# GS_02_Pow.net
KiCad netlist of a schematic drawn in Altium Designer
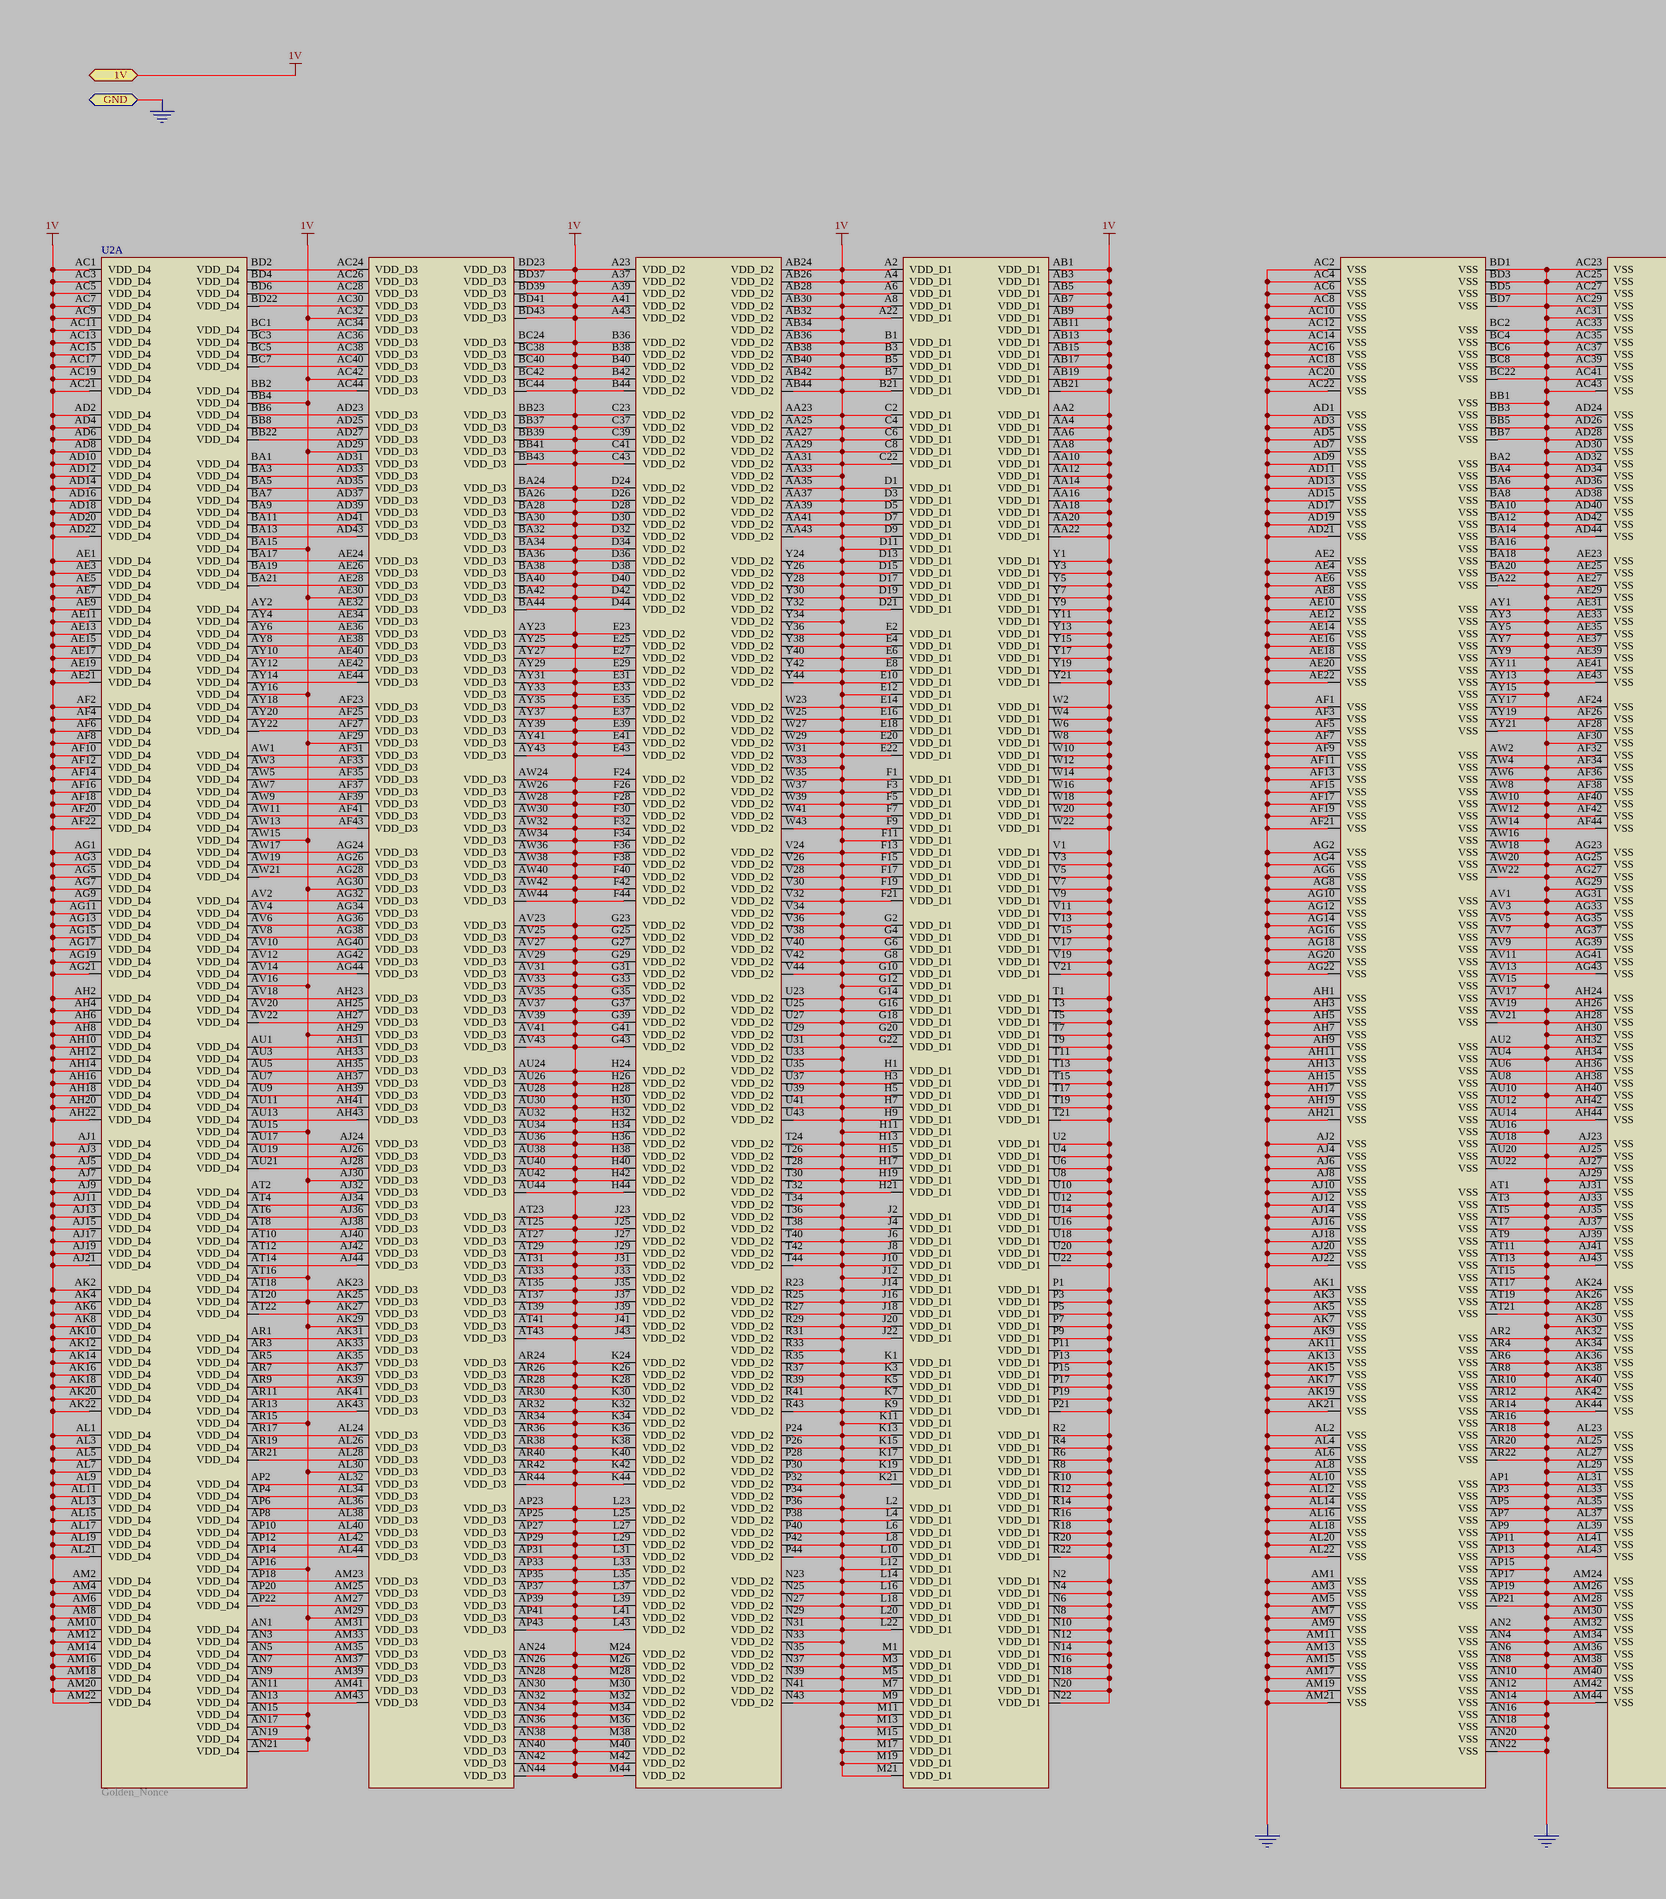
[diagram p0: GS_02_Pow.SchDoc, left]
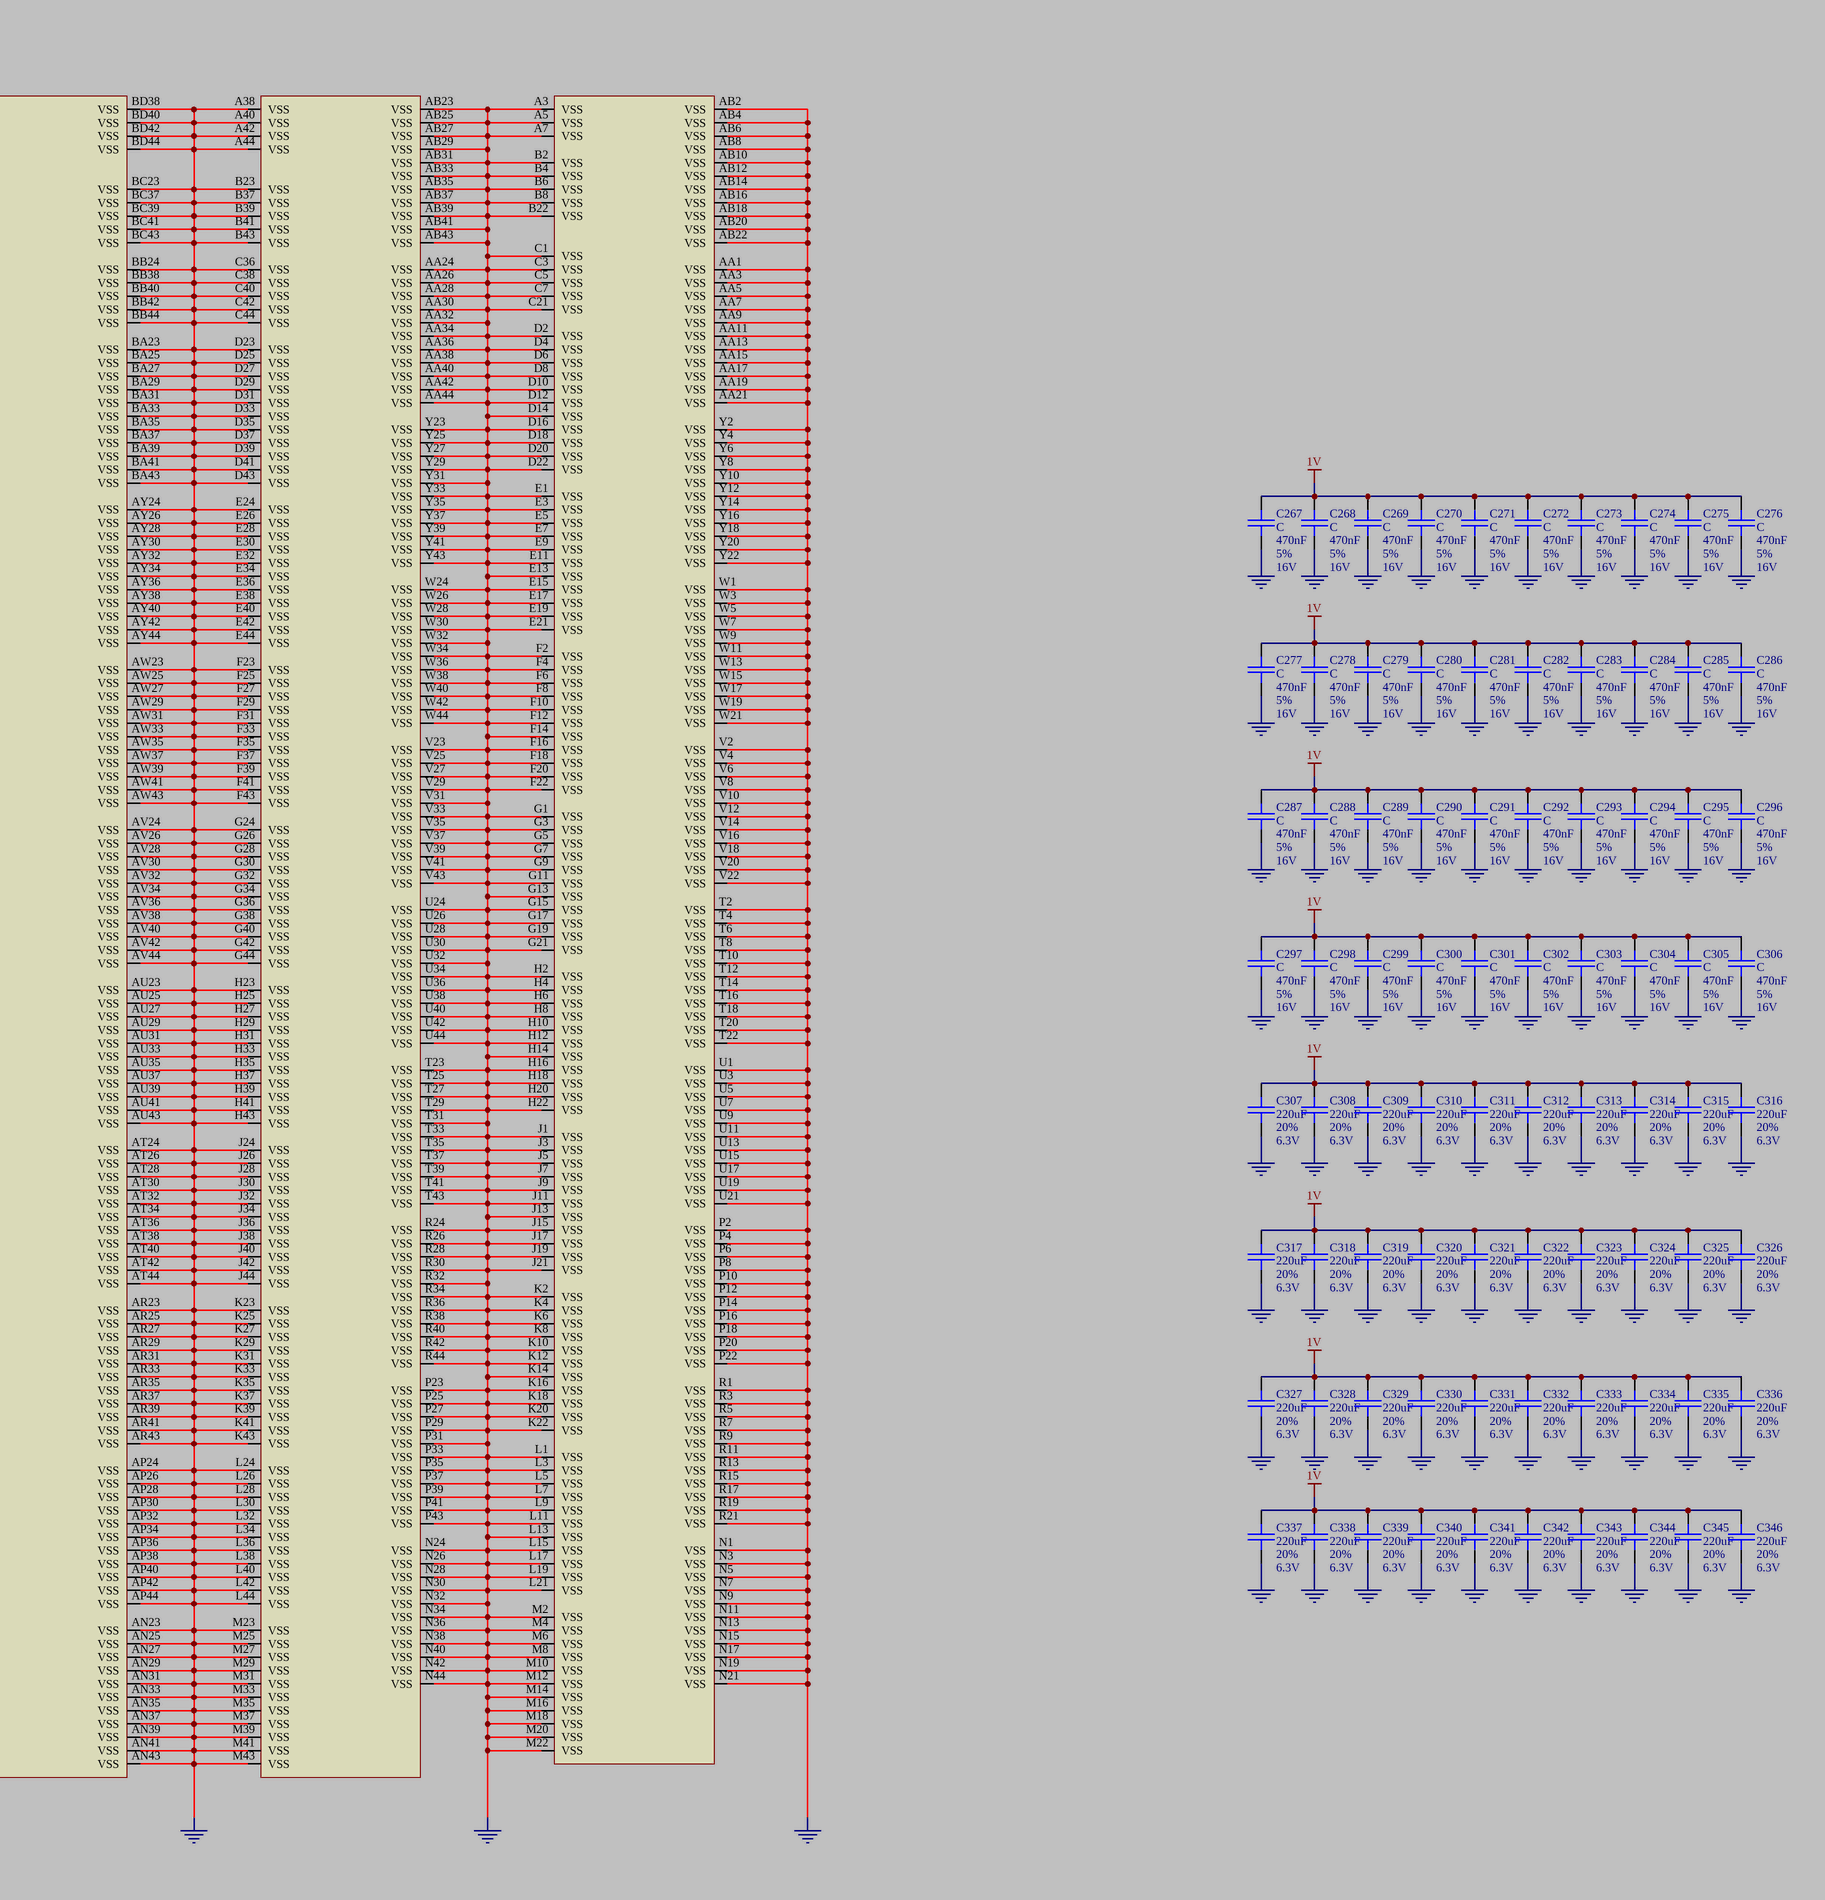
[diagram p1: GS_02_Pow.SchDoc, right]

(export (version "E")
  (design (tool "Eeschema 10.0.6"))
  (components
    (comp (ref "C267")
      (value "C")
      (footprint "SMD_0603_CAPC1608X95N")
      (fields
        (field (name "DB_PART_NUMBER") "CAP000028169")
        (field (name "DB_VALUE") "470nF")
        (field (name "DB_TOLERANCE") "5%")
        (field (name "DB_VOLTAGE") "16V")
        (field (name "DB_MANUFACTURER_PART") "KEMET    C0603C474J4RAC")
      )
      (libsource (lib "Database_Libs1") (part "C"))
    )
    (comp (ref "C268")
      (value "C")
      (footprint "SMD_0603_CAPC1608X95N")
      (fields
        (field (name "DB_PART_NUMBER") "CAP000028169")
        (field (name "DB_VALUE") "470nF")
        (field (name "DB_TOLERANCE") "5%")
        (field (name "DB_VOLTAGE") "16V")
        (field (name "DB_MANUFACTURER_PART") "KEMET    C0603C474J4RAC")
      )
      (libsource (lib "Database_Libs1") (part "C"))
    )
    (comp (ref "C269")
      (value "C")
      (footprint "SMD_0603_CAPC1608X95N")
      (fields
        (field (name "DB_PART_NUMBER") "CAP000028169")
        (field (name "DB_VALUE") "470nF")
        (field (name "DB_TOLERANCE") "5%")
        (field (name "DB_VOLTAGE") "16V")
        (field (name "DB_MANUFACTURER_PART") "KEMET    C0603C474J4RAC")
      )
      (libsource (lib "Database_Libs1") (part "C"))
    )
    (comp (ref "C270")
      (value "C")
      (footprint "SMD_0603_CAPC1608X95N")
      (fields
        (field (name "DB_PART_NUMBER") "CAP000028169")
        (field (name "DB_VALUE") "470nF")
        (field (name "DB_TOLERANCE") "5%")
        (field (name "DB_VOLTAGE") "16V")
        (field (name "DB_MANUFACTURER_PART") "KEMET    C0603C474J4RAC")
      )
      (libsource (lib "Database_Libs1") (part "C"))
    )
    (comp (ref "C271")
      (value "C")
      (footprint "SMD_0603_CAPC1608X95N")
      (fields
        (field (name "DB_PART_NUMBER") "CAP000028169")
        (field (name "DB_VALUE") "470nF")
        (field (name "DB_TOLERANCE") "5%")
        (field (name "DB_VOLTAGE") "16V")
        (field (name "DB_MANUFACTURER_PART") "KEMET    C0603C474J4RAC")
      )
      (libsource (lib "Database_Libs1") (part "C"))
    )
    (comp (ref "C272")
      (value "C")
      (footprint "SMD_0603_CAPC1608X95N")
      (fields
        (field (name "DB_PART_NUMBER") "CAP000028169")
        (field (name "DB_VALUE") "470nF")
        (field (name "DB_TOLERANCE") "5%")
        (field (name "DB_VOLTAGE") "16V")
        (field (name "DB_MANUFACTURER_PART") "KEMET    C0603C474J4RAC")
      )
      (libsource (lib "Database_Libs1") (part "C"))
    )
    (comp (ref "C273")
      (value "C")
      (footprint "SMD_0603_CAPC1608X95N")
      (fields
        (field (name "DB_PART_NUMBER") "CAP000028169")
        (field (name "DB_VALUE") "470nF")
        (field (name "DB_TOLERANCE") "5%")
        (field (name "DB_VOLTAGE") "16V")
        (field (name "DB_MANUFACTURER_PART") "KEMET    C0603C474J4RAC")
      )
      (libsource (lib "Database_Libs1") (part "C"))
    )
    (comp (ref "C274")
      (value "C")
      (footprint "SMD_0603_CAPC1608X95N")
      (fields
        (field (name "DB_PART_NUMBER") "CAP000028169")
        (field (name "DB_VALUE") "470nF")
        (field (name "DB_TOLERANCE") "5%")
        (field (name "DB_VOLTAGE") "16V")
        (field (name "DB_MANUFACTURER_PART") "KEMET    C0603C474J4RAC")
      )
      (libsource (lib "Database_Libs1") (part "C"))
    )
    (comp (ref "C275")
      (value "C")
      (footprint "SMD_0603_CAPC1608X95N")
      (fields
        (field (name "DB_PART_NUMBER") "CAP000028169")
        (field (name "DB_VALUE") "470nF")
        (field (name "DB_TOLERANCE") "5%")
        (field (name "DB_VOLTAGE") "16V")
        (field (name "DB_MANUFACTURER_PART") "KEMET    C0603C474J4RAC")
      )
      (libsource (lib "Database_Libs1") (part "C"))
    )
    (comp (ref "C276")
      (value "C")
      (footprint "SMD_0603_CAPC1608X95N")
      (fields
        (field (name "DB_PART_NUMBER") "CAP000028169")
        (field (name "DB_VALUE") "470nF")
        (field (name "DB_TOLERANCE") "5%")
        (field (name "DB_VOLTAGE") "16V")
        (field (name "DB_MANUFACTURER_PART") "KEMET    C0603C474J4RAC")
      )
      (libsource (lib "Database_Libs1") (part "C"))
    )
    (comp (ref "C277")
      (value "C")
      (footprint "SMD_0603_CAPC1608X95N")
      (fields
        (field (name "DB_PART_NUMBER") "CAP000028169")
        (field (name "DB_VALUE") "470nF")
        (field (name "DB_TOLERANCE") "5%")
        (field (name "DB_VOLTAGE") "16V")
        (field (name "DB_MANUFACTURER_PART") "KEMET    C0603C474J4RAC")
      )
      (libsource (lib "Database_Libs1") (part "C"))
    )
    (comp (ref "C278")
      (value "C")
      (footprint "SMD_0603_CAPC1608X95N")
      (fields
        (field (name "DB_PART_NUMBER") "CAP000028169")
        (field (name "DB_VALUE") "470nF")
        (field (name "DB_TOLERANCE") "5%")
        (field (name "DB_VOLTAGE") "16V")
        (field (name "DB_MANUFACTURER_PART") "KEMET    C0603C474J4RAC")
      )
      (libsource (lib "Database_Libs1") (part "C"))
    )
    (comp (ref "C279")
      (value "C")
      (footprint "SMD_0603_CAPC1608X95N")
      (fields
        (field (name "DB_PART_NUMBER") "CAP000028169")
        (field (name "DB_VALUE") "470nF")
        (field (name "DB_TOLERANCE") "5%")
        (field (name "DB_VOLTAGE") "16V")
        (field (name "DB_MANUFACTURER_PART") "KEMET    C0603C474J4RAC")
      )
      (libsource (lib "Database_Libs1") (part "C"))
    )
    (comp (ref "C280")
      (value "C")
      (footprint "SMD_0603_CAPC1608X95N")
      (fields
        (field (name "DB_PART_NUMBER") "CAP000028169")
        (field (name "DB_VALUE") "470nF")
        (field (name "DB_TOLERANCE") "5%")
        (field (name "DB_VOLTAGE") "16V")
        (field (name "DB_MANUFACTURER_PART") "KEMET    C0603C474J4RAC")
      )
      (libsource (lib "Database_Libs1") (part "C"))
    )
    (comp (ref "C281")
      (value "C")
      (footprint "SMD_0603_CAPC1608X95N")
      (fields
        (field (name "DB_PART_NUMBER") "CAP000028169")
        (field (name "DB_VALUE") "470nF")
        (field (name "DB_TOLERANCE") "5%")
        (field (name "DB_VOLTAGE") "16V")
        (field (name "DB_MANUFACTURER_PART") "KEMET    C0603C474J4RAC")
      )
      (libsource (lib "Database_Libs1") (part "C"))
    )
    (comp (ref "C282")
      (value "C")
      (footprint "SMD_0603_CAPC1608X95N")
      (fields
        (field (name "DB_PART_NUMBER") "CAP000028169")
        (field (name "DB_VALUE") "470nF")
        (field (name "DB_TOLERANCE") "5%")
        (field (name "DB_VOLTAGE") "16V")
        (field (name "DB_MANUFACTURER_PART") "KEMET    C0603C474J4RAC")
      )
      (libsource (lib "Database_Libs1") (part "C"))
    )
    (comp (ref "C283")
      (value "C")
      (footprint "SMD_0603_CAPC1608X95N")
      (fields
        (field (name "DB_PART_NUMBER") "CAP000028169")
        (field (name "DB_VALUE") "470nF")
        (field (name "DB_TOLERANCE") "5%")
        (field (name "DB_VOLTAGE") "16V")
        (field (name "DB_MANUFACTURER_PART") "KEMET    C0603C474J4RAC")
      )
      (libsource (lib "Database_Libs1") (part "C"))
    )
    (comp (ref "C284")
      (value "C")
      (footprint "SMD_0603_CAPC1608X95N")
      (fields
        (field (name "DB_PART_NUMBER") "CAP000028169")
        (field (name "DB_VALUE") "470nF")
        (field (name "DB_TOLERANCE") "5%")
        (field (name "DB_VOLTAGE") "16V")
        (field (name "DB_MANUFACTURER_PART") "KEMET    C0603C474J4RAC")
      )
      (libsource (lib "Database_Libs1") (part "C"))
    )
    (comp (ref "C285")
      (value "C")
      (footprint "SMD_0603_CAPC1608X95N")
      (fields
        (field (name "DB_PART_NUMBER") "CAP000028169")
        (field (name "DB_VALUE") "470nF")
        (field (name "DB_TOLERANCE") "5%")
        (field (name "DB_VOLTAGE") "16V")
        (field (name "DB_MANUFACTURER_PART") "KEMET    C0603C474J4RAC")
      )
      (libsource (lib "Database_Libs1") (part "C"))
    )
    (comp (ref "C286")
      (value "C")
      (footprint "SMD_0603_CAPC1608X95N")
      (fields
        (field (name "DB_PART_NUMBER") "CAP000028169")
        (field (name "DB_VALUE") "470nF")
        (field (name "DB_TOLERANCE") "5%")
        (field (name "DB_VOLTAGE") "16V")
        (field (name "DB_MANUFACTURER_PART") "KEMET    C0603C474J4RAC")
      )
      (libsource (lib "Database_Libs1") (part "C"))
    )
    (comp (ref "C287")
      (value "C")
      (footprint "SMD_0603_CAPC1608X95N")
      (fields
        (field (name "DB_PART_NUMBER") "CAP000028169")
        (field (name "DB_VALUE") "470nF")
        (field (name "DB_TOLERANCE") "5%")
        (field (name "DB_VOLTAGE") "16V")
        (field (name "DB_MANUFACTURER_PART") "KEMET    C0603C474J4RAC")
      )
      (libsource (lib "Database_Libs1") (part "C"))
    )
    (comp (ref "C288")
      (value "C")
      (footprint "SMD_0603_CAPC1608X95N")
      (fields
        (field (name "DB_PART_NUMBER") "CAP000028169")
        (field (name "DB_VALUE") "470nF")
        (field (name "DB_TOLERANCE") "5%")
        (field (name "DB_VOLTAGE") "16V")
        (field (name "DB_MANUFACTURER_PART") "KEMET    C0603C474J4RAC")
      )
      (libsource (lib "Database_Libs1") (part "C"))
    )
    (comp (ref "C289")
      (value "C")
      (footprint "SMD_0603_CAPC1608X95N")
      (fields
        (field (name "DB_PART_NUMBER") "CAP000028169")
        (field (name "DB_VALUE") "470nF")
        (field (name "DB_TOLERANCE") "5%")
        (field (name "DB_VOLTAGE") "16V")
        (field (name "DB_MANUFACTURER_PART") "KEMET    C0603C474J4RAC")
      )
      (libsource (lib "Database_Libs1") (part "C"))
    )
    (comp (ref "C290")
      (value "C")
      (footprint "SMD_0603_CAPC1608X95N")
      (fields
        (field (name "DB_PART_NUMBER") "CAP000028169")
        (field (name "DB_VALUE") "470nF")
        (field (name "DB_TOLERANCE") "5%")
        (field (name "DB_VOLTAGE") "16V")
        (field (name "DB_MANUFACTURER_PART") "KEMET    C0603C474J4RAC")
      )
      (libsource (lib "Database_Libs1") (part "C"))
    )
    (comp (ref "C291")
      (value "C")
      (footprint "SMD_0603_CAPC1608X95N")
      (fields
        (field (name "DB_PART_NUMBER") "CAP000028169")
        (field (name "DB_VALUE") "470nF")
        (field (name "DB_TOLERANCE") "5%")
        (field (name "DB_VOLTAGE") "16V")
        (field (name "DB_MANUFACTURER_PART") "KEMET    C0603C474J4RAC")
      )
      (libsource (lib "Database_Libs1") (part "C"))
    )
    (comp (ref "C292")
      (value "C")
      (footprint "SMD_0603_CAPC1608X95N")
      (fields
        (field (name "DB_PART_NUMBER") "CAP000028169")
        (field (name "DB_VALUE") "470nF")
        (field (name "DB_TOLERANCE") "5%")
        (field (name "DB_VOLTAGE") "16V")
        (field (name "DB_MANUFACTURER_PART") "KEMET    C0603C474J4RAC")
      )
      (libsource (lib "Database_Libs1") (part "C"))
    )
    (comp (ref "C293")
      (value "C")
      (footprint "SMD_0603_CAPC1608X95N")
      (fields
        (field (name "DB_PART_NUMBER") "CAP000028169")
        (field (name "DB_VALUE") "470nF")
        (field (name "DB_TOLERANCE") "5%")
        (field (name "DB_VOLTAGE") "16V")
        (field (name "DB_MANUFACTURER_PART") "KEMET    C0603C474J4RAC")
      )
      (libsource (lib "Database_Libs1") (part "C"))
    )
    (comp (ref "C294")
      (value "C")
      (footprint "SMD_0603_CAPC1608X95N")
      (fields
        (field (name "DB_PART_NUMBER") "CAP000028169")
        (field (name "DB_VALUE") "470nF")
        (field (name "DB_TOLERANCE") "5%")
        (field (name "DB_VOLTAGE") "16V")
        (field (name "DB_MANUFACTURER_PART") "KEMET    C0603C474J4RAC")
      )
      (libsource (lib "Database_Libs1") (part "C"))
    )
    (comp (ref "C295")
      (value "C")
      (footprint "SMD_0603_CAPC1608X95N")
      (fields
        (field (name "DB_PART_NUMBER") "CAP000028169")
        (field (name "DB_VALUE") "470nF")
        (field (name "DB_TOLERANCE") "5%")
        (field (name "DB_VOLTAGE") "16V")
        (field (name "DB_MANUFACTURER_PART") "KEMET    C0603C474J4RAC")
      )
      (libsource (lib "Database_Libs1") (part "C"))
    )
    (comp (ref "C296")
      (value "C")
      (footprint "SMD_0603_CAPC1608X95N")
      (fields
        (field (name "DB_PART_NUMBER") "CAP000028169")
        (field (name "DB_VALUE") "470nF")
        (field (name "DB_TOLERANCE") "5%")
        (field (name "DB_VOLTAGE") "16V")
        (field (name "DB_MANUFACTURER_PART") "KEMET    C0603C474J4RAC")
      )
      (libsource (lib "Database_Libs1") (part "C"))
    )
    (comp (ref "C297")
      (value "C")
      (footprint "SMD_0603_CAPC1608X95N")
      (fields
        (field (name "DB_PART_NUMBER") "CAP000028169")
        (field (name "DB_VALUE") "470nF")
        (field (name "DB_TOLERANCE") "5%")
        (field (name "DB_VOLTAGE") "16V")
        (field (name "DB_MANUFACTURER_PART") "KEMET    C0603C474J4RAC")
      )
      (libsource (lib "Database_Libs1") (part "C"))
    )
    (comp (ref "C298")
      (value "C")
      (footprint "SMD_0603_CAPC1608X95N")
      (fields
        (field (name "DB_PART_NUMBER") "CAP000028169")
        (field (name "DB_VALUE") "470nF")
        (field (name "DB_TOLERANCE") "5%")
        (field (name "DB_VOLTAGE") "16V")
        (field (name "DB_MANUFACTURER_PART") "KEMET    C0603C474J4RAC")
      )
      (libsource (lib "Database_Libs1") (part "C"))
    )
    (comp (ref "C299")
      (value "C")
      (footprint "SMD_0603_CAPC1608X95N")
      (fields
        (field (name "DB_PART_NUMBER") "CAP000028169")
        (field (name "DB_VALUE") "470nF")
        (field (name "DB_TOLERANCE") "5%")
        (field (name "DB_VOLTAGE") "16V")
        (field (name "DB_MANUFACTURER_PART") "KEMET    C0603C474J4RAC")
      )
      (libsource (lib "Database_Libs1") (part "C"))
    )
    (comp (ref "C300")
      (value "C")
      (footprint "SMD_0603_CAPC1608X95N")
      (fields
        (field (name "DB_PART_NUMBER") "CAP000028169")
        (field (name "DB_VALUE") "470nF")
        (field (name "DB_TOLERANCE") "5%")
        (field (name "DB_VOLTAGE") "16V")
        (field (name "DB_MANUFACTURER_PART") "KEMET    C0603C474J4RAC")
      )
      (libsource (lib "Database_Libs1") (part "C"))
    )
    (comp (ref "C301")
      (value "C")
      (footprint "SMD_0603_CAPC1608X95N")
      (fields
        (field (name "DB_PART_NUMBER") "CAP000028169")
        (field (name "DB_VALUE") "470nF")
        (field (name "DB_TOLERANCE") "5%")
        (field (name "DB_VOLTAGE") "16V")
        (field (name "DB_MANUFACTURER_PART") "KEMET    C0603C474J4RAC")
      )
      (libsource (lib "Database_Libs1") (part "C"))
    )
    (comp (ref "C302")
      (value "C")
      (footprint "SMD_0603_CAPC1608X95N")
      (fields
        (field (name "DB_PART_NUMBER") "CAP000028169")
        (field (name "DB_VALUE") "470nF")
        (field (name "DB_TOLERANCE") "5%")
        (field (name "DB_VOLTAGE") "16V")
        (field (name "DB_MANUFACTURER_PART") "KEMET    C0603C474J4RAC")
      )
      (libsource (lib "Database_Libs1") (part "C"))
    )
    (comp (ref "C303")
      (value "C")
      (footprint "SMD_0603_CAPC1608X95N")
      (fields
        (field (name "DB_PART_NUMBER") "CAP000028169")
        (field (name "DB_VALUE") "470nF")
        (field (name "DB_TOLERANCE") "5%")
        (field (name "DB_VOLTAGE") "16V")
        (field (name "DB_MANUFACTURER_PART") "KEMET    C0603C474J4RAC")
      )
      (libsource (lib "Database_Libs1") (part "C"))
    )
    (comp (ref "C304")
      (value "C")
      (footprint "SMD_0603_CAPC1608X95N")
      (fields
        (field (name "DB_PART_NUMBER") "CAP000028169")
        (field (name "DB_VALUE") "470nF")
        (field (name "DB_TOLERANCE") "5%")
        (field (name "DB_VOLTAGE") "16V")
        (field (name "DB_MANUFACTURER_PART") "KEMET    C0603C474J4RAC")
      )
      (libsource (lib "Database_Libs1") (part "C"))
    )
    (comp (ref "C305")
      (value "C")
      (footprint "SMD_0603_CAPC1608X95N")
      (fields
        (field (name "DB_PART_NUMBER") "CAP000028169")
        (field (name "DB_VALUE") "470nF")
        (field (name "DB_TOLERANCE") "5%")
        (field (name "DB_VOLTAGE") "16V")
        (field (name "DB_MANUFACTURER_PART") "KEMET    C0603C474J4RAC")
      )
      (libsource (lib "Database_Libs1") (part "C"))
    )
    (comp (ref "C306")
      (value "C")
      (footprint "SMD_0603_CAPC1608X95N")
      (fields
        (field (name "DB_PART_NUMBER") "CAP000028169")
        (field (name "DB_VALUE") "470nF")
        (field (name "DB_TOLERANCE") "5%")
        (field (name "DB_VOLTAGE") "16V")
        (field (name "DB_MANUFACTURER_PART") "KEMET    C0603C474J4RAC")
      )
      (libsource (lib "Database_Libs1") (part "C"))
    )
    (comp (ref "C307")
      (value "C")
      (footprint "SMD_1210_CAPC3225X279N")
      (fields
        (field (name "DB_PART_NUMBER") "CAP000047355")
        (field (name "DB_VALUE") "220uF")
        (field (name "DB_TOLERANCE") "20%")
        (field (name "DB_VOLTAGE") "6.3V")
        (field (name "DB_MANUFACTURER_PART") "SAMSUNG    CL32A227MQVNNNE")
        (field (name "DB_APPROVED_BY") "VSN")
      )
      (libsource (lib "Database_Libs1") (part "C"))
    )
    (comp (ref "C308")
      (value "C")
      (footprint "SMD_1210_CAPC3225X279N")
      (fields
        (field (name "DB_PART_NUMBER") "CAP000047355")
        (field (name "DB_VALUE") "220uF")
        (field (name "DB_TOLERANCE") "20%")
        (field (name "DB_VOLTAGE") "6.3V")
        (field (name "DB_MANUFACTURER_PART") "SAMSUNG    CL32A227MQVNNNE")
        (field (name "DB_APPROVED_BY") "VSN")
      )
      (libsource (lib "Database_Libs1") (part "C"))
    )
    (comp (ref "C309")
      (value "C")
      (footprint "SMD_1210_CAPC3225X279N")
      (fields
        (field (name "DB_PART_NUMBER") "CAP000047355")
        (field (name "DB_VALUE") "220uF")
        (field (name "DB_TOLERANCE") "20%")
        (field (name "DB_VOLTAGE") "6.3V")
        (field (name "DB_MANUFACTURER_PART") "SAMSUNG    CL32A227MQVNNNE")
        (field (name "DB_APPROVED_BY") "VSN")
      )
      (libsource (lib "Database_Libs1") (part "C"))
    )
    (comp (ref "C310")
      (value "C")
      (footprint "SMD_1210_CAPC3225X279N")
      (fields
        (field (name "DB_PART_NUMBER") "CAP000047355")
        (field (name "DB_VALUE") "220uF")
        (field (name "DB_TOLERANCE") "20%")
        (field (name "DB_VOLTAGE") "6.3V")
        (field (name "DB_MANUFACTURER_PART") "SAMSUNG    CL32A227MQVNNNE")
        (field (name "DB_APPROVED_BY") "VSN")
      )
      (libsource (lib "Database_Libs1") (part "C"))
    )
    (comp (ref "C311")
      (value "C")
      (footprint "SMD_1210_CAPC3225X279N")
      (fields
        (field (name "DB_PART_NUMBER") "CAP000047355")
        (field (name "DB_VALUE") "220uF")
        (field (name "DB_TOLERANCE") "20%")
        (field (name "DB_VOLTAGE") "6.3V")
        (field (name "DB_MANUFACTURER_PART") "SAMSUNG    CL32A227MQVNNNE")
        (field (name "DB_APPROVED_BY") "VSN")
      )
      (libsource (lib "Database_Libs1") (part "C"))
    )
    (comp (ref "C312")
      (value "C")
      (footprint "SMD_1210_CAPC3225X279N")
      (fields
        (field (name "DB_PART_NUMBER") "CAP000047355")
        (field (name "DB_VALUE") "220uF")
        (field (name "DB_TOLERANCE") "20%")
        (field (name "DB_VOLTAGE") "6.3V")
        (field (name "DB_MANUFACTURER_PART") "SAMSUNG    CL32A227MQVNNNE")
        (field (name "DB_APPROVED_BY") "VSN")
      )
      (libsource (lib "Database_Libs1") (part "C"))
    )
    (comp (ref "C313")
      (value "C")
      (footprint "SMD_1210_CAPC3225X279N")
      (fields
        (field (name "DB_PART_NUMBER") "CAP000047355")
        (field (name "DB_VALUE") "220uF")
        (field (name "DB_TOLERANCE") "20%")
        (field (name "DB_VOLTAGE") "6.3V")
        (field (name "DB_MANUFACTURER_PART") "SAMSUNG    CL32A227MQVNNNE")
        (field (name "DB_APPROVED_BY") "VSN")
      )
      (libsource (lib "Database_Libs1") (part "C"))
    )
    (comp (ref "C314")
      (value "C")
      (footprint "SMD_1210_CAPC3225X279N")
      (fields
        (field (name "DB_PART_NUMBER") "CAP000047355")
        (field (name "DB_VALUE") "220uF")
        (field (name "DB_TOLERANCE") "20%")
        (field (name "DB_VOLTAGE") "6.3V")
        (field (name "DB_MANUFACTURER_PART") "SAMSUNG    CL32A227MQVNNNE")
        (field (name "DB_APPROVED_BY") "VSN")
      )
      (libsource (lib "Database_Libs1") (part "C"))
    )
    (comp (ref "C315")
      (value "C")
      (footprint "SMD_1210_CAPC3225X279N")
      (fields
        (field (name "DB_PART_NUMBER") "CAP000047355")
        (field (name "DB_VALUE") "220uF")
        (field (name "DB_TOLERANCE") "20%")
        (field (name "DB_VOLTAGE") "6.3V")
        (field (name "DB_MANUFACTURER_PART") "SAMSUNG    CL32A227MQVNNNE")
        (field (name "DB_APPROVED_BY") "VSN")
      )
      (libsource (lib "Database_Libs1") (part "C"))
    )
    (comp (ref "C316")
      (value "C")
      (footprint "SMD_1210_CAPC3225X279N")
      (fields
        (field (name "DB_PART_NUMBER") "CAP000047355")
        (field (name "DB_VALUE") "220uF")
        (field (name "DB_TOLERANCE") "20%")
        (field (name "DB_VOLTAGE") "6.3V")
        (field (name "DB_MANUFACTURER_PART") "SAMSUNG    CL32A227MQVNNNE")
        (field (name "DB_APPROVED_BY") "VSN")
      )
      (libsource (lib "Database_Libs1") (part "C"))
    )
    (comp (ref "C317")
      (value "C")
      (footprint "SMD_1210_CAPC3225X279N")
      (fields
        (field (name "DB_PART_NUMBER") "CAP000047355")
        (field (name "DB_VALUE") "220uF")
        (field (name "DB_TOLERANCE") "20%")
        (field (name "DB_VOLTAGE") "6.3V")
        (field (name "DB_MANUFACTURER_PART") "SAMSUNG    CL32A227MQVNNNE")
        (field (name "DB_APPROVED_BY") "VSN")
      )
      (libsource (lib "Database_Libs1") (part "C"))
    )
    (comp (ref "C318")
      (value "C")
      (footprint "SMD_1210_CAPC3225X279N")
      (fields
        (field (name "DB_PART_NUMBER") "CAP000047355")
        (field (name "DB_VALUE") "220uF")
        (field (name "DB_TOLERANCE") "20%")
        (field (name "DB_VOLTAGE") "6.3V")
        (field (name "DB_MANUFACTURER_PART") "SAMSUNG    CL32A227MQVNNNE")
        (field (name "DB_APPROVED_BY") "VSN")
      )
      (libsource (lib "Database_Libs1") (part "C"))
    )
    (comp (ref "C319")
      (value "C")
      (footprint "SMD_1210_CAPC3225X279N")
      (fields
        (field (name "DB_PART_NUMBER") "CAP000047355")
        (field (name "DB_VALUE") "220uF")
        (field (name "DB_TOLERANCE") "20%")
        (field (name "DB_VOLTAGE") "6.3V")
        (field (name "DB_MANUFACTURER_PART") "SAMSUNG    CL32A227MQVNNNE")
        (field (name "DB_APPROVED_BY") "VSN")
      )
      (libsource (lib "Database_Libs1") (part "C"))
    )
    (comp (ref "C320")
      (value "C")
      (footprint "SMD_1210_CAPC3225X279N")
      (fields
        (field (name "DB_PART_NUMBER") "CAP000047355")
        (field (name "DB_VALUE") "220uF")
        (field (name "DB_TOLERANCE") "20%")
        (field (name "DB_VOLTAGE") "6.3V")
        (field (name "DB_MANUFACTURER_PART") "SAMSUNG    CL32A227MQVNNNE")
        (field (name "DB_APPROVED_BY") "VSN")
      )
      (libsource (lib "Database_Libs1") (part "C"))
    )
    (comp (ref "C321")
      (value "C")
      (footprint "SMD_1210_CAPC3225X279N")
      (fields
        (field (name "DB_PART_NUMBER") "CAP000047355")
        (field (name "DB_VALUE") "220uF")
        (field (name "DB_TOLERANCE") "20%")
        (field (name "DB_VOLTAGE") "6.3V")
        (field (name "DB_MANUFACTURER_PART") "SAMSUNG    CL32A227MQVNNNE")
        (field (name "DB_APPROVED_BY") "VSN")
      )
      (libsource (lib "Database_Libs1") (part "C"))
    )
    (comp (ref "C322")
      (value "C")
      (footprint "SMD_1210_CAPC3225X279N")
      (fields
        (field (name "DB_PART_NUMBER") "CAP000047355")
        (field (name "DB_VALUE") "220uF")
        (field (name "DB_TOLERANCE") "20%")
        (field (name "DB_VOLTAGE") "6.3V")
        (field (name "DB_MANUFACTURER_PART") "SAMSUNG    CL32A227MQVNNNE")
        (field (name "DB_APPROVED_BY") "VSN")
      )
      (libsource (lib "Database_Libs1") (part "C"))
    )
    (comp (ref "C323")
      (value "C")
      (footprint "SMD_1210_CAPC3225X279N")
      (fields
        (field (name "DB_PART_NUMBER") "CAP000047355")
        (field (name "DB_VALUE") "220uF")
        (field (name "DB_TOLERANCE") "20%")
        (field (name "DB_VOLTAGE") "6.3V")
        (field (name "DB_MANUFACTURER_PART") "SAMSUNG    CL32A227MQVNNNE")
        (field (name "DB_APPROVED_BY") "VSN")
      )
      (libsource (lib "Database_Libs1") (part "C"))
    )
    (comp (ref "C324")
      (value "C")
      (footprint "SMD_1210_CAPC3225X279N")
      (fields
        (field (name "DB_PART_NUMBER") "CAP000047355")
        (field (name "DB_VALUE") "220uF")
        (field (name "DB_TOLERANCE") "20%")
        (field (name "DB_VOLTAGE") "6.3V")
        (field (name "DB_MANUFACTURER_PART") "SAMSUNG    CL32A227MQVNNNE")
        (field (name "DB_APPROVED_BY") "VSN")
      )
      (libsource (lib "Database_Libs1") (part "C"))
    )
    (comp (ref "C325")
      (value "C")
      (footprint "SMD_1210_CAPC3225X279N")
      (fields
        (field (name "DB_PART_NUMBER") "CAP000047355")
        (field (name "DB_VALUE") "220uF")
        (field (name "DB_TOLERANCE") "20%")
        (field (name "DB_VOLTAGE") "6.3V")
        (field (name "DB_MANUFACTURER_PART") "SAMSUNG    CL32A227MQVNNNE")
        (field (name "DB_APPROVED_BY") "VSN")
      )
      (libsource (lib "Database_Libs1") (part "C"))
    )
    (comp (ref "C326")
      (value "C")
      (footprint "SMD_1210_CAPC3225X279N")
      (fields
        (field (name "DB_PART_NUMBER") "CAP000047355")
        (field (name "DB_VALUE") "220uF")
        (field (name "DB_TOLERANCE") "20%")
        (field (name "DB_VOLTAGE") "6.3V")
        (field (name "DB_MANUFACTURER_PART") "SAMSUNG    CL32A227MQVNNNE")
        (field (name "DB_APPROVED_BY") "VSN")
      )
      (libsource (lib "Database_Libs1") (part "C"))
    )
    (comp (ref "C327")
      (value "C")
      (footprint "SMD_1210_CAPC3225X279N")
      (fields
        (field (name "DB_PART_NUMBER") "CAP000047355")
        (field (name "DB_VALUE") "220uF")
        (field (name "DB_TOLERANCE") "20%")
        (field (name "DB_VOLTAGE") "6.3V")
        (field (name "DB_MANUFACTURER_PART") "SAMSUNG    CL32A227MQVNNNE")
        (field (name "DB_APPROVED_BY") "VSN")
      )
      (libsource (lib "Database_Libs1") (part "C"))
    )
    (comp (ref "C328")
      (value "C")
      (footprint "SMD_1210_CAPC3225X279N")
      (fields
        (field (name "DB_PART_NUMBER") "CAP000047355")
        (field (name "DB_VALUE") "220uF")
        (field (name "DB_TOLERANCE") "20%")
        (field (name "DB_VOLTAGE") "6.3V")
        (field (name "DB_MANUFACTURER_PART") "SAMSUNG    CL32A227MQVNNNE")
        (field (name "DB_APPROVED_BY") "VSN")
      )
      (libsource (lib "Database_Libs1") (part "C"))
    )
    (comp (ref "C329")
      (value "C")
      (footprint "SMD_1210_CAPC3225X279N")
      (fields
        (field (name "DB_PART_NUMBER") "CAP000047355")
        (field (name "DB_VALUE") "220uF")
        (field (name "DB_TOLERANCE") "20%")
        (field (name "DB_VOLTAGE") "6.3V")
        (field (name "DB_MANUFACTURER_PART") "SAMSUNG    CL32A227MQVNNNE")
        (field (name "DB_APPROVED_BY") "VSN")
      )
      (libsource (lib "Database_Libs1") (part "C"))
    )
    (comp (ref "C330")
      (value "C")
      (footprint "SMD_1210_CAPC3225X279N")
      (fields
        (field (name "DB_PART_NUMBER") "CAP000047355")
        (field (name "DB_VALUE") "220uF")
        (field (name "DB_TOLERANCE") "20%")
        (field (name "DB_VOLTAGE") "6.3V")
        (field (name "DB_MANUFACTURER_PART") "SAMSUNG    CL32A227MQVNNNE")
        (field (name "DB_APPROVED_BY") "VSN")
      )
      (libsource (lib "Database_Libs1") (part "C"))
    )
    (comp (ref "C331")
      (value "C")
      (footprint "SMD_1210_CAPC3225X279N")
      (fields
        (field (name "DB_PART_NUMBER") "CAP000047355")
        (field (name "DB_VALUE") "220uF")
        (field (name "DB_TOLERANCE") "20%")
        (field (name "DB_VOLTAGE") "6.3V")
        (field (name "DB_MANUFACTURER_PART") "SAMSUNG    CL32A227MQVNNNE")
        (field (name "DB_APPROVED_BY") "VSN")
      )
      (libsource (lib "Database_Libs1") (part "C"))
    )
    (comp (ref "C332")
      (value "C")
      (footprint "SMD_1210_CAPC3225X279N")
      (fields
        (field (name "DB_PART_NUMBER") "CAP000047355")
        (field (name "DB_VALUE") "220uF")
        (field (name "DB_TOLERANCE") "20%")
        (field (name "DB_VOLTAGE") "6.3V")
        (field (name "DB_MANUFACTURER_PART") "SAMSUNG    CL32A227MQVNNNE")
        (field (name "DB_APPROVED_BY") "VSN")
      )
      (libsource (lib "Database_Libs1") (part "C"))
    )
    (comp (ref "C333")
      (value "C")
      (footprint "SMD_1210_CAPC3225X279N")
      (fields
        (field (name "DB_PART_NUMBER") "CAP000047355")
        (field (name "DB_VALUE") "220uF")
        (field (name "DB_TOLERANCE") "20%")
        (field (name "DB_VOLTAGE") "6.3V")
        (field (name "DB_MANUFACTURER_PART") "SAMSUNG    CL32A227MQVNNNE")
        (field (name "DB_APPROVED_BY") "VSN")
      )
      (libsource (lib "Database_Libs1") (part "C"))
    )
    (comp (ref "C334")
      (value "C")
      (footprint "SMD_1210_CAPC3225X279N")
      (fields
        (field (name "DB_PART_NUMBER") "CAP000047355")
        (field (name "DB_VALUE") "220uF")
        (field (name "DB_TOLERANCE") "20%")
        (field (name "DB_VOLTAGE") "6.3V")
        (field (name "DB_MANUFACTURER_PART") "SAMSUNG    CL32A227MQVNNNE")
        (field (name "DB_APPROVED_BY") "VSN")
      )
      (libsource (lib "Database_Libs1") (part "C"))
    )
    (comp (ref "C335")
      (value "C")
      (footprint "SMD_1210_CAPC3225X279N")
      (fields
        (field (name "DB_PART_NUMBER") "CAP000047355")
        (field (name "DB_VALUE") "220uF")
        (field (name "DB_TOLERANCE") "20%")
        (field (name "DB_VOLTAGE") "6.3V")
        (field (name "DB_MANUFACTURER_PART") "SAMSUNG    CL32A227MQVNNNE")
        (field (name "DB_APPROVED_BY") "VSN")
      )
      (libsource (lib "Database_Libs1") (part "C"))
    )
    (comp (ref "C336")
      (value "C")
      (footprint "SMD_1210_CAPC3225X279N")
      (fields
        (field (name "DB_PART_NUMBER") "CAP000047355")
        (field (name "DB_VALUE") "220uF")
        (field (name "DB_TOLERANCE") "20%")
        (field (name "DB_VOLTAGE") "6.3V")
        (field (name "DB_MANUFACTURER_PART") "SAMSUNG    CL32A227MQVNNNE")
        (field (name "DB_APPROVED_BY") "VSN")
      )
      (libsource (lib "Database_Libs1") (part "C"))
    )
    (comp (ref "C337")
      (value "C")
      (footprint "SMD_1210_CAPC3225X279N")
      (fields
        (field (name "DB_PART_NUMBER") "CAP000047355")
        (field (name "DB_VALUE") "220uF")
        (field (name "DB_TOLERANCE") "20%")
        (field (name "DB_VOLTAGE") "6.3V")
        (field (name "DB_MANUFACTURER_PART") "SAMSUNG    CL32A227MQVNNNE")
        (field (name "DB_APPROVED_BY") "VSN")
      )
      (libsource (lib "Database_Libs1") (part "C"))
    )
    (comp (ref "C338")
      (value "C")
      (footprint "SMD_1210_CAPC3225X279N")
      (fields
        (field (name "DB_PART_NUMBER") "CAP000047355")
        (field (name "DB_VALUE") "220uF")
        (field (name "DB_TOLERANCE") "20%")
        (field (name "DB_VOLTAGE") "6.3V")
        (field (name "DB_MANUFACTURER_PART") "SAMSUNG    CL32A227MQVNNNE")
        (field (name "DB_APPROVED_BY") "VSN")
      )
      (libsource (lib "Database_Libs1") (part "C"))
    )
    (comp (ref "C339")
      (value "C")
      (footprint "SMD_1210_CAPC3225X279N")
      (fields
        (field (name "DB_PART_NUMBER") "CAP000047355")
        (field (name "DB_VALUE") "220uF")
        (field (name "DB_TOLERANCE") "20%")
        (field (name "DB_VOLTAGE") "6.3V")
        (field (name "DB_MANUFACTURER_PART") "SAMSUNG    CL32A227MQVNNNE")
        (field (name "DB_APPROVED_BY") "VSN")
      )
      (libsource (lib "Database_Libs1") (part "C"))
    )
    (comp (ref "C340")
      (value "C")
      (footprint "SMD_1210_CAPC3225X279N")
      (fields
        (field (name "DB_PART_NUMBER") "CAP000047355")
        (field (name "DB_VALUE") "220uF")
        (field (name "DB_TOLERANCE") "20%")
        (field (name "DB_VOLTAGE") "6.3V")
        (field (name "DB_MANUFACTURER_PART") "SAMSUNG    CL32A227MQVNNNE")
        (field (name "DB_APPROVED_BY") "VSN")
      )
      (libsource (lib "Database_Libs1") (part "C"))
    )
    (comp (ref "C341")
      (value "C")
      (footprint "SMD_1210_CAPC3225X279N")
      (fields
        (field (name "DB_PART_NUMBER") "CAP000047355")
        (field (name "DB_VALUE") "220uF")
        (field (name "DB_TOLERANCE") "20%")
        (field (name "DB_VOLTAGE") "6.3V")
        (field (name "DB_MANUFACTURER_PART") "SAMSUNG    CL32A227MQVNNNE")
        (field (name "DB_APPROVED_BY") "VSN")
      )
      (libsource (lib "Database_Libs1") (part "C"))
    )
    (comp (ref "C342")
      (value "C")
      (footprint "SMD_1210_CAPC3225X279N")
      (fields
        (field (name "DB_PART_NUMBER") "CAP000047355")
        (field (name "DB_VALUE") "220uF")
        (field (name "DB_TOLERANCE") "20%")
        (field (name "DB_VOLTAGE") "6.3V")
        (field (name "DB_MANUFACTURER_PART") "SAMSUNG    CL32A227MQVNNNE")
        (field (name "DB_APPROVED_BY") "VSN")
      )
      (libsource (lib "Database_Libs1") (part "C"))
    )
    (comp (ref "C343")
      (value "C")
      (footprint "SMD_1210_CAPC3225X279N")
      (fields
        (field (name "DB_PART_NUMBER") "CAP000047355")
        (field (name "DB_VALUE") "220uF")
        (field (name "DB_TOLERANCE") "20%")
        (field (name "DB_VOLTAGE") "6.3V")
        (field (name "DB_MANUFACTURER_PART") "SAMSUNG    CL32A227MQVNNNE")
        (field (name "DB_APPROVED_BY") "VSN")
      )
      (libsource (lib "Database_Libs1") (part "C"))
    )
    (comp (ref "C344")
      (value "C")
      (footprint "SMD_1210_CAPC3225X279N")
      (fields
        (field (name "DB_PART_NUMBER") "CAP000047355")
        (field (name "DB_VALUE") "220uF")
        (field (name "DB_TOLERANCE") "20%")
        (field (name "DB_VOLTAGE") "6.3V")
        (field (name "DB_MANUFACTURER_PART") "SAMSUNG    CL32A227MQVNNNE")
        (field (name "DB_APPROVED_BY") "VSN")
      )
      (libsource (lib "Database_Libs1") (part "C"))
    )
    (comp (ref "C345")
      (value "C")
      (footprint "SMD_1210_CAPC3225X279N")
      (fields
        (field (name "DB_PART_NUMBER") "CAP000047355")
        (field (name "DB_VALUE") "220uF")
        (field (name "DB_TOLERANCE") "20%")
        (field (name "DB_VOLTAGE") "6.3V")
        (field (name "DB_MANUFACTURER_PART") "SAMSUNG    CL32A227MQVNNNE")
        (field (name "DB_APPROVED_BY") "VSN")
      )
      (libsource (lib "Database_Libs1") (part "C"))
    )
    (comp (ref "C346")
      (value "C")
      (footprint "SMD_1210_CAPC3225X279N")
      (fields
        (field (name "DB_PART_NUMBER") "CAP000047355")
        (field (name "DB_VALUE") "220uF")
        (field (name "DB_TOLERANCE") "20%")
        (field (name "DB_VOLTAGE") "6.3V")
        (field (name "DB_MANUFACTURER_PART") "SAMSUNG    CL32A227MQVNNNE")
        (field (name "DB_APPROVED_BY") "VSN")
      )
      (libsource (lib "Database_Libs1") (part "C"))
    )
    (comp (ref "U2") (value "Golden_Nonce") (libsource (lib "Schlib1") (part "Golden_Nonce")))
  )
  (nets
    (net (code "1") (name "1V") (class "Default")
      (node (ref "C267") (pin "2") (pinfunction "2_2") (pintype "passive"))
      (node (ref "C268") (pin "2") (pinfunction "2_2") (pintype "passive"))
      (node (ref "C269") (pin "2") (pinfunction "2_2") (pintype "passive"))
      (node (ref "C270") (pin "2") (pinfunction "2_2") (pintype "passive"))
      (node (ref "C271") (pin "2") (pinfunction "2_2") (pintype "passive"))
      (node (ref "C272") (pin "2") (pinfunction "2_2") (pintype "passive"))
      (node (ref "C273") (pin "2") (pinfunction "2_2") (pintype "passive"))
      (node (ref "C274") (pin "2") (pinfunction "2_2") (pintype "passive"))
      (node (ref "C275") (pin "2") (pinfunction "2_2") (pintype "passive"))
      (node (ref "C276") (pin "2") (pinfunction "2_2") (pintype "passive"))
      (node (ref "C277") (pin "2") (pinfunction "2_2") (pintype "passive"))
      (node (ref "C278") (pin "2") (pinfunction "2_2") (pintype "passive"))
      (node (ref "C279") (pin "2") (pinfunction "2_2") (pintype "passive"))
      (node (ref "C280") (pin "2") (pinfunction "2_2") (pintype "passive"))
      (node (ref "C281") (pin "2") (pinfunction "2_2") (pintype "passive"))
      (node (ref "C282") (pin "2") (pinfunction "2_2") (pintype "passive"))
      (node (ref "C283") (pin "2") (pinfunction "2_2") (pintype "passive"))
      (node (ref "C284") (pin "2") (pinfunction "2_2") (pintype "passive"))
      (node (ref "C285") (pin "2") (pinfunction "2_2") (pintype "passive"))
      (node (ref "C286") (pin "2") (pinfunction "2_2") (pintype "passive"))
      (node (ref "C287") (pin "2") (pinfunction "2_2") (pintype "passive"))
      (node (ref "C288") (pin "2") (pinfunction "2_2") (pintype "passive"))
      (node (ref "C289") (pin "2") (pinfunction "2_2") (pintype "passive"))
      (node (ref "C290") (pin "2") (pinfunction "2_2") (pintype "passive"))
      (node (ref "C291") (pin "2") (pinfunction "2_2") (pintype "passive"))
      (node (ref "C292") (pin "2") (pinfunction "2_2") (pintype "passive"))
      (node (ref "C293") (pin "2") (pinfunction "2_2") (pintype "passive"))
      (node (ref "C294") (pin "2") (pinfunction "2_2") (pintype "passive"))
      (node (ref "C295") (pin "2") (pinfunction "2_2") (pintype "passive"))
      (node (ref "C296") (pin "2") (pinfunction "2_2") (pintype "passive"))
      (node (ref "C297") (pin "2") (pinfunction "2_2") (pintype "passive"))
      (node (ref "C298") (pin "2") (pinfunction "2_2") (pintype "passive"))
      (node (ref "C299") (pin "2") (pinfunction "2_2") (pintype "passive"))
      (node (ref "C300") (pin "2") (pinfunction "2_2") (pintype "passive"))
      (node (ref "C301") (pin "2") (pinfunction "2_2") (pintype "passive"))
      (node (ref "C302") (pin "2") (pinfunction "2_2") (pintype "passive"))
      (node (ref "C303") (pin "2") (pinfunction "2_2") (pintype "passive"))
      (node (ref "C304") (pin "2") (pinfunction "2_2") (pintype "passive"))
      (node (ref "C305") (pin "2") (pinfunction "2_2") (pintype "passive"))
      (node (ref "C306") (pin "2") (pinfunction "2_2") (pintype "passive"))
      (node (ref "C307") (pin "2") (pinfunction "2_2") (pintype "passive"))
      (node (ref "C308") (pin "2") (pinfunction "2_2") (pintype "passive"))
      (node (ref "C309") (pin "2") (pinfunction "2_2") (pintype "passive"))
      (node (ref "C310") (pin "2") (pinfunction "2_2") (pintype "passive"))
      (node (ref "C311") (pin "2") (pinfunction "2_2") (pintype "passive"))
      (node (ref "C312") (pin "2") (pinfunction "2_2") (pintype "passive"))
      (node (ref "C313") (pin "2") (pinfunction "2_2") (pintype "passive"))
      (node (ref "C314") (pin "2") (pinfunction "2_2") (pintype "passive"))
      (node (ref "C315") (pin "2") (pinfunction "2_2") (pintype "passive"))
      (node (ref "C316") (pin "2") (pinfunction "2_2") (pintype "passive"))
      (node (ref "C317") (pin "2") (pinfunction "2_2") (pintype "passive"))
      (node (ref "C318") (pin "2") (pinfunction "2_2") (pintype "passive"))
      (node (ref "C319") (pin "2") (pinfunction "2_2") (pintype "passive"))
      (node (ref "C320") (pin "2") (pinfunction "2_2") (pintype "passive"))
      (node (ref "C321") (pin "2") (pinfunction "2_2") (pintype "passive"))
      (node (ref "C322") (pin "2") (pinfunction "2_2") (pintype "passive"))
      (node (ref "C323") (pin "2") (pinfunction "2_2") (pintype "passive"))
      (node (ref "C324") (pin "2") (pinfunction "2_2") (pintype "passive"))
      (node (ref "C325") (pin "2") (pinfunction "2_2") (pintype "passive"))
      (node (ref "C326") (pin "2") (pinfunction "2_2") (pintype "passive"))
      (node (ref "C327") (pin "2") (pinfunction "2_2") (pintype "passive"))
      (node (ref "C328") (pin "2") (pinfunction "2_2") (pintype "passive"))
      (node (ref "C329") (pin "2") (pinfunction "2_2") (pintype "passive"))
      (node (ref "C330") (pin "2") (pinfunction "2_2") (pintype "passive"))
      (node (ref "C331") (pin "2") (pinfunction "2_2") (pintype "passive"))
      (node (ref "C332") (pin "2") (pinfunction "2_2") (pintype "passive"))
      (node (ref "C333") (pin "2") (pinfunction "2_2") (pintype "passive"))
      (node (ref "C334") (pin "2") (pinfunction "2_2") (pintype "passive"))
      (node (ref "C335") (pin "2") (pinfunction "2_2") (pintype "passive"))
      (node (ref "C336") (pin "2") (pinfunction "2_2") (pintype "passive"))
      (node (ref "C337") (pin "2") (pinfunction "2_2") (pintype "passive"))
      (node (ref "C338") (pin "2") (pinfunction "2_2") (pintype "passive"))
      (node (ref "C339") (pin "2") (pinfunction "2_2") (pintype "passive"))
      (node (ref "C340") (pin "2") (pinfunction "2_2") (pintype "passive"))
      (node (ref "C341") (pin "2") (pinfunction "2_2") (pintype "passive"))
      (node (ref "C342") (pin "2") (pinfunction "2_2") (pintype "passive"))
      (node (ref "C343") (pin "2") (pinfunction "2_2") (pintype "passive"))
      (node (ref "C344") (pin "2") (pinfunction "2_2") (pintype "passive"))
      (node (ref "C345") (pin "2") (pinfunction "2_2") (pintype "passive"))
      (node (ref "C346") (pin "2") (pinfunction "2_2") (pintype "passive"))
      (node (ref "U2") (pin "A2") (pinfunction "VDD_D1_A2") (pintype "passive"))
      (node (ref "U2") (pin "A22") (pinfunction "VDD_D1_A22") (pintype "passive"))
      (node (ref "U2") (pin "A23") (pinfunction "VDD_D2_A23") (pintype "passive"))
      (node (ref "U2") (pin "A37") (pinfunction "VDD_D2_A37") (pintype "passive"))
      (node (ref "U2") (pin "A39") (pinfunction "VDD_D2_A39") (pintype "passive"))
      (node (ref "U2") (pin "A4") (pinfunction "VDD_D1_A4") (pintype "passive"))
      (node (ref "U2") (pin "A41") (pinfunction "VDD_D2_A41") (pintype "passive"))
      (node (ref "U2") (pin "A43") (pinfunction "VDD_D2_A43") (pintype "passive"))
      (node (ref "U2") (pin "A6") (pinfunction "VDD_D1_A6") (pintype "passive"))
      (node (ref "U2") (pin "A8") (pinfunction "VDD_D1_A8") (pintype "passive"))
      (node (ref "U2") (pin "AA10") (pinfunction "VDD_D1_AA10") (pintype "passive"))
      (node (ref "U2") (pin "AA12") (pinfunction "VDD_D1_AA12") (pintype "passive"))
      (node (ref "U2") (pin "AA14") (pinfunction "VDD_D1_AA14") (pintype "passive"))
      (node (ref "U2") (pin "AA16") (pinfunction "VDD_D1_AA16") (pintype "passive"))
      (node (ref "U2") (pin "AA18") (pinfunction "VDD_D1_AA18") (pintype "passive"))
      (node (ref "U2") (pin "AA2") (pinfunction "VDD_D1_AA2") (pintype "passive"))
      (node (ref "U2") (pin "AA20") (pinfunction "VDD_D1_AA20") (pintype "passive"))
      (node (ref "U2") (pin "AA22") (pinfunction "VDD_D1_AA22") (pintype "passive"))
      (node (ref "U2") (pin "AA23") (pinfunction "VDD_D2_AA23") (pintype "passive"))
      (node (ref "U2") (pin "AA25") (pinfunction "VDD_D2_AA25") (pintype "passive"))
      (node (ref "U2") (pin "AA27") (pinfunction "VDD_D2_AA27") (pintype "passive"))
      (node (ref "U2") (pin "AA29") (pinfunction "VDD_D2_AA29") (pintype "passive"))
      (node (ref "U2") (pin "AA31") (pinfunction "VDD_D2_AA31") (pintype "passive"))
      (node (ref "U2") (pin "AA33") (pinfunction "VDD_D2_AA33") (pintype "passive"))
      (node (ref "U2") (pin "AA35") (pinfunction "VDD_D2_AA35") (pintype "passive"))
      (node (ref "U2") (pin "AA37") (pinfunction "VDD_D2_AA37") (pintype "passive"))
      (node (ref "U2") (pin "AA39") (pinfunction "VDD_D2_AA39") (pintype "passive"))
      (node (ref "U2") (pin "AA4") (pinfunction "VDD_D1_AA4") (pintype "passive"))
      (node (ref "U2") (pin "AA41") (pinfunction "VDD_D2_AA41") (pintype "passive"))
      (node (ref "U2") (pin "AA43") (pinfunction "VDD_D2_AA43") (pintype "passive"))
      (node (ref "U2") (pin "AA6") (pinfunction "VDD_D1_AA6") (pintype "passive"))
      (node (ref "U2") (pin "AA8") (pinfunction "VDD_D1_AA8") (pintype "passive"))
      (node (ref "U2") (pin "AB1") (pinfunction "VDD_D1_AB1") (pintype "passive"))
      (node (ref "U2") (pin "AB11") (pinfunction "VDD_D1_AB11") (pintype "passive"))
      (node (ref "U2") (pin "AB13") (pinfunction "VDD_D1_AB13") (pintype "passive"))
      (node (ref "U2") (pin "AB15") (pinfunction "VDD_D1_AB15") (pintype "passive"))
      (node (ref "U2") (pin "AB17") (pinfunction "VDD_D1_AB17") (pintype "passive"))
      (node (ref "U2") (pin "AB19") (pinfunction "VDD_D1_AB19") (pintype "passive"))
      (node (ref "U2") (pin "AB21") (pinfunction "VDD_D1_AB21") (pintype "passive"))
      (node (ref "U2") (pin "AB24") (pinfunction "VDD_D2_AB24") (pintype "passive"))
      (node (ref "U2") (pin "AB26") (pinfunction "VDD_D2_AB26") (pintype "passive"))
      (node (ref "U2") (pin "AB28") (pinfunction "VDD_D2_AB28") (pintype "passive"))
      (node (ref "U2") (pin "AB3") (pinfunction "VDD_D1_AB3") (pintype "passive"))
      (node (ref "U2") (pin "AB30") (pinfunction "VDD_D2_AB30") (pintype "passive"))
      (node (ref "U2") (pin "AB32") (pinfunction "VDD_D2_AB32") (pintype "passive"))
      (node (ref "U2") (pin "AB34") (pinfunction "VDD_D2_AB34") (pintype "passive"))
      (node (ref "U2") (pin "AB36") (pinfunction "VDD_D2_AB36") (pintype "passive"))
      (node (ref "U2") (pin "AB38") (pinfunction "VDD_D2_AB38") (pintype "passive"))
      (node (ref "U2") (pin "AB40") (pinfunction "VDD_D2_AB40") (pintype "passive"))
      (node (ref "U2") (pin "AB42") (pinfunction "VDD_D2_AB42") (pintype "passive"))
      (node (ref "U2") (pin "AB44") (pinfunction "VDD_D2_AB44") (pintype "passive"))
      (node (ref "U2") (pin "AB5") (pinfunction "VDD_D1_AB5") (pintype "passive"))
      (node (ref "U2") (pin "AB7") (pinfunction "VDD_D1_AB7") (pintype "passive"))
      (node (ref "U2") (pin "AB9") (pinfunction "VDD_D1_AB9") (pintype "passive"))
      (node (ref "U2") (pin "AC1") (pinfunction "VDD_D4_AC1") (pintype "passive"))
      (node (ref "U2") (pin "AC11") (pinfunction "VDD_D4_AC11") (pintype "passive"))
      (node (ref "U2") (pin "AC13") (pinfunction "VDD_D4_AC13") (pintype "passive"))
      (node (ref "U2") (pin "AC15") (pinfunction "VDD_D4_AC15") (pintype "passive"))
      (node (ref "U2") (pin "AC17") (pinfunction "VDD_D4_AC17") (pintype "passive"))
      (node (ref "U2") (pin "AC19") (pinfunction "VDD_D4_AC19") (pintype "passive"))
      (node (ref "U2") (pin "AC21") (pinfunction "VDD_D4_AC21") (pintype "passive"))
      (node (ref "U2") (pin "AC3") (pinfunction "VDD_D4_AC3") (pintype "passive"))
      (node (ref "U2") (pin "AC32") (pinfunction "VDD_D3_AC32") (pintype "passive"))
      (node (ref "U2") (pin "AC42") (pinfunction "VDD_D3_AC42") (pintype "passive"))
      (node (ref "U2") (pin "AC5") (pinfunction "VDD_D4_AC5") (pintype "passive"))
      (node (ref "U2") (pin "AC7") (pinfunction "VDD_D4_AC7") (pintype "passive"))
      (node (ref "U2") (pin "AC9") (pinfunction "VDD_D4_AC9") (pintype "passive"))
      (node (ref "U2") (pin "AD10") (pinfunction "VDD_D4_AD10") (pintype "passive"))
      (node (ref "U2") (pin "AD12") (pinfunction "VDD_D4_AD12") (pintype "passive"))
      (node (ref "U2") (pin "AD14") (pinfunction "VDD_D4_AD14") (pintype "passive"))
      (node (ref "U2") (pin "AD16") (pinfunction "VDD_D4_AD16") (pintype "passive"))
      (node (ref "U2") (pin "AD18") (pinfunction "VDD_D4_AD18") (pintype "passive"))
      (node (ref "U2") (pin "AD2") (pinfunction "VDD_D4_AD2") (pintype "passive"))
      (node (ref "U2") (pin "AD20") (pinfunction "VDD_D4_AD20") (pintype "passive"))
      (node (ref "U2") (pin "AD22") (pinfunction "VDD_D4_AD22") (pintype "passive"))
      (node (ref "U2") (pin "AD29") (pinfunction "VDD_D3_AD29") (pintype "passive"))
      (node (ref "U2") (pin "AD4") (pinfunction "VDD_D4_AD4") (pintype "passive"))
      (node (ref "U2") (pin "AD6") (pinfunction "VDD_D4_AD6") (pintype "passive"))
      (node (ref "U2") (pin "AD8") (pinfunction "VDD_D4_AD8") (pintype "passive"))
      (node (ref "U2") (pin "AE1") (pinfunction "VDD_D4_AE1") (pintype "passive"))
      (node (ref "U2") (pin "AE11") (pinfunction "VDD_D4_AE11") (pintype "passive"))
      (node (ref "U2") (pin "AE13") (pinfunction "VDD_D4_AE13") (pintype "passive"))
      (node (ref "U2") (pin "AE15") (pinfunction "VDD_D4_AE15") (pintype "passive"))
      (node (ref "U2") (pin "AE17") (pinfunction "VDD_D4_AE17") (pintype "passive"))
      (node (ref "U2") (pin "AE19") (pinfunction "VDD_D4_AE19") (pintype "passive"))
      (node (ref "U2") (pin "AE21") (pinfunction "VDD_D4_AE21") (pintype "passive"))
      (node (ref "U2") (pin "AE3") (pinfunction "VDD_D4_AE3") (pintype "passive"))
      (node (ref "U2") (pin "AE30") (pinfunction "VDD_D3_AE30") (pintype "passive"))
      (node (ref "U2") (pin "AE5") (pinfunction "VDD_D4_AE5") (pintype "passive"))
      (node (ref "U2") (pin "AE7") (pinfunction "VDD_D4_AE7") (pintype "passive"))
      (node (ref "U2") (pin "AE9") (pinfunction "VDD_D4_AE9") (pintype "passive"))
      (node (ref "U2") (pin "AF10") (pinfunction "VDD_D4_AF10") (pintype "passive"))
      (node (ref "U2") (pin "AF12") (pinfunction "VDD_D4_AF12") (pintype "passive"))
      (node (ref "U2") (pin "AF14") (pinfunction "VDD_D4_AF14") (pintype "passive"))
      (node (ref "U2") (pin "AF16") (pinfunction "VDD_D4_AF16") (pintype "passive"))
      (node (ref "U2") (pin "AF18") (pinfunction "VDD_D4_AF18") (pintype "passive"))
      (node (ref "U2") (pin "AF2") (pinfunction "VDD_D4_AF2") (pintype "passive"))
      (node (ref "U2") (pin "AF20") (pinfunction "VDD_D4_AF20") (pintype "passive"))
      (node (ref "U2") (pin "AF22") (pinfunction "VDD_D4_AF22") (pintype "passive"))
      (node (ref "U2") (pin "AF29") (pinfunction "VDD_D3_AF29") (pintype "passive"))
      (node (ref "U2") (pin "AF4") (pinfunction "VDD_D4_AF4") (pintype "passive"))
      (node (ref "U2") (pin "AF6") (pinfunction "VDD_D4_AF6") (pintype "passive"))
      (node (ref "U2") (pin "AF8") (pinfunction "VDD_D4_AF8") (pintype "passive"))
      (node (ref "U2") (pin "AG1") (pinfunction "VDD_D4_AG1") (pintype "passive"))
      (node (ref "U2") (pin "AG11") (pinfunction "VDD_D4_AG11") (pintype "passive"))
      (node (ref "U2") (pin "AG13") (pinfunction "VDD_D4_AG13") (pintype "passive"))
      (node (ref "U2") (pin "AG15") (pinfunction "VDD_D4_AG15") (pintype "passive"))
      (node (ref "U2") (pin "AG17") (pinfunction "VDD_D4_AG17") (pintype "passive"))
      (node (ref "U2") (pin "AG19") (pinfunction "VDD_D4_AG19") (pintype "passive"))
      (node (ref "U2") (pin "AG21") (pinfunction "VDD_D4_AG21") (pintype "passive"))
      (node (ref "U2") (pin "AG3") (pinfunction "VDD_D4_AG3") (pintype "passive"))
      (node (ref "U2") (pin "AG30") (pinfunction "VDD_D3_AG30") (pintype "passive"))
      (node (ref "U2") (pin "AG5") (pinfunction "VDD_D4_AG5") (pintype "passive"))
      (node (ref "U2") (pin "AG7") (pinfunction "VDD_D4_AG7") (pintype "passive"))
      (node (ref "U2") (pin "AG9") (pinfunction "VDD_D4_AG9") (pintype "passive"))
      (node (ref "U2") (pin "AH10") (pinfunction "VDD_D4_AH10") (pintype "passive"))
      (node (ref "U2") (pin "AH12") (pinfunction "VDD_D4_AH12") (pintype "passive"))
      (node (ref "U2") (pin "AH14") (pinfunction "VDD_D4_AH14") (pintype "passive"))
      (node (ref "U2") (pin "AH16") (pinfunction "VDD_D4_AH16") (pintype "passive"))
      (node (ref "U2") (pin "AH18") (pinfunction "VDD_D4_AH18") (pintype "passive"))
      (node (ref "U2") (pin "AH2") (pinfunction "VDD_D4_AH2") (pintype "passive"))
      (node (ref "U2") (pin "AH20") (pinfunction "VDD_D4_AH20") (pintype "passive"))
      (node (ref "U2") (pin "AH22") (pinfunction "VDD_D4_AH22") (pintype "passive"))
      (node (ref "U2") (pin "AH29") (pinfunction "VDD_D3_AH29") (pintype "passive"))
      (node (ref "U2") (pin "AH4") (pinfunction "VDD_D4_AH4") (pintype "passive"))
      (node (ref "U2") (pin "AH6") (pinfunction "VDD_D4_AH6") (pintype "passive"))
      (node (ref "U2") (pin "AH8") (pinfunction "VDD_D4_AH8") (pintype "passive"))
      (node (ref "U2") (pin "AJ1") (pinfunction "VDD_D4_AJ1") (pintype "passive"))
      (node (ref "U2") (pin "AJ11") (pinfunction "VDD_D4_AJ11") (pintype "passive"))
      (node (ref "U2") (pin "AJ13") (pinfunction "VDD_D4_AJ13") (pintype "passive"))
      (node (ref "U2") (pin "AJ15") (pinfunction "VDD_D4_AJ15") (pintype "passive"))
      (node (ref "U2") (pin "AJ17") (pinfunction "VDD_D4_AJ17") (pintype "passive"))
      (node (ref "U2") (pin "AJ19") (pinfunction "VDD_D4_AJ19") (pintype "passive"))
      (node (ref "U2") (pin "AJ21") (pinfunction "VDD_D4_AJ21") (pintype "passive"))
      (node (ref "U2") (pin "AJ3") (pinfunction "VDD_D4_AJ3") (pintype "passive"))
      (node (ref "U2") (pin "AJ30") (pinfunction "VDD_D3_AJ30") (pintype "passive"))
      (node (ref "U2") (pin "AJ5") (pinfunction "VDD_D4_AJ5") (pintype "passive"))
      (node (ref "U2") (pin "AJ7") (pinfunction "VDD_D4_AJ7") (pintype "passive"))
      (node (ref "U2") (pin "AJ9") (pinfunction "VDD_D4_AJ9") (pintype "passive"))
      (node (ref "U2") (pin "AK10") (pinfunction "VDD_D4_AK10") (pintype "passive"))
      (node (ref "U2") (pin "AK12") (pinfunction "VDD_D4_AK12") (pintype "passive"))
      (node (ref "U2") (pin "AK14") (pinfunction "VDD_D4_AK14") (pintype "passive"))
      (node (ref "U2") (pin "AK16") (pinfunction "VDD_D4_AK16") (pintype "passive"))
      (node (ref "U2") (pin "AK18") (pinfunction "VDD_D4_AK18") (pintype "passive"))
      (node (ref "U2") (pin "AK2") (pinfunction "VDD_D4_AK2") (pintype "passive"))
      (node (ref "U2") (pin "AK20") (pinfunction "VDD_D4_AK20") (pintype "passive"))
      (node (ref "U2") (pin "AK22") (pinfunction "VDD_D4_AK22") (pintype "passive"))
      (node (ref "U2") (pin "AK25") (pinfunction "VDD_D3_AK25") (pintype "passive"))
      (node (ref "U2") (pin "AK29") (pinfunction "VDD_D3_AK29") (pintype "passive"))
      (node (ref "U2") (pin "AK4") (pinfunction "VDD_D4_AK4") (pintype "passive"))
      (node (ref "U2") (pin "AK6") (pinfunction "VDD_D4_AK6") (pintype "passive"))
      (node (ref "U2") (pin "AK8") (pinfunction "VDD_D4_AK8") (pintype "passive"))
      (node (ref "U2") (pin "AL1") (pinfunction "VDD_D4_AL1") (pintype "passive"))
      (node (ref "U2") (pin "AL11") (pinfunction "VDD_D4_AL11") (pintype "passive"))
      (node (ref "U2") (pin "AL13") (pinfunction "VDD_D4_AL13") (pintype "passive"))
      (node (ref "U2") (pin "AL15") (pinfunction "VDD_D4_AL15") (pintype "passive"))
      (node (ref "U2") (pin "AL17") (pinfunction "VDD_D4_AL17") (pintype "passive"))
      (node (ref "U2") (pin "AL19") (pinfunction "VDD_D4_AL19") (pintype "passive"))
      (node (ref "U2") (pin "AL21") (pinfunction "VDD_D4_AL21") (pintype "passive"))
      (node (ref "U2") (pin "AL3") (pinfunction "VDD_D4_AL3") (pintype "passive"))
      (node (ref "U2") (pin "AL30") (pinfunction "VDD_D3_AL30") (pintype "passive"))
      (node (ref "U2") (pin "AL5") (pinfunction "VDD_D4_AL5") (pintype "passive"))
      (node (ref "U2") (pin "AL7") (pinfunction "VDD_D4_AL7") (pintype "passive"))
      (node (ref "U2") (pin "AL9") (pinfunction "VDD_D4_AL9") (pintype "passive"))
      (node (ref "U2") (pin "AM10") (pinfunction "VDD_D4_AM10") (pintype "passive"))
      (node (ref "U2") (pin "AM12") (pinfunction "VDD_D4_AM12") (pintype "passive"))
      (node (ref "U2") (pin "AM14") (pinfunction "VDD_D4_AM14") (pintype "passive"))
      (node (ref "U2") (pin "AM16") (pinfunction "VDD_D4_AM16") (pintype "passive"))
      (node (ref "U2") (pin "AM18") (pinfunction "VDD_D4_AM18") (pintype "passive"))
      (node (ref "U2") (pin "AM2") (pinfunction "VDD_D4_AM2") (pintype "passive"))
      (node (ref "U2") (pin "AM20") (pinfunction "VDD_D4_AM20") (pintype "passive"))
      (node (ref "U2") (pin "AM22") (pinfunction "VDD_D4_AM22") (pintype "passive"))
      (node (ref "U2") (pin "AM29") (pinfunction "VDD_D3_AM29") (pintype "passive"))
      (node (ref "U2") (pin "AM4") (pinfunction "VDD_D4_AM4") (pintype "passive"))
      (node (ref "U2") (pin "AM6") (pinfunction "VDD_D4_AM6") (pintype "passive"))
      (node (ref "U2") (pin "AM8") (pinfunction "VDD_D4_AM8") (pintype "passive"))
      (node (ref "U2") (pin "AN15") (pinfunction "VDD_D4_AN15") (pintype "passive"))
      (node (ref "U2") (pin "AN17") (pinfunction "VDD_D4_AN17") (pintype "passive"))
      (node (ref "U2") (pin "AN19") (pinfunction "VDD_D4_AN19") (pintype "passive"))
      (node (ref "U2") (pin "AN21") (pinfunction "VDD_D4_AN21") (pintype "passive"))
      (node (ref "U2") (pin "AN24") (pinfunction "VDD_D3_AN24") (pintype "passive"))
      (node (ref "U2") (pin "AN26") (pinfunction "VDD_D3_AN26") (pintype "passive"))
      (node (ref "U2") (pin "AN28") (pinfunction "VDD_D3_AN28") (pintype "passive"))
      (node (ref "U2") (pin "AN30") (pinfunction "VDD_D3_AN30") (pintype "passive"))
      (node (ref "U2") (pin "AN32") (pinfunction "VDD_D3_AN32") (pintype "passive"))
      (node (ref "U2") (pin "AN34") (pinfunction "VDD_D3_AN34") (pintype "passive"))
      (node (ref "U2") (pin "AN36") (pinfunction "VDD_D3_AN36") (pintype "passive"))
      (node (ref "U2") (pin "AN38") (pinfunction "VDD_D3_AN38") (pintype "passive"))
      (node (ref "U2") (pin "AN40") (pinfunction "VDD_D3_AN40") (pintype "passive"))
      (node (ref "U2") (pin "AN42") (pinfunction "VDD_D3_AN42") (pintype "passive"))
      (node (ref "U2") (pin "AN44") (pinfunction "VDD_D3_AN44") (pintype "passive"))
      (node (ref "U2") (pin "AP16") (pinfunction "VDD_D4_AP16") (pintype "passive"))
      (node (ref "U2") (pin "AP23") (pinfunction "VDD_D3_AP23") (pintype "passive"))
      (node (ref "U2") (pin "AP25") (pinfunction "VDD_D3_AP25") (pintype "passive"))
      (node (ref "U2") (pin "AP27") (pinfunction "VDD_D3_AP27") (pintype "passive"))
      (node (ref "U2") (pin "AP29") (pinfunction "VDD_D3_AP29") (pintype "passive"))
      (node (ref "U2") (pin "AP31") (pinfunction "VDD_D3_AP31") (pintype "passive"))
      (node (ref "U2") (pin "AP33") (pinfunction "VDD_D3_AP33") (pintype "passive"))
      (node (ref "U2") (pin "AP35") (pinfunction "VDD_D3_AP35") (pintype "passive"))
      (node (ref "U2") (pin "AP37") (pinfunction "VDD_D3_AP37") (pintype "passive"))
      (node (ref "U2") (pin "AP39") (pinfunction "VDD_D3_AP39") (pintype "passive"))
      (node (ref "U2") (pin "AP41") (pinfunction "VDD_D3_AP41") (pintype "passive"))
      (node (ref "U2") (pin "AP43") (pinfunction "VDD_D3_AP43") (pintype "passive"))
      (node (ref "U2") (pin "AR15") (pinfunction "VDD_D4_AR15") (pintype "passive"))
      (node (ref "U2") (pin "AR24") (pinfunction "VDD_D3_AR24") (pintype "passive"))
      (node (ref "U2") (pin "AR26") (pinfunction "VDD_D3_AR26") (pintype "passive"))
      (node (ref "U2") (pin "AR28") (pinfunction "VDD_D3_AR28") (pintype "passive"))
      (node (ref "U2") (pin "AR30") (pinfunction "VDD_D3_AR30") (pintype "passive"))
      (node (ref "U2") (pin "AR32") (pinfunction "VDD_D3_AR32") (pintype "passive"))
      (node (ref "U2") (pin "AR34") (pinfunction "VDD_D3_AR34") (pintype "passive"))
      (node (ref "U2") (pin "AR36") (pinfunction "VDD_D3_AR36") (pintype "passive"))
      (node (ref "U2") (pin "AR38") (pinfunction "VDD_D3_AR38") (pintype "passive"))
      (node (ref "U2") (pin "AR40") (pinfunction "VDD_D3_AR40") (pintype "passive"))
      (node (ref "U2") (pin "AR42") (pinfunction "VDD_D3_AR42") (pintype "passive"))
      (node (ref "U2") (pin "AR44") (pinfunction "VDD_D3_AR44") (pintype "passive"))
      (node (ref "U2") (pin "AT16") (pinfunction "VDD_D4_AT16") (pintype "passive"))
      (node (ref "U2") (pin "AT20") (pinfunction "VDD_D4_AT20") (pintype "passive"))
      (node (ref "U2") (pin "AT23") (pinfunction "VDD_D3_AT23") (pintype "passive"))
      (node (ref "U2") (pin "AT25") (pinfunction "VDD_D3_AT25") (pintype "passive"))
      (node (ref "U2") (pin "AT27") (pinfunction "VDD_D3_AT27") (pintype "passive"))
      (node (ref "U2") (pin "AT29") (pinfunction "VDD_D3_AT29") (pintype "passive"))
      (node (ref "U2") (pin "AT31") (pinfunction "VDD_D3_AT31") (pintype "passive"))
      (node (ref "U2") (pin "AT33") (pinfunction "VDD_D3_AT33") (pintype "passive"))
      (node (ref "U2") (pin "AT35") (pinfunction "VDD_D3_AT35") (pintype "passive"))
      (node (ref "U2") (pin "AT37") (pinfunction "VDD_D3_AT37") (pintype "passive"))
      (node (ref "U2") (pin "AT39") (pinfunction "VDD_D3_AT39") (pintype "passive"))
      (node (ref "U2") (pin "AT41") (pinfunction "VDD_D3_AT41") (pintype "passive"))
      (node (ref "U2") (pin "AT43") (pinfunction "VDD_D3_AT43") (pintype "passive"))
      (node (ref "U2") (pin "AU15") (pinfunction "VDD_D4_AU15") (pintype "passive"))
      (node (ref "U2") (pin "AU24") (pinfunction "VDD_D3_AU24") (pintype "passive"))
      (node (ref "U2") (pin "AU26") (pinfunction "VDD_D3_AU26") (pintype "passive"))
      (node (ref "U2") (pin "AU28") (pinfunction "VDD_D3_AU28") (pintype "passive"))
      (node (ref "U2") (pin "AU30") (pinfunction "VDD_D3_AU30") (pintype "passive"))
      (node (ref "U2") (pin "AU32") (pinfunction "VDD_D3_AU32") (pintype "passive"))
      (node (ref "U2") (pin "AU34") (pinfunction "VDD_D3_AU34") (pintype "passive"))
      (node (ref "U2") (pin "AU36") (pinfunction "VDD_D3_AU36") (pintype "passive"))
      (node (ref "U2") (pin "AU38") (pinfunction "VDD_D3_AU38") (pintype "passive"))
      (node (ref "U2") (pin "AU40") (pinfunction "VDD_D3_AU40") (pintype "passive"))
      (node (ref "U2") (pin "AU42") (pinfunction "VDD_D3_AU42") (pintype "passive"))
      (node (ref "U2") (pin "AU44") (pinfunction "VDD_D3_AU44") (pintype "passive"))
      (node (ref "U2") (pin "AV16") (pinfunction "VDD_D4_AV16") (pintype "passive"))
      (node (ref "U2") (pin "AV23") (pinfunction "VDD_D3_AV23") (pintype "passive"))
      (node (ref "U2") (pin "AV25") (pinfunction "VDD_D3_AV25") (pintype "passive"))
      (node (ref "U2") (pin "AV27") (pinfunction "VDD_D3_AV27") (pintype "passive"))
      (node (ref "U2") (pin "AV29") (pinfunction "VDD_D3_AV29") (pintype "passive"))
      (node (ref "U2") (pin "AV31") (pinfunction "VDD_D3_AV31") (pintype "passive"))
      (node (ref "U2") (pin "AV33") (pinfunction "VDD_D3_AV33") (pintype "passive"))
      (node (ref "U2") (pin "AV35") (pinfunction "VDD_D3_AV35") (pintype "passive"))
      (node (ref "U2") (pin "AV37") (pinfunction "VDD_D3_AV37") (pintype "passive"))
      (node (ref "U2") (pin "AV39") (pinfunction "VDD_D3_AV39") (pintype "passive"))
      (node (ref "U2") (pin "AV41") (pinfunction "VDD_D3_AV41") (pintype "passive"))
      (node (ref "U2") (pin "AV43") (pinfunction "VDD_D3_AV43") (pintype "passive"))
      (node (ref "U2") (pin "AW15") (pinfunction "VDD_D4_AW15") (pintype "passive"))
      (node (ref "U2") (pin "AW24") (pinfunction "VDD_D3_AW24") (pintype "passive"))
      (node (ref "U2") (pin "AW26") (pinfunction "VDD_D3_AW26") (pintype "passive"))
      (node (ref "U2") (pin "AW28") (pinfunction "VDD_D3_AW28") (pintype "passive"))
      (node (ref "U2") (pin "AW30") (pinfunction "VDD_D3_AW30") (pintype "passive"))
      (node (ref "U2") (pin "AW32") (pinfunction "VDD_D3_AW32") (pintype "passive"))
      (node (ref "U2") (pin "AW34") (pinfunction "VDD_D3_AW34") (pintype "passive"))
      (node (ref "U2") (pin "AW36") (pinfunction "VDD_D3_AW36") (pintype "passive"))
      (node (ref "U2") (pin "AW38") (pinfunction "VDD_D3_AW38") (pintype "passive"))
      (node (ref "U2") (pin "AW40") (pinfunction "VDD_D3_AW40") (pintype "passive"))
      (node (ref "U2") (pin "AW42") (pinfunction "VDD_D3_AW42") (pintype "passive"))
      (node (ref "U2") (pin "AW44") (pinfunction "VDD_D3_AW44") (pintype "passive"))
      (node (ref "U2") (pin "AY16") (pinfunction "VDD_D4_AY16") (pintype "passive"))
      (node (ref "U2") (pin "AY23") (pinfunction "VDD_D3_AY23") (pintype "passive"))
      (node (ref "U2") (pin "AY25") (pinfunction "VDD_D3_AY25") (pintype "passive"))
      (node (ref "U2") (pin "AY29") (pinfunction "VDD_D3_AY29") (pintype "passive"))
      (node (ref "U2") (pin "AY31") (pinfunction "VDD_D3_AY31") (pintype "passive"))
      (node (ref "U2") (pin "AY33") (pinfunction "VDD_D3_AY33") (pintype "passive"))
      (node (ref "U2") (pin "AY35") (pinfunction "VDD_D3_AY35") (pintype "passive"))
      (node (ref "U2") (pin "AY37") (pinfunction "VDD_D3_AY37") (pintype "passive"))
      (node (ref "U2") (pin "AY39") (pinfunction "VDD_D3_AY39") (pintype "passive"))
      (node (ref "U2") (pin "AY41") (pinfunction "VDD_D3_AY41") (pintype "passive"))
      (node (ref "U2") (pin "AY43") (pinfunction "VDD_D3_AY43") (pintype "passive"))
      (node (ref "U2") (pin "B1") (pinfunction "VDD_D1_B1") (pintype "passive"))
      (node (ref "U2") (pin "B21") (pinfunction "VDD_D1_B21") (pintype "passive"))
      (node (ref "U2") (pin "B3") (pinfunction "VDD_D1_B3") (pintype "passive"))
      (node (ref "U2") (pin "B36") (pinfunction "VDD_D2_B36") (pintype "passive"))
      (node (ref "U2") (pin "B38") (pinfunction "VDD_D2_B38") (pintype "passive"))
      (node (ref "U2") (pin "B40") (pinfunction "VDD_D2_B40") (pintype "passive"))
      (node (ref "U2") (pin "B42") (pinfunction "VDD_D2_B42") (pintype "passive"))
      (node (ref "U2") (pin "B44") (pinfunction "VDD_D2_B44") (pintype "passive"))
      (node (ref "U2") (pin "B5") (pinfunction "VDD_D1_B5") (pintype "passive"))
      (node (ref "U2") (pin "B7") (pinfunction "VDD_D1_B7") (pintype "passive"))
      (node (ref "U2") (pin "BA15") (pinfunction "VDD_D4_BA15") (pintype "passive"))
      (node (ref "U2") (pin "BA24") (pinfunction "VDD_D3_BA24") (pintype "passive"))
      (node (ref "U2") (pin "BA26") (pinfunction "VDD_D3_BA26") (pintype "passive"))
      (node (ref "U2") (pin "BA28") (pinfunction "VDD_D3_BA28") (pintype "passive"))
      (node (ref "U2") (pin "BA30") (pinfunction "VDD_D3_BA30") (pintype "passive"))
      (node (ref "U2") (pin "BA32") (pinfunction "VDD_D3_BA32") (pintype "passive"))
      (node (ref "U2") (pin "BA34") (pinfunction "VDD_D3_BA34") (pintype "passive"))
      (node (ref "U2") (pin "BA36") (pinfunction "VDD_D3_BA36") (pintype "passive"))
      (node (ref "U2") (pin "BA38") (pinfunction "VDD_D3_BA38") (pintype "passive"))
      (node (ref "U2") (pin "BA40") (pinfunction "VDD_D3_BA40") (pintype "passive"))
      (node (ref "U2") (pin "BA42") (pinfunction "VDD_D3_BA42") (pintype "passive"))
      (node (ref "U2") (pin "BA44") (pinfunction "VDD_D3_BA44") (pintype "passive"))
      (node (ref "U2") (pin "BB23") (pinfunction "VDD_D3_BB23") (pintype "passive"))
      (node (ref "U2") (pin "BB37") (pinfunction "VDD_D3_BB37") (pintype "passive"))
      (node (ref "U2") (pin "BB39") (pinfunction "VDD_D3_BB39") (pintype "passive"))
      (node (ref "U2") (pin "BB4") (pinfunction "VDD_D4_BB4") (pintype "passive"))
      (node (ref "U2") (pin "BB41") (pinfunction "VDD_D3_BB41") (pintype "passive"))
      (node (ref "U2") (pin "BB43") (pinfunction "VDD_D3_BB43") (pintype "passive"))
      (node (ref "U2") (pin "BC24") (pinfunction "VDD_D3_BC24") (pintype "passive"))
      (node (ref "U2") (pin "BC38") (pinfunction "VDD_D3_BC38") (pintype "passive"))
      (node (ref "U2") (pin "BC40") (pinfunction "VDD_D3_BC40") (pintype "passive"))
      (node (ref "U2") (pin "BC42") (pinfunction "VDD_D3_BC42") (pintype "passive"))
      (node (ref "U2") (pin "BC44") (pinfunction "VDD_D3_BC44") (pintype "passive"))
      (node (ref "U2") (pin "BD23") (pinfunction "VDD_D3_BD23") (pintype "passive"))
      (node (ref "U2") (pin "BD37") (pinfunction "VDD_D3_BD37") (pintype "passive"))
      (node (ref "U2") (pin "BD39") (pinfunction "VDD_D3_BD39") (pintype "passive"))
      (node (ref "U2") (pin "BD41") (pinfunction "VDD_D3_BD41") (pintype "passive"))
      (node (ref "U2") (pin "BD43") (pinfunction "VDD_D3_BD43") (pintype "passive"))
      (node (ref "U2") (pin "C2") (pinfunction "VDD_D1_C2") (pintype "passive"))
      (node (ref "U2") (pin "C22") (pinfunction "VDD_D1_C22") (pintype "passive"))
      (node (ref "U2") (pin "C23") (pinfunction "VDD_D2_C23") (pintype "passive"))
      (node (ref "U2") (pin "C37") (pinfunction "VDD_D2_C37") (pintype "passive"))
      (node (ref "U2") (pin "C39") (pinfunction "VDD_D2_C39") (pintype "passive"))
      (node (ref "U2") (pin "C4") (pinfunction "VDD_D1_C4") (pintype "passive"))
      (node (ref "U2") (pin "C41") (pinfunction "VDD_D2_C41") (pintype "passive"))
      (node (ref "U2") (pin "C43") (pinfunction "VDD_D2_C43") (pintype "passive"))
      (node (ref "U2") (pin "C6") (pinfunction "VDD_D1_C6") (pintype "passive"))
      (node (ref "U2") (pin "C8") (pinfunction "VDD_D1_C8") (pintype "passive"))
      (node (ref "U2") (pin "D1") (pinfunction "VDD_D1_D1") (pintype "passive"))
      (node (ref "U2") (pin "D11") (pinfunction "VDD_D1_D11") (pintype "passive"))
      (node (ref "U2") (pin "D13") (pinfunction "VDD_D1_D13") (pintype "passive"))
      (node (ref "U2") (pin "D15") (pinfunction "VDD_D1_D15") (pintype "passive"))
      (node (ref "U2") (pin "D17") (pinfunction "VDD_D1_D17") (pintype "passive"))
      (node (ref "U2") (pin "D19") (pinfunction "VDD_D1_D19") (pintype "passive"))
      (node (ref "U2") (pin "D21") (pinfunction "VDD_D1_D21") (pintype "passive"))
      (node (ref "U2") (pin "D24") (pinfunction "VDD_D2_D24") (pintype "passive"))
      (node (ref "U2") (pin "D26") (pinfunction "VDD_D2_D26") (pintype "passive"))
      (node (ref "U2") (pin "D28") (pinfunction "VDD_D2_D28") (pintype "passive"))
      (node (ref "U2") (pin "D3") (pinfunction "VDD_D1_D3") (pintype "passive"))
      (node (ref "U2") (pin "D30") (pinfunction "VDD_D2_D30") (pintype "passive"))
      (node (ref "U2") (pin "D32") (pinfunction "VDD_D2_D32") (pintype "passive"))
      (node (ref "U2") (pin "D34") (pinfunction "VDD_D2_D34") (pintype "passive"))
      (node (ref "U2") (pin "D36") (pinfunction "VDD_D2_D36") (pintype "passive"))
      (node (ref "U2") (pin "D38") (pinfunction "VDD_D2_D38") (pintype "passive"))
      (node (ref "U2") (pin "D40") (pinfunction "VDD_D2_D40") (pintype "passive"))
      (node (ref "U2") (pin "D42") (pinfunction "VDD_D2_D42") (pintype "passive"))
      (node (ref "U2") (pin "D44") (pinfunction "VDD_D2_D44") (pintype "passive"))
      (node (ref "U2") (pin "D5") (pinfunction "VDD_D1_D5") (pintype "passive"))
      (node (ref "U2") (pin "D7") (pinfunction "VDD_D1_D7") (pintype "passive"))
      (node (ref "U2") (pin "D9") (pinfunction "VDD_D1_D9") (pintype "passive"))
      (node (ref "U2") (pin "E10") (pinfunction "VDD_D1_E10") (pintype "passive"))
      (node (ref "U2") (pin "E12") (pinfunction "VDD_D1_E12") (pintype "passive"))
      (node (ref "U2") (pin "E14") (pinfunction "VDD_D1_E14") (pintype "passive"))
      (node (ref "U2") (pin "E16") (pinfunction "VDD_D1_E16") (pintype "passive"))
      (node (ref "U2") (pin "E18") (pinfunction "VDD_D1_E18") (pintype "passive"))
      (node (ref "U2") (pin "E2") (pinfunction "VDD_D1_E2") (pintype "passive"))
      (node (ref "U2") (pin "E20") (pinfunction "VDD_D1_E20") (pintype "passive"))
      (node (ref "U2") (pin "E22") (pinfunction "VDD_D1_E22") (pintype "passive"))
      (node (ref "U2") (pin "E23") (pinfunction "VDD_D2_E23") (pintype "passive"))
      (node (ref "U2") (pin "E25") (pinfunction "VDD_D2_E25") (pintype "passive"))
      (node (ref "U2") (pin "E29") (pinfunction "VDD_D2_E29") (pintype "passive"))
      (node (ref "U2") (pin "E31") (pinfunction "VDD_D2_E31") (pintype "passive"))
      (node (ref "U2") (pin "E33") (pinfunction "VDD_D2_E33") (pintype "passive"))
      (node (ref "U2") (pin "E35") (pinfunction "VDD_D2_E35") (pintype "passive"))
      (node (ref "U2") (pin "E37") (pinfunction "VDD_D2_E37") (pintype "passive"))
      (node (ref "U2") (pin "E39") (pinfunction "VDD_D2_E39") (pintype "passive"))
      (node (ref "U2") (pin "E4") (pinfunction "VDD_D1_E4") (pintype "passive"))
      (node (ref "U2") (pin "E41") (pinfunction "VDD_D2_E41") (pintype "passive"))
      (node (ref "U2") (pin "E43") (pinfunction "VDD_D2_E43") (pintype "passive"))
      (node (ref "U2") (pin "E6") (pinfunction "VDD_D1_E6") (pintype "passive"))
      (node (ref "U2") (pin "E8") (pinfunction "VDD_D1_E8") (pintype "passive"))
      (node (ref "U2") (pin "F1") (pinfunction "VDD_D1_F1") (pintype "passive"))
      (node (ref "U2") (pin "F11") (pinfunction "VDD_D1_F11") (pintype "passive"))
      (node (ref "U2") (pin "F13") (pinfunction "VDD_D1_F13") (pintype "passive"))
      (node (ref "U2") (pin "F15") (pinfunction "VDD_D1_F15") (pintype "passive"))
      (node (ref "U2") (pin "F17") (pinfunction "VDD_D1_F17") (pintype "passive"))
      (node (ref "U2") (pin "F19") (pinfunction "VDD_D1_F19") (pintype "passive"))
      (node (ref "U2") (pin "F21") (pinfunction "VDD_D1_F21") (pintype "passive"))
      (node (ref "U2") (pin "F24") (pinfunction "VDD_D2_F24") (pintype "passive"))
      (node (ref "U2") (pin "F26") (pinfunction "VDD_D2_F26") (pintype "passive"))
      (node (ref "U2") (pin "F28") (pinfunction "VDD_D2_F28") (pintype "passive"))
      (node (ref "U2") (pin "F3") (pinfunction "VDD_D1_F3") (pintype "passive"))
      (node (ref "U2") (pin "F30") (pinfunction "VDD_D2_F30") (pintype "passive"))
      (node (ref "U2") (pin "F32") (pinfunction "VDD_D2_F32") (pintype "passive"))
      (node (ref "U2") (pin "F34") (pinfunction "VDD_D2_F34") (pintype "passive"))
      (node (ref "U2") (pin "F36") (pinfunction "VDD_D2_F36") (pintype "passive"))
      (node (ref "U2") (pin "F38") (pinfunction "VDD_D2_F38") (pintype "passive"))
      (node (ref "U2") (pin "F40") (pinfunction "VDD_D2_F40") (pintype "passive"))
      (node (ref "U2") (pin "F42") (pinfunction "VDD_D2_F42") (pintype "passive"))
      (node (ref "U2") (pin "F44") (pinfunction "VDD_D2_F44") (pintype "passive"))
      (node (ref "U2") (pin "F5") (pinfunction "VDD_D1_F5") (pintype "passive"))
      (node (ref "U2") (pin "F7") (pinfunction "VDD_D1_F7") (pintype "passive"))
      (node (ref "U2") (pin "F9") (pinfunction "VDD_D1_F9") (pintype "passive"))
      (node (ref "U2") (pin "G10") (pinfunction "VDD_D1_G10") (pintype "passive"))
      (node (ref "U2") (pin "G12") (pinfunction "VDD_D1_G12") (pintype "passive"))
      (node (ref "U2") (pin "G14") (pinfunction "VDD_D1_G14") (pintype "passive"))
      (node (ref "U2") (pin "G16") (pinfunction "VDD_D1_G16") (pintype "passive"))
      (node (ref "U2") (pin "G18") (pinfunction "VDD_D1_G18") (pintype "passive"))
      (node (ref "U2") (pin "G2") (pinfunction "VDD_D1_G2") (pintype "passive"))
      (node (ref "U2") (pin "G20") (pinfunction "VDD_D1_G20") (pintype "passive"))
      (node (ref "U2") (pin "G22") (pinfunction "VDD_D1_G22") (pintype "passive"))
      (node (ref "U2") (pin "G23") (pinfunction "VDD_D2_G23") (pintype "passive"))
      (node (ref "U2") (pin "G25") (pinfunction "VDD_D2_G25") (pintype "passive"))
      (node (ref "U2") (pin "G27") (pinfunction "VDD_D2_G27") (pintype "passive"))
      (node (ref "U2") (pin "G29") (pinfunction "VDD_D2_G29") (pintype "passive"))
      (node (ref "U2") (pin "G31") (pinfunction "VDD_D2_G31") (pintype "passive"))
      (node (ref "U2") (pin "G33") (pinfunction "VDD_D2_G33") (pintype "passive"))
      (node (ref "U2") (pin "G35") (pinfunction "VDD_D2_G35") (pintype "passive"))
      (node (ref "U2") (pin "G37") (pinfunction "VDD_D2_G37") (pintype "passive"))
      (node (ref "U2") (pin "G39") (pinfunction "VDD_D2_G39") (pintype "passive"))
      (node (ref "U2") (pin "G4") (pinfunction "VDD_D1_G4") (pintype "passive"))
      (node (ref "U2") (pin "G41") (pinfunction "VDD_D2_G41") (pintype "passive"))
      (node (ref "U2") (pin "G43") (pinfunction "VDD_D2_G43") (pintype "passive"))
      (node (ref "U2") (pin "G6") (pinfunction "VDD_D1_G6") (pintype "passive"))
      (node (ref "U2") (pin "G8") (pinfunction "VDD_D1_G8") (pintype "passive"))
      (node (ref "U2") (pin "H1") (pinfunction "VDD_D1_H1") (pintype "passive"))
      (node (ref "U2") (pin "H11") (pinfunction "VDD_D1_H11") (pintype "passive"))
      (node (ref "U2") (pin "H13") (pinfunction "VDD_D1_H13") (pintype "passive"))
      (node (ref "U2") (pin "H15") (pinfunction "VDD_D1_H15") (pintype "passive"))
      (node (ref "U2") (pin "H17") (pinfunction "VDD_D1_H17") (pintype "passive"))
      (node (ref "U2") (pin "H19") (pinfunction "VDD_D1_H19") (pintype "passive"))
      (node (ref "U2") (pin "H21") (pinfunction "VDD_D1_H21") (pintype "passive"))
      (node (ref "U2") (pin "H24") (pinfunction "VDD_D2_H24") (pintype "passive"))
      (node (ref "U2") (pin "H26") (pinfunction "VDD_D2_H26") (pintype "passive"))
      (node (ref "U2") (pin "H28") (pinfunction "VDD_D2_H28") (pintype "passive"))
      (node (ref "U2") (pin "H3") (pinfunction "VDD_D1_H3") (pintype "passive"))
      (node (ref "U2") (pin "H30") (pinfunction "VDD_D2_H30") (pintype "passive"))
      (node (ref "U2") (pin "H32") (pinfunction "VDD_D2_H32") (pintype "passive"))
      (node (ref "U2") (pin "H34") (pinfunction "VDD_D2_H34") (pintype "passive"))
      (node (ref "U2") (pin "H36") (pinfunction "VDD_D2_H36") (pintype "passive"))
      (node (ref "U2") (pin "H38") (pinfunction "VDD_D2_H38") (pintype "passive"))
      (node (ref "U2") (pin "H40") (pinfunction "VDD_D2_H40") (pintype "passive"))
      (node (ref "U2") (pin "H42") (pinfunction "VDD_D2_H42") (pintype "passive"))
      (node (ref "U2") (pin "H44") (pinfunction "VDD_D2_H44") (pintype "passive"))
      (node (ref "U2") (pin "H5") (pinfunction "VDD_D1_H5") (pintype "passive"))
      (node (ref "U2") (pin "H7") (pinfunction "VDD_D1_H7") (pintype "passive"))
      (node (ref "U2") (pin "H9") (pinfunction "VDD_D1_H9") (pintype "passive"))
      (node (ref "U2") (pin "J10") (pinfunction "VDD_D1_J10") (pintype "passive"))
      (node (ref "U2") (pin "J12") (pinfunction "VDD_D1_J12") (pintype "passive"))
      (node (ref "U2") (pin "J14") (pinfunction "VDD_D1_J14") (pintype "passive"))
      (node (ref "U2") (pin "J16") (pinfunction "VDD_D1_J16") (pintype "passive"))
      (node (ref "U2") (pin "J18") (pinfunction "VDD_D1_J18") (pintype "passive"))
      (node (ref "U2") (pin "J2") (pinfunction "VDD_D1_J2") (pintype "passive"))
      (node (ref "U2") (pin "J20") (pinfunction "VDD_D1_J20") (pintype "passive"))
      (node (ref "U2") (pin "J22") (pinfunction "VDD_D1_J22") (pintype "passive"))
      (node (ref "U2") (pin "J23") (pinfunction "VDD_D2_J23") (pintype "passive"))
      (node (ref "U2") (pin "J25") (pinfunction "VDD_D2_J25") (pintype "passive"))
      (node (ref "U2") (pin "J27") (pinfunction "VDD_D2_J27") (pintype "passive"))
      (node (ref "U2") (pin "J29") (pinfunction "VDD_D2_J29") (pintype "passive"))
      (node (ref "U2") (pin "J31") (pinfunction "VDD_D2_J31") (pintype "passive"))
      (node (ref "U2") (pin "J33") (pinfunction "VDD_D2_J33") (pintype "passive"))
      (node (ref "U2") (pin "J35") (pinfunction "VDD_D2_J35") (pintype "passive"))
      (node (ref "U2") (pin "J37") (pinfunction "VDD_D2_J37") (pintype "passive"))
      (node (ref "U2") (pin "J39") (pinfunction "VDD_D2_J39") (pintype "passive"))
      (node (ref "U2") (pin "J4") (pinfunction "VDD_D1_J4") (pintype "passive"))
      (node (ref "U2") (pin "J41") (pinfunction "VDD_D2_J41") (pintype "passive"))
      (node (ref "U2") (pin "J43") (pinfunction "VDD_D2_J43") (pintype "passive"))
      (node (ref "U2") (pin "J6") (pinfunction "VDD_D1_J6") (pintype "passive"))
      (node (ref "U2") (pin "J8") (pinfunction "VDD_D1_J8") (pintype "passive"))
      (node (ref "U2") (pin "K1") (pinfunction "VDD_D1_K1") (pintype "passive"))
      (node (ref "U2") (pin "K11") (pinfunction "VDD_D1_K11") (pintype "passive"))
      (node (ref "U2") (pin "K13") (pinfunction "VDD_D1_K13") (pintype "passive"))
      (node (ref "U2") (pin "K15") (pinfunction "VDD_D1_K15") (pintype "passive"))
      (node (ref "U2") (pin "K17") (pinfunction "VDD_D1_K17") (pintype "passive"))
      (node (ref "U2") (pin "K19") (pinfunction "VDD_D1_K19") (pintype "passive"))
      (node (ref "U2") (pin "K21") (pinfunction "VDD_D1_K21") (pintype "passive"))
      (node (ref "U2") (pin "K24") (pinfunction "VDD_D2_K24") (pintype "passive"))
      (node (ref "U2") (pin "K26") (pinfunction "VDD_D2_K26") (pintype "passive"))
      (node (ref "U2") (pin "K28") (pinfunction "VDD_D2_K28") (pintype "passive"))
      (node (ref "U2") (pin "K3") (pinfunction "VDD_D1_K3") (pintype "passive"))
      (node (ref "U2") (pin "K30") (pinfunction "VDD_D2_K30") (pintype "passive"))
      (node (ref "U2") (pin "K32") (pinfunction "VDD_D2_K32") (pintype "passive"))
      (node (ref "U2") (pin "K34") (pinfunction "VDD_D2_K34") (pintype "passive"))
      (node (ref "U2") (pin "K36") (pinfunction "VDD_D2_K36") (pintype "passive"))
      (node (ref "U2") (pin "K38") (pinfunction "VDD_D2_K38") (pintype "passive"))
      (node (ref "U2") (pin "K40") (pinfunction "VDD_D2_K40") (pintype "passive"))
      (node (ref "U2") (pin "K42") (pinfunction "VDD_D2_K42") (pintype "passive"))
      (node (ref "U2") (pin "K44") (pinfunction "VDD_D2_K44") (pintype "passive"))
      (node (ref "U2") (pin "K5") (pinfunction "VDD_D1_K5") (pintype "passive"))
      (node (ref "U2") (pin "K7") (pinfunction "VDD_D1_K7") (pintype "passive"))
      (node (ref "U2") (pin "K9") (pinfunction "VDD_D1_K9") (pintype "passive"))
      (node (ref "U2") (pin "L10") (pinfunction "VDD_D1_L10") (pintype "passive"))
      (node (ref "U2") (pin "L12") (pinfunction "VDD_D1_L12") (pintype "passive"))
      (node (ref "U2") (pin "L14") (pinfunction "VDD_D1_L14") (pintype "passive"))
      (node (ref "U2") (pin "L16") (pinfunction "VDD_D1_L16") (pintype "passive"))
      (node (ref "U2") (pin "L18") (pinfunction "VDD_D1_L18") (pintype "passive"))
      (node (ref "U2") (pin "L2") (pinfunction "VDD_D1_L2") (pintype "passive"))
      (node (ref "U2") (pin "L20") (pinfunction "VDD_D1_L20") (pintype "passive"))
      (node (ref "U2") (pin "L22") (pinfunction "VDD_D1_L22") (pintype "passive"))
      (node (ref "U2") (pin "L23") (pinfunction "VDD_D2_L23") (pintype "passive"))
      (node (ref "U2") (pin "L25") (pinfunction "VDD_D2_L25") (pintype "passive"))
      (node (ref "U2") (pin "L27") (pinfunction "VDD_D2_L27") (pintype "passive"))
      (node (ref "U2") (pin "L29") (pinfunction "VDD_D2_L29") (pintype "passive"))
      (node (ref "U2") (pin "L31") (pinfunction "VDD_D2_L31") (pintype "passive"))
      (node (ref "U2") (pin "L33") (pinfunction "VDD_D2_L33") (pintype "passive"))
      (node (ref "U2") (pin "L35") (pinfunction "VDD_D2_L35") (pintype "passive"))
      (node (ref "U2") (pin "L37") (pinfunction "VDD_D2_L37") (pintype "passive"))
      (node (ref "U2") (pin "L39") (pinfunction "VDD_D2_L39") (pintype "passive"))
      (node (ref "U2") (pin "L4") (pinfunction "VDD_D1_L4") (pintype "passive"))
      (node (ref "U2") (pin "L41") (pinfunction "VDD_D2_L41") (pintype "passive"))
      (node (ref "U2") (pin "L43") (pinfunction "VDD_D2_L43") (pintype "passive"))
      (node (ref "U2") (pin "L6") (pinfunction "VDD_D1_L6") (pintype "passive"))
      (node (ref "U2") (pin "L8") (pinfunction "VDD_D1_L8") (pintype "passive"))
      (node (ref "U2") (pin "M1") (pinfunction "VDD_D1_M1") (pintype "passive"))
      (node (ref "U2") (pin "M11") (pinfunction "VDD_D1_M11") (pintype "passive"))
      (node (ref "U2") (pin "M13") (pinfunction "VDD_D1_M13") (pintype "passive"))
      (node (ref "U2") (pin "M15") (pinfunction "VDD_D1_M15") (pintype "passive"))
      (node (ref "U2") (pin "M17") (pinfunction "VDD_D1_M17") (pintype "passive"))
      (node (ref "U2") (pin "M19") (pinfunction "VDD_D1_M19") (pintype "passive"))
      (node (ref "U2") (pin "M21") (pinfunction "VDD_D1_M21") (pintype "passive"))
      (node (ref "U2") (pin "M24") (pinfunction "VDD_D2_M24") (pintype "passive"))
      (node (ref "U2") (pin "M26") (pinfunction "VDD_D2_M26") (pintype "passive"))
      (node (ref "U2") (pin "M28") (pinfunction "VDD_D2_M28") (pintype "passive"))
      (node (ref "U2") (pin "M3") (pinfunction "VDD_D1_M3") (pintype "passive"))
      (node (ref "U2") (pin "M30") (pinfunction "VDD_D2_M30") (pintype "passive"))
      (node (ref "U2") (pin "M32") (pinfunction "VDD_D2_M32") (pintype "passive"))
      (node (ref "U2") (pin "M34") (pinfunction "VDD_D2_M34") (pintype "passive"))
      (node (ref "U2") (pin "M36") (pinfunction "VDD_D2_M36") (pintype "passive"))
      (node (ref "U2") (pin "M38") (pinfunction "VDD_D2_M38") (pintype "passive"))
      (node (ref "U2") (pin "M40") (pinfunction "VDD_D2_M40") (pintype "passive"))
      (node (ref "U2") (pin "M42") (pinfunction "VDD_D2_M42") (pintype "passive"))
      (node (ref "U2") (pin "M44") (pinfunction "VDD_D2_M44") (pintype "passive"))
      (node (ref "U2") (pin "M5") (pinfunction "VDD_D1_M5") (pintype "passive"))
      (node (ref "U2") (pin "M7") (pinfunction "VDD_D1_M7") (pintype "passive"))
      (node (ref "U2") (pin "M9") (pinfunction "VDD_D1_M9") (pintype "passive"))
      (node (ref "U2") (pin "N10") (pinfunction "VDD_D1_N10") (pintype "passive"))
      (node (ref "U2") (pin "N12") (pinfunction "VDD_D1_N12") (pintype "passive"))
      (node (ref "U2") (pin "N14") (pinfunction "VDD_D1_N14") (pintype "passive"))
      (node (ref "U2") (pin "N16") (pinfunction "VDD_D1_N16") (pintype "passive"))
      (node (ref "U2") (pin "N18") (pinfunction "VDD_D1_N18") (pintype "passive"))
      (node (ref "U2") (pin "N2") (pinfunction "VDD_D1_N2") (pintype "passive"))
      (node (ref "U2") (pin "N20") (pinfunction "VDD_D1_N20") (pintype "passive"))
      (node (ref "U2") (pin "N22") (pinfunction "VDD_D1_N22") (pintype "passive"))
      (node (ref "U2") (pin "N23") (pinfunction "VDD_D2_N23") (pintype "passive"))
      (node (ref "U2") (pin "N25") (pinfunction "VDD_D2_N25") (pintype "passive"))
      (node (ref "U2") (pin "N27") (pinfunction "VDD_D2_N27") (pintype "passive"))
      (node (ref "U2") (pin "N29") (pinfunction "VDD_D2_N29") (pintype "passive"))
      (node (ref "U2") (pin "N31") (pinfunction "VDD_D2_N31") (pintype "passive"))
      (node (ref "U2") (pin "N33") (pinfunction "VDD_D2_N33") (pintype "passive"))
      (node (ref "U2") (pin "N35") (pinfunction "VDD_D2_N35") (pintype "passive"))
      (node (ref "U2") (pin "N37") (pinfunction "VDD_D2_N37") (pintype "passive"))
      (node (ref "U2") (pin "N39") (pinfunction "VDD_D2_N39") (pintype "passive"))
      (node (ref "U2") (pin "N4") (pinfunction "VDD_D1_N4") (pintype "passive"))
      (node (ref "U2") (pin "N41") (pinfunction "VDD_D2_N41") (pintype "passive"))
      (node (ref "U2") (pin "N43") (pinfunction "VDD_D2_N43") (pintype "passive"))
      (node (ref "U2") (pin "N6") (pinfunction "VDD_D1_N6") (pintype "passive"))
      (node (ref "U2") (pin "N8") (pinfunction "VDD_D1_N8") (pintype "passive"))
      (node (ref "U2") (pin "P1") (pinfunction "VDD_D1_P1") (pintype "passive"))
      (node (ref "U2") (pin "P11") (pinfunction "VDD_D1_P11") (pintype "passive"))
      (node (ref "U2") (pin "P13") (pinfunction "VDD_D1_P13") (pintype "passive"))
      (node (ref "U2") (pin "P15") (pinfunction "VDD_D1_P15") (pintype "passive"))
      (node (ref "U2") (pin "P17") (pinfunction "VDD_D1_P17") (pintype "passive"))
      (node (ref "U2") (pin "P19") (pinfunction "VDD_D1_P19") (pintype "passive"))
      (node (ref "U2") (pin "P21") (pinfunction "VDD_D1_P21") (pintype "passive"))
      (node (ref "U2") (pin "P24") (pinfunction "VDD_D2_P24") (pintype "passive"))
      (node (ref "U2") (pin "P26") (pinfunction "VDD_D2_P26") (pintype "passive"))
      (node (ref "U2") (pin "P28") (pinfunction "VDD_D2_P28") (pintype "passive"))
      (node (ref "U2") (pin "P3") (pinfunction "VDD_D1_P3") (pintype "passive"))
      (node (ref "U2") (pin "P30") (pinfunction "VDD_D2_P30") (pintype "passive"))
      (node (ref "U2") (pin "P32") (pinfunction "VDD_D2_P32") (pintype "passive"))
      (node (ref "U2") (pin "P34") (pinfunction "VDD_D2_P34") (pintype "passive"))
      (node (ref "U2") (pin "P36") (pinfunction "VDD_D2_P36") (pintype "passive"))
      (node (ref "U2") (pin "P38") (pinfunction "VDD_D2_P38") (pintype "passive"))
      (node (ref "U2") (pin "P40") (pinfunction "VDD_D2_P40") (pintype "passive"))
      (node (ref "U2") (pin "P42") (pinfunction "VDD_D2_P42") (pintype "passive"))
      (node (ref "U2") (pin "P44") (pinfunction "VDD_D2_P44") (pintype "passive"))
      (node (ref "U2") (pin "P5") (pinfunction "VDD_D1_P5") (pintype "passive"))
      (node (ref "U2") (pin "P7") (pinfunction "VDD_D1_P7") (pintype "passive"))
      (node (ref "U2") (pin "P9") (pinfunction "VDD_D1_P9") (pintype "passive"))
      (node (ref "U2") (pin "R10") (pinfunction "VDD_D1_R10") (pintype "passive"))
      (node (ref "U2") (pin "R12") (pinfunction "VDD_D1_R12") (pintype "passive"))
      (node (ref "U2") (pin "R14") (pinfunction "VDD_D1_R14") (pintype "passive"))
      (node (ref "U2") (pin "R16") (pinfunction "VDD_D1_R16") (pintype "passive"))
      (node (ref "U2") (pin "R18") (pinfunction "VDD_D1_R18") (pintype "passive"))
      (node (ref "U2") (pin "R2") (pinfunction "VDD_D1_R2") (pintype "passive"))
      (node (ref "U2") (pin "R20") (pinfunction "VDD_D1_R20") (pintype "passive"))
      (node (ref "U2") (pin "R22") (pinfunction "VDD_D1_R22") (pintype "passive"))
      (node (ref "U2") (pin "R23") (pinfunction "VDD_D2_R23") (pintype "passive"))
      (node (ref "U2") (pin "R25") (pinfunction "VDD_D2_R25") (pintype "passive"))
      (node (ref "U2") (pin "R27") (pinfunction "VDD_D2_R27") (pintype "passive"))
      (node (ref "U2") (pin "R29") (pinfunction "VDD_D2_R29") (pintype "passive"))
      (node (ref "U2") (pin "R31") (pinfunction "VDD_D2_R31") (pintype "passive"))
      (node (ref "U2") (pin "R33") (pinfunction "VDD_D2_R33") (pintype "passive"))
      (node (ref "U2") (pin "R35") (pinfunction "VDD_D2_R35") (pintype "passive"))
      (node (ref "U2") (pin "R37") (pinfunction "VDD_D2_R37") (pintype "passive"))
      (node (ref "U2") (pin "R39") (pinfunction "VDD_D2_R39") (pintype "passive"))
      (node (ref "U2") (pin "R4") (pinfunction "VDD_D1_R4") (pintype "passive"))
      (node (ref "U2") (pin "R41") (pinfunction "VDD_D2_R41") (pintype "passive"))
      (node (ref "U2") (pin "R43") (pinfunction "VDD_D2_R43") (pintype "passive"))
      (node (ref "U2") (pin "R6") (pinfunction "VDD_D1_R6") (pintype "passive"))
      (node (ref "U2") (pin "R8") (pinfunction "VDD_D1_R8") (pintype "passive"))
      (node (ref "U2") (pin "T1") (pinfunction "VDD_D1_T1") (pintype "passive"))
      (node (ref "U2") (pin "T11") (pinfunction "VDD_D1_T11") (pintype "passive"))
      (node (ref "U2") (pin "T13") (pinfunction "VDD_D1_T13") (pintype "passive"))
      (node (ref "U2") (pin "T15") (pinfunction "VDD_D1_T15") (pintype "passive"))
      (node (ref "U2") (pin "T17") (pinfunction "VDD_D1_T17") (pintype "passive"))
      (node (ref "U2") (pin "T19") (pinfunction "VDD_D1_T19") (pintype "passive"))
      (node (ref "U2") (pin "T21") (pinfunction "VDD_D1_T21") (pintype "passive"))
      (node (ref "U2") (pin "T24") (pinfunction "VDD_D2_T24") (pintype "passive"))
      (node (ref "U2") (pin "T26") (pinfunction "VDD_D2_T26") (pintype "passive"))
      (node (ref "U2") (pin "T28") (pinfunction "VDD_D2_T28") (pintype "passive"))
      (node (ref "U2") (pin "T3") (pinfunction "VDD_D1_T3") (pintype "passive"))
      (node (ref "U2") (pin "T30") (pinfunction "VDD_D2_T30") (pintype "passive"))
      (node (ref "U2") (pin "T32") (pinfunction "VDD_D2_T32") (pintype "passive"))
      (node (ref "U2") (pin "T34") (pinfunction "VDD_D2_T34") (pintype "passive"))
      (node (ref "U2") (pin "T36") (pinfunction "VDD_D2_T36") (pintype "passive"))
      (node (ref "U2") (pin "T38") (pinfunction "VDD_D2_T38") (pintype "passive"))
      (node (ref "U2") (pin "T40") (pinfunction "VDD_D2_T40") (pintype "passive"))
      (node (ref "U2") (pin "T42") (pinfunction "VDD_D2_T42") (pintype "passive"))
      (node (ref "U2") (pin "T44") (pinfunction "VDD_D2_T44") (pintype "passive"))
      (node (ref "U2") (pin "T5") (pinfunction "VDD_D1_T5") (pintype "passive"))
      (node (ref "U2") (pin "T7") (pinfunction "VDD_D1_T7") (pintype "passive"))
      (node (ref "U2") (pin "T9") (pinfunction "VDD_D1_T9") (pintype "passive"))
      (node (ref "U2") (pin "U10") (pinfunction "VDD_D1_U10") (pintype "passive"))
      (node (ref "U2") (pin "U12") (pinfunction "VDD_D1_U12") (pintype "passive"))
      (node (ref "U2") (pin "U14") (pinfunction "VDD_D1_U14") (pintype "passive"))
      (node (ref "U2") (pin "U16") (pinfunction "VDD_D1_U16") (pintype "passive"))
      (node (ref "U2") (pin "U18") (pinfunction "VDD_D1_U18") (pintype "passive"))
      (node (ref "U2") (pin "U2") (pinfunction "VDD_D1_U2") (pintype "passive"))
      (node (ref "U2") (pin "U20") (pinfunction "VDD_D1_U20") (pintype "passive"))
      (node (ref "U2") (pin "U22") (pinfunction "VDD_D1_U22") (pintype "passive"))
      (node (ref "U2") (pin "U23") (pinfunction "VDD_D2_U23") (pintype "passive"))
      (node (ref "U2") (pin "U25") (pinfunction "VDD_D2_U25") (pintype "passive"))
      (node (ref "U2") (pin "U27") (pinfunction "VDD_D2_U27") (pintype "passive"))
      (node (ref "U2") (pin "U29") (pinfunction "VDD_D2_U29") (pintype "passive"))
      (node (ref "U2") (pin "U31") (pinfunction "VDD_D2_U31") (pintype "passive"))
      (node (ref "U2") (pin "U33") (pinfunction "VDD_D2_U33") (pintype "passive"))
      (node (ref "U2") (pin "U35") (pinfunction "VDD_D2_U35") (pintype "passive"))
      (node (ref "U2") (pin "U37") (pinfunction "VDD_D2_U37") (pintype "passive"))
      (node (ref "U2") (pin "U39") (pinfunction "VDD_D2_U39") (pintype "passive"))
      (node (ref "U2") (pin "U4") (pinfunction "VDD_D1_U4") (pintype "passive"))
      (node (ref "U2") (pin "U41") (pinfunction "VDD_D2_U41") (pintype "passive"))
      (node (ref "U2") (pin "U43") (pinfunction "VDD_D2_U43") (pintype "passive"))
      (node (ref "U2") (pin "U6") (pinfunction "VDD_D1_U6") (pintype "passive"))
      (node (ref "U2") (pin "U8") (pinfunction "VDD_D1_U8") (pintype "passive"))
      (node (ref "U2") (pin "V1") (pinfunction "VDD_D1_V1") (pintype "passive"))
      (node (ref "U2") (pin "V11") (pinfunction "VDD_D1_V11") (pintype "passive"))
      (node (ref "U2") (pin "V13") (pinfunction "VDD_D1_V13") (pintype "passive"))
      (node (ref "U2") (pin "V15") (pinfunction "VDD_D1_V15") (pintype "passive"))
      (node (ref "U2") (pin "V17") (pinfunction "VDD_D1_V17") (pintype "passive"))
      (node (ref "U2") (pin "V19") (pinfunction "VDD_D1_V19") (pintype "passive"))
      (node (ref "U2") (pin "V21") (pinfunction "VDD_D1_V21") (pintype "passive"))
      (node (ref "U2") (pin "V24") (pinfunction "VDD_D2_V24") (pintype "passive"))
      (node (ref "U2") (pin "V26") (pinfunction "VDD_D2_V26") (pintype "passive"))
      (node (ref "U2") (pin "V28") (pinfunction "VDD_D2_V28") (pintype "passive"))
      (node (ref "U2") (pin "V3") (pinfunction "VDD_D1_V3") (pintype "passive"))
      (node (ref "U2") (pin "V30") (pinfunction "VDD_D2_V30") (pintype "passive"))
      (node (ref "U2") (pin "V32") (pinfunction "VDD_D2_V32") (pintype "passive"))
      (node (ref "U2") (pin "V34") (pinfunction "VDD_D2_V34") (pintype "passive"))
      (node (ref "U2") (pin "V36") (pinfunction "VDD_D2_V36") (pintype "passive"))
      (node (ref "U2") (pin "V38") (pinfunction "VDD_D2_V38") (pintype "passive"))
      (node (ref "U2") (pin "V40") (pinfunction "VDD_D2_V40") (pintype "passive"))
      (node (ref "U2") (pin "V42") (pinfunction "VDD_D2_V42") (pintype "passive"))
      (node (ref "U2") (pin "V44") (pinfunction "VDD_D2_V44") (pintype "passive"))
      (node (ref "U2") (pin "V5") (pinfunction "VDD_D1_V5") (pintype "passive"))
      (node (ref "U2") (pin "V7") (pinfunction "VDD_D1_V7") (pintype "passive"))
      (node (ref "U2") (pin "V9") (pinfunction "VDD_D1_V9") (pintype "passive"))
      (node (ref "U2") (pin "W10") (pinfunction "VDD_D1_W10") (pintype "passive"))
      (node (ref "U2") (pin "W12") (pinfunction "VDD_D1_W12") (pintype "passive"))
      (node (ref "U2") (pin "W14") (pinfunction "VDD_D1_W14") (pintype "passive"))
      (node (ref "U2") (pin "W16") (pinfunction "VDD_D1_W16") (pintype "passive"))
      (node (ref "U2") (pin "W18") (pinfunction "VDD_D1_W18") (pintype "passive"))
      (node (ref "U2") (pin "W2") (pinfunction "VDD_D1_W2") (pintype "passive"))
      (node (ref "U2") (pin "W20") (pinfunction "VDD_D1_W20") (pintype "passive"))
      (node (ref "U2") (pin "W22") (pinfunction "VDD_D1_W22") (pintype "passive"))
      (node (ref "U2") (pin "W23") (pinfunction "VDD_D2_W23") (pintype "passive"))
      (node (ref "U2") (pin "W25") (pinfunction "VDD_D2_W25") (pintype "passive"))
      (node (ref "U2") (pin "W27") (pinfunction "VDD_D2_W27") (pintype "passive"))
      (node (ref "U2") (pin "W29") (pinfunction "VDD_D2_W29") (pintype "passive"))
      (node (ref "U2") (pin "W31") (pinfunction "VDD_D2_W31") (pintype "passive"))
      (node (ref "U2") (pin "W33") (pinfunction "VDD_D2_W33") (pintype "passive"))
      (node (ref "U2") (pin "W35") (pinfunction "VDD_D2_W35") (pintype "passive"))
      (node (ref "U2") (pin "W37") (pinfunction "VDD_D2_W37") (pintype "passive"))
      (node (ref "U2") (pin "W39") (pinfunction "VDD_D2_W39") (pintype "passive"))
      (node (ref "U2") (pin "W4") (pinfunction "VDD_D1_W4") (pintype "passive"))
      (node (ref "U2") (pin "W41") (pinfunction "VDD_D2_W41") (pintype "passive"))
      (node (ref "U2") (pin "W43") (pinfunction "VDD_D2_W43") (pintype "passive"))
      (node (ref "U2") (pin "W6") (pinfunction "VDD_D1_W6") (pintype "passive"))
      (node (ref "U2") (pin "W8") (pinfunction "VDD_D1_W8") (pintype "passive"))
      (node (ref "U2") (pin "Y1") (pinfunction "VDD_D1_Y1") (pintype "passive"))
      (node (ref "U2") (pin "Y11") (pinfunction "VDD_D1_Y11") (pintype "passive"))
      (node (ref "U2") (pin "Y13") (pinfunction "VDD_D1_Y13") (pintype "passive"))
      (node (ref "U2") (pin "Y15") (pinfunction "VDD_D1_Y15") (pintype "passive"))
      (node (ref "U2") (pin "Y17") (pinfunction "VDD_D1_Y17") (pintype "passive"))
      (node (ref "U2") (pin "Y19") (pinfunction "VDD_D1_Y19") (pintype "passive"))
      (node (ref "U2") (pin "Y21") (pinfunction "VDD_D1_Y21") (pintype "passive"))
      (node (ref "U2") (pin "Y24") (pinfunction "VDD_D2_Y24") (pintype "passive"))
      (node (ref "U2") (pin "Y26") (pinfunction "VDD_D2_Y26") (pintype "passive"))
      (node (ref "U2") (pin "Y28") (pinfunction "VDD_D2_Y28") (pintype "passive"))
      (node (ref "U2") (pin "Y3") (pinfunction "VDD_D1_Y3") (pintype "passive"))
      (node (ref "U2") (pin "Y30") (pinfunction "VDD_D2_Y30") (pintype "passive"))
      (node (ref "U2") (pin "Y32") (pinfunction "VDD_D2_Y32") (pintype "passive"))
      (node (ref "U2") (pin "Y34") (pinfunction "VDD_D2_Y34") (pintype "passive"))
      (node (ref "U2") (pin "Y36") (pinfunction "VDD_D2_Y36") (pintype "passive"))
      (node (ref "U2") (pin "Y38") (pinfunction "VDD_D2_Y38") (pintype "passive"))
      (node (ref "U2") (pin "Y40") (pinfunction "VDD_D2_Y40") (pintype "passive"))
      (node (ref "U2") (pin "Y42") (pinfunction "VDD_D2_Y42") (pintype "passive"))
      (node (ref "U2") (pin "Y44") (pinfunction "VDD_D2_Y44") (pintype "passive"))
      (node (ref "U2") (pin "Y5") (pinfunction "VDD_D1_Y5") (pintype "passive"))
      (node (ref "U2") (pin "Y7") (pinfunction "VDD_D1_Y7") (pintype "passive"))
      (node (ref "U2") (pin "Y9") (pinfunction "VDD_D1_Y9") (pintype "passive"))
    )
    (net (code "2") (name "GND") (class "Default")
      (node (ref "C267") (pin "1") (pinfunction "1_1") (pintype "passive"))
      (node (ref "C268") (pin "1") (pinfunction "1_1") (pintype "passive"))
      (node (ref "C269") (pin "1") (pinfunction "1_1") (pintype "passive"))
      (node (ref "C270") (pin "1") (pinfunction "1_1") (pintype "passive"))
      (node (ref "C271") (pin "1") (pinfunction "1_1") (pintype "passive"))
      (node (ref "C272") (pin "1") (pinfunction "1_1") (pintype "passive"))
      (node (ref "C273") (pin "1") (pinfunction "1_1") (pintype "passive"))
      (node (ref "C274") (pin "1") (pinfunction "1_1") (pintype "passive"))
      (node (ref "C275") (pin "1") (pinfunction "1_1") (pintype "passive"))
      (node (ref "C276") (pin "1") (pinfunction "1_1") (pintype "passive"))
      (node (ref "C277") (pin "1") (pinfunction "1_1") (pintype "passive"))
      (node (ref "C278") (pin "1") (pinfunction "1_1") (pintype "passive"))
      (node (ref "C279") (pin "1") (pinfunction "1_1") (pintype "passive"))
      (node (ref "C280") (pin "1") (pinfunction "1_1") (pintype "passive"))
      (node (ref "C281") (pin "1") (pinfunction "1_1") (pintype "passive"))
      (node (ref "C282") (pin "1") (pinfunction "1_1") (pintype "passive"))
      (node (ref "C283") (pin "1") (pinfunction "1_1") (pintype "passive"))
      (node (ref "C284") (pin "1") (pinfunction "1_1") (pintype "passive"))
      (node (ref "C285") (pin "1") (pinfunction "1_1") (pintype "passive"))
      (node (ref "C286") (pin "1") (pinfunction "1_1") (pintype "passive"))
      (node (ref "C287") (pin "1") (pinfunction "1_1") (pintype "passive"))
      (node (ref "C288") (pin "1") (pinfunction "1_1") (pintype "passive"))
      (node (ref "C289") (pin "1") (pinfunction "1_1") (pintype "passive"))
      (node (ref "C290") (pin "1") (pinfunction "1_1") (pintype "passive"))
      (node (ref "C291") (pin "1") (pinfunction "1_1") (pintype "passive"))
      (node (ref "C292") (pin "1") (pinfunction "1_1") (pintype "passive"))
      (node (ref "C293") (pin "1") (pinfunction "1_1") (pintype "passive"))
      (node (ref "C294") (pin "1") (pinfunction "1_1") (pintype "passive"))
      (node (ref "C295") (pin "1") (pinfunction "1_1") (pintype "passive"))
      (node (ref "C296") (pin "1") (pinfunction "1_1") (pintype "passive"))
      (node (ref "C297") (pin "1") (pinfunction "1_1") (pintype "passive"))
      (node (ref "C298") (pin "1") (pinfunction "1_1") (pintype "passive"))
      (node (ref "C299") (pin "1") (pinfunction "1_1") (pintype "passive"))
      (node (ref "C300") (pin "1") (pinfunction "1_1") (pintype "passive"))
      (node (ref "C301") (pin "1") (pinfunction "1_1") (pintype "passive"))
      (node (ref "C302") (pin "1") (pinfunction "1_1") (pintype "passive"))
      (node (ref "C303") (pin "1") (pinfunction "1_1") (pintype "passive"))
      (node (ref "C304") (pin "1") (pinfunction "1_1") (pintype "passive"))
      (node (ref "C305") (pin "1") (pinfunction "1_1") (pintype "passive"))
      (node (ref "C306") (pin "1") (pinfunction "1_1") (pintype "passive"))
      (node (ref "C307") (pin "1") (pinfunction "1_1") (pintype "passive"))
      (node (ref "C308") (pin "1") (pinfunction "1_1") (pintype "passive"))
      (node (ref "C309") (pin "1") (pinfunction "1_1") (pintype "passive"))
      (node (ref "C310") (pin "1") (pinfunction "1_1") (pintype "passive"))
      (node (ref "C311") (pin "1") (pinfunction "1_1") (pintype "passive"))
      (node (ref "C312") (pin "1") (pinfunction "1_1") (pintype "passive"))
      (node (ref "C313") (pin "1") (pinfunction "1_1") (pintype "passive"))
      (node (ref "C314") (pin "1") (pinfunction "1_1") (pintype "passive"))
      (node (ref "C315") (pin "1") (pinfunction "1_1") (pintype "passive"))
      (node (ref "C316") (pin "1") (pinfunction "1_1") (pintype "passive"))
      (node (ref "C317") (pin "1") (pinfunction "1_1") (pintype "passive"))
      (node (ref "C318") (pin "1") (pinfunction "1_1") (pintype "passive"))
      (node (ref "C319") (pin "1") (pinfunction "1_1") (pintype "passive"))
      (node (ref "C320") (pin "1") (pinfunction "1_1") (pintype "passive"))
      (node (ref "C321") (pin "1") (pinfunction "1_1") (pintype "passive"))
      (node (ref "C322") (pin "1") (pinfunction "1_1") (pintype "passive"))
      (node (ref "C323") (pin "1") (pinfunction "1_1") (pintype "passive"))
      (node (ref "C324") (pin "1") (pinfunction "1_1") (pintype "passive"))
      (node (ref "C325") (pin "1") (pinfunction "1_1") (pintype "passive"))
      (node (ref "C326") (pin "1") (pinfunction "1_1") (pintype "passive"))
      (node (ref "C327") (pin "1") (pinfunction "1_1") (pintype "passive"))
      (node (ref "C328") (pin "1") (pinfunction "1_1") (pintype "passive"))
      (node (ref "C329") (pin "1") (pinfunction "1_1") (pintype "passive"))
      (node (ref "C330") (pin "1") (pinfunction "1_1") (pintype "passive"))
      (node (ref "C331") (pin "1") (pinfunction "1_1") (pintype "passive"))
      (node (ref "C332") (pin "1") (pinfunction "1_1") (pintype "passive"))
      (node (ref "C333") (pin "1") (pinfunction "1_1") (pintype "passive"))
      (node (ref "C334") (pin "1") (pinfunction "1_1") (pintype "passive"))
      (node (ref "C335") (pin "1") (pinfunction "1_1") (pintype "passive"))
      (node (ref "C336") (pin "1") (pinfunction "1_1") (pintype "passive"))
      (node (ref "C337") (pin "1") (pinfunction "1_1") (pintype "passive"))
      (node (ref "C338") (pin "1") (pinfunction "1_1") (pintype "passive"))
      (node (ref "C339") (pin "1") (pinfunction "1_1") (pintype "passive"))
      (node (ref "C340") (pin "1") (pinfunction "1_1") (pintype "passive"))
      (node (ref "C341") (pin "1") (pinfunction "1_1") (pintype "passive"))
      (node (ref "C342") (pin "1") (pinfunction "1_1") (pintype "passive"))
      (node (ref "C343") (pin "1") (pinfunction "1_1") (pintype "passive"))
      (node (ref "C344") (pin "1") (pinfunction "1_1") (pintype "passive"))
      (node (ref "C345") (pin "1") (pinfunction "1_1") (pintype "passive"))
      (node (ref "C346") (pin "1") (pinfunction "1_1") (pintype "passive"))
      (node (ref "U2") (pin "A3") (pinfunction "VSS_A3") (pintype "passive"))
      (node (ref "U2") (pin "A38") (pinfunction "VSS_A38") (pintype "passive"))
      (node (ref "U2") (pin "A40") (pinfunction "VSS_A40") (pintype "passive"))
      (node (ref "U2") (pin "A42") (pinfunction "VSS_A42") (pintype "passive"))
      (node (ref "U2") (pin "A44") (pinfunction "VSS_A44") (pintype "passive"))
      (node (ref "U2") (pin "A5") (pinfunction "VSS_A5") (pintype "passive"))
      (node (ref "U2") (pin "A7") (pinfunction "VSS_A7") (pintype "passive"))
      (node (ref "U2") (pin "AA1") (pinfunction "VSS_AA1") (pintype "passive"))
      (node (ref "U2") (pin "AA11") (pinfunction "VSS_AA11") (pintype "passive"))
      (node (ref "U2") (pin "AA13") (pinfunction "VSS_AA13") (pintype "passive"))
      (node (ref "U2") (pin "AA15") (pinfunction "VSS_AA15") (pintype "passive"))
      (node (ref "U2") (pin "AA17") (pinfunction "VSS_AA17") (pintype "passive"))
      (node (ref "U2") (pin "AA19") (pinfunction "VSS_AA19") (pintype "passive"))
      (node (ref "U2") (pin "AA21") (pinfunction "VSS_AA21") (pintype "passive"))
      (node (ref "U2") (pin "AA24") (pinfunction "VSS_AA24") (pintype "passive"))
      (node (ref "U2") (pin "AA26") (pinfunction "VSS_AA26") (pintype "passive"))
      (node (ref "U2") (pin "AA28") (pinfunction "VSS_AA28") (pintype "passive"))
      (node (ref "U2") (pin "AA3") (pinfunction "VSS_AA3") (pintype "passive"))
      (node (ref "U2") (pin "AA30") (pinfunction "VSS_AA30") (pintype "passive"))
      (node (ref "U2") (pin "AA32") (pinfunction "VSS_AA32") (pintype "passive"))
      (node (ref "U2") (pin "AA34") (pinfunction "VSS_AA34") (pintype "passive"))
      (node (ref "U2") (pin "AA36") (pinfunction "VSS_AA36") (pintype "passive"))
      (node (ref "U2") (pin "AA38") (pinfunction "VSS_AA38") (pintype "passive"))
      (node (ref "U2") (pin "AA40") (pinfunction "VSS_AA40") (pintype "passive"))
      (node (ref "U2") (pin "AA42") (pinfunction "VSS_AA42") (pintype "passive"))
      (node (ref "U2") (pin "AA44") (pinfunction "VSS_AA44") (pintype "passive"))
      (node (ref "U2") (pin "AA5") (pinfunction "VSS_AA5") (pintype "passive"))
      (node (ref "U2") (pin "AA7") (pinfunction "VSS_AA7") (pintype "passive"))
      (node (ref "U2") (pin "AA9") (pinfunction "VSS_AA9") (pintype "passive"))
      (node (ref "U2") (pin "AB10") (pinfunction "VSS_AB10") (pintype "passive"))
      (node (ref "U2") (pin "AB12") (pinfunction "VSS_AB12") (pintype "passive"))
      (node (ref "U2") (pin "AB14") (pinfunction "VSS_AB14") (pintype "passive"))
      (node (ref "U2") (pin "AB16") (pinfunction "VSS_AB16") (pintype "passive"))
      (node (ref "U2") (pin "AB18") (pinfunction "VSS_AB18") (pintype "passive"))
      (node (ref "U2") (pin "AB2") (pinfunction "VSS_AB2") (pintype "passive"))
      (node (ref "U2") (pin "AB20") (pinfunction "VSS_AB20") (pintype "passive"))
      (node (ref "U2") (pin "AB22") (pinfunction "VSS_AB22") (pintype "passive"))
      (node (ref "U2") (pin "AB23") (pinfunction "VSS_AB23") (pintype "passive"))
      (node (ref "U2") (pin "AB25") (pinfunction "VSS_AB25") (pintype "passive"))
      (node (ref "U2") (pin "AB27") (pinfunction "VSS_AB27") (pintype "passive"))
      (node (ref "U2") (pin "AB29") (pinfunction "VSS_AB29") (pintype "passive"))
      (node (ref "U2") (pin "AB31") (pinfunction "VSS_AB31") (pintype "passive"))
      (node (ref "U2") (pin "AB33") (pinfunction "VSS_AB33") (pintype "passive"))
      (node (ref "U2") (pin "AB35") (pinfunction "VSS_AB35") (pintype "passive"))
      (node (ref "U2") (pin "AB37") (pinfunction "VSS_AB37") (pintype "passive"))
      (node (ref "U2") (pin "AB39") (pinfunction "VSS_AB39") (pintype "passive"))
      (node (ref "U2") (pin "AB4") (pinfunction "VSS_AB4") (pintype "passive"))
      (node (ref "U2") (pin "AB41") (pinfunction "VSS_AB41") (pintype "passive"))
      (node (ref "U2") (pin "AB43") (pinfunction "VSS_AB43") (pintype "passive"))
      (node (ref "U2") (pin "AB6") (pinfunction "VSS_AB6") (pintype "passive"))
      (node (ref "U2") (pin "AB8") (pinfunction "VSS_AB8") (pintype "passive"))
      (node (ref "U2") (pin "AC10") (pinfunction "VSS_AC10") (pintype "passive"))
      (node (ref "U2") (pin "AC12") (pinfunction "VSS_AC12") (pintype "passive"))
      (node (ref "U2") (pin "AC14") (pinfunction "VSS_AC14") (pintype "passive"))
      (node (ref "U2") (pin "AC16") (pinfunction "VSS_AC16") (pintype "passive"))
      (node (ref "U2") (pin "AC18") (pinfunction "VSS_AC18") (pintype "passive"))
      (node (ref "U2") (pin "AC2") (pinfunction "VSS_AC2") (pintype "passive"))
      (node (ref "U2") (pin "AC20") (pinfunction "VSS_AC20") (pintype "passive"))
      (node (ref "U2") (pin "AC22") (pinfunction "VSS_AC22") (pintype "passive"))
      (node (ref "U2") (pin "AC23") (pinfunction "VSS_AC23") (pintype "passive"))
      (node (ref "U2") (pin "AC25") (pinfunction "VSS_AC25") (pintype "passive"))
      (node (ref "U2") (pin "AC29") (pinfunction "VSS_AC29") (pintype "passive"))
      (node (ref "U2") (pin "AC31") (pinfunction "VSS_AC31") (pintype "passive"))
      (node (ref "U2") (pin "AC33") (pinfunction "VSS_AC33") (pintype "passive"))
      (node (ref "U2") (pin "AC35") (pinfunction "VSS_AC35") (pintype "passive"))
      (node (ref "U2") (pin "AC37") (pinfunction "VSS_AC37") (pintype "passive"))
      (node (ref "U2") (pin "AC39") (pinfunction "VSS_AC39") (pintype "passive"))
      (node (ref "U2") (pin "AC4") (pinfunction "VSS_AC4") (pintype "passive"))
      (node (ref "U2") (pin "AC41") (pinfunction "VSS_AC41") (pintype "passive"))
      (node (ref "U2") (pin "AC43") (pinfunction "VSS_AC43") (pintype "passive"))
      (node (ref "U2") (pin "AC6") (pinfunction "VSS_AC6") (pintype "passive"))
      (node (ref "U2") (pin "AC8") (pinfunction "VSS_AC8") (pintype "passive"))
      (node (ref "U2") (pin "AD1") (pinfunction "VSS_AD1") (pintype "passive"))
      (node (ref "U2") (pin "AD11") (pinfunction "VSS_AD11") (pintype "passive"))
      (node (ref "U2") (pin "AD13") (pinfunction "VSS_AD13") (pintype "passive"))
      (node (ref "U2") (pin "AD15") (pinfunction "VSS_AD15") (pintype "passive"))
      (node (ref "U2") (pin "AD17") (pinfunction "VSS_AD17") (pintype "passive"))
      (node (ref "U2") (pin "AD19") (pinfunction "VSS_AD19") (pintype "passive"))
      (node (ref "U2") (pin "AD21") (pinfunction "VSS_AD21") (pintype "passive"))
      (node (ref "U2") (pin "AD24") (pinfunction "VSS_AD24") (pintype "passive"))
      (node (ref "U2") (pin "AD26") (pinfunction "VSS_AD26") (pintype "passive"))
      (node (ref "U2") (pin "AD28") (pinfunction "VSS_AD28") (pintype "passive"))
      (node (ref "U2") (pin "AD3") (pinfunction "VSS_AD3") (pintype "passive"))
      (node (ref "U2") (pin "AD30") (pinfunction "VSS_AD30") (pintype "passive"))
      (node (ref "U2") (pin "AD32") (pinfunction "VSS_AD32") (pintype "passive"))
      (node (ref "U2") (pin "AD34") (pinfunction "VSS_AD34") (pintype "passive"))
      (node (ref "U2") (pin "AD36") (pinfunction "VSS_AD36") (pintype "passive"))
      (node (ref "U2") (pin "AD38") (pinfunction "VSS_AD38") (pintype "passive"))
      (node (ref "U2") (pin "AD40") (pinfunction "VSS_AD40") (pintype "passive"))
      (node (ref "U2") (pin "AD42") (pinfunction "VSS_AD42") (pintype "passive"))
      (node (ref "U2") (pin "AD44") (pinfunction "VSS_AD44") (pintype "passive"))
      (node (ref "U2") (pin "AD5") (pinfunction "VSS_AD5") (pintype "passive"))
      (node (ref "U2") (pin "AD7") (pinfunction "VSS_AD7") (pintype "passive"))
      (node (ref "U2") (pin "AD9") (pinfunction "VSS_AD9") (pintype "passive"))
      (node (ref "U2") (pin "AE10") (pinfunction "VSS_AE10") (pintype "passive"))
      (node (ref "U2") (pin "AE12") (pinfunction "VSS_AE12") (pintype "passive"))
      (node (ref "U2") (pin "AE14") (pinfunction "VSS_AE14") (pintype "passive"))
      (node (ref "U2") (pin "AE16") (pinfunction "VSS_AE16") (pintype "passive"))
      (node (ref "U2") (pin "AE18") (pinfunction "VSS_AE18") (pintype "passive"))
      (node (ref "U2") (pin "AE2") (pinfunction "VSS_AE2") (pintype "passive"))
      (node (ref "U2") (pin "AE20") (pinfunction "VSS_AE20") (pintype "passive"))
      (node (ref "U2") (pin "AE22") (pinfunction "VSS_AE22") (pintype "passive"))
      (node (ref "U2") (pin "AE23") (pinfunction "VSS_AE23") (pintype "passive"))
      (node (ref "U2") (pin "AE25") (pinfunction "VSS_AE25") (pintype "passive"))
      (node (ref "U2") (pin "AE27") (pinfunction "VSS_AE27") (pintype "passive"))
      (node (ref "U2") (pin "AE29") (pinfunction "VSS_AE29") (pintype "passive"))
      (node (ref "U2") (pin "AE31") (pinfunction "VSS_AE31") (pintype "passive"))
      (node (ref "U2") (pin "AE33") (pinfunction "VSS_AE33") (pintype "passive"))
      (node (ref "U2") (pin "AE35") (pinfunction "VSS_AE35") (pintype "passive"))
      (node (ref "U2") (pin "AE37") (pinfunction "VSS_AE37") (pintype "passive"))
      (node (ref "U2") (pin "AE39") (pinfunction "VSS_AE39") (pintype "passive"))
      (node (ref "U2") (pin "AE4") (pinfunction "VSS_AE4") (pintype "passive"))
      (node (ref "U2") (pin "AE41") (pinfunction "VSS_AE41") (pintype "passive"))
      (node (ref "U2") (pin "AE43") (pinfunction "VSS_AE43") (pintype "passive"))
      (node (ref "U2") (pin "AE6") (pinfunction "VSS_AE6") (pintype "passive"))
      (node (ref "U2") (pin "AE8") (pinfunction "VSS_AE8") (pintype "passive"))
      (node (ref "U2") (pin "AF1") (pinfunction "VSS_AF1") (pintype "passive"))
      (node (ref "U2") (pin "AF11") (pinfunction "VSS_AF11") (pintype "passive"))
      (node (ref "U2") (pin "AF13") (pinfunction "VSS_AF13") (pintype "passive"))
      (node (ref "U2") (pin "AF15") (pinfunction "VSS_AF15") (pintype "passive"))
      (node (ref "U2") (pin "AF17") (pinfunction "VSS_AF17") (pintype "passive"))
      (node (ref "U2") (pin "AF19") (pinfunction "VSS_AF19") (pintype "passive"))
      (node (ref "U2") (pin "AF21") (pinfunction "VSS_AF21") (pintype "passive"))
      (node (ref "U2") (pin "AF26") (pinfunction "VSS_AF26") (pintype "passive"))
      (node (ref "U2") (pin "AF3") (pinfunction "VSS_AF3") (pintype "passive"))
      (node (ref "U2") (pin "AF30") (pinfunction "VSS_AF30") (pintype "passive"))
      (node (ref "U2") (pin "AF34") (pinfunction "VSS_AF34") (pintype "passive"))
      (node (ref "U2") (pin "AF36") (pinfunction "VSS_AF36") (pintype "passive"))
      (node (ref "U2") (pin "AF38") (pinfunction "VSS_AF38") (pintype "passive"))
      (node (ref "U2") (pin "AF40") (pinfunction "VSS_AF40") (pintype "passive"))
      (node (ref "U2") (pin "AF42") (pinfunction "VSS_AF42") (pintype "passive"))
      (node (ref "U2") (pin "AF5") (pinfunction "VSS_AF5") (pintype "passive"))
      (node (ref "U2") (pin "AF7") (pinfunction "VSS_AF7") (pintype "passive"))
      (node (ref "U2") (pin "AF9") (pinfunction "VSS_AF9") (pintype "passive"))
      (node (ref "U2") (pin "AG10") (pinfunction "VSS_AG10") (pintype "passive"))
      (node (ref "U2") (pin "AG12") (pinfunction "VSS_AG12") (pintype "passive"))
      (node (ref "U2") (pin "AG14") (pinfunction "VSS_AG14") (pintype "passive"))
      (node (ref "U2") (pin "AG16") (pinfunction "VSS_AG16") (pintype "passive"))
      (node (ref "U2") (pin "AG18") (pinfunction "VSS_AG18") (pintype "passive"))
      (node (ref "U2") (pin "AG2") (pinfunction "VSS_AG2") (pintype "passive"))
      (node (ref "U2") (pin "AG20") (pinfunction "VSS_AG20") (pintype "passive"))
      (node (ref "U2") (pin "AG22") (pinfunction "VSS_AG22") (pintype "passive"))
      (node (ref "U2") (pin "AG23") (pinfunction "VSS_AG23") (pintype "passive"))
      (node (ref "U2") (pin "AG25") (pinfunction "VSS_AG25") (pintype "passive"))
      (node (ref "U2") (pin "AG27") (pinfunction "VSS_AG27") (pintype "passive"))
      (node (ref "U2") (pin "AG29") (pinfunction "VSS_AG29") (pintype "passive"))
      (node (ref "U2") (pin "AG31") (pinfunction "VSS_AG31") (pintype "passive"))
      (node (ref "U2") (pin "AG33") (pinfunction "VSS_AG33") (pintype "passive"))
      (node (ref "U2") (pin "AG35") (pinfunction "VSS_AG35") (pintype "passive"))
      (node (ref "U2") (pin "AG4") (pinfunction "VSS_AG4") (pintype "passive"))
      (node (ref "U2") (pin "AG6") (pinfunction "VSS_AG6") (pintype "passive"))
      (node (ref "U2") (pin "AG8") (pinfunction "VSS_AG8") (pintype "passive"))
      (node (ref "U2") (pin "AH1") (pinfunction "VSS_AH1") (pintype "passive"))
      (node (ref "U2") (pin "AH11") (pinfunction "VSS_AH11") (pintype "passive"))
      (node (ref "U2") (pin "AH13") (pinfunction "VSS_AH13") (pintype "passive"))
      (node (ref "U2") (pin "AH15") (pinfunction "VSS_AH15") (pintype "passive"))
      (node (ref "U2") (pin "AH17") (pinfunction "VSS_AH17") (pintype "passive"))
      (node (ref "U2") (pin "AH19") (pinfunction "VSS_AH19") (pintype "passive"))
      (node (ref "U2") (pin "AH21") (pinfunction "VSS_AH21") (pintype "passive"))
      (node (ref "U2") (pin "AH26") (pinfunction "VSS_AH26") (pintype "passive"))
      (node (ref "U2") (pin "AH28") (pinfunction "VSS_AH28") (pintype "passive"))
      (node (ref "U2") (pin "AH3") (pinfunction "VSS_AH3") (pintype "passive"))
      (node (ref "U2") (pin "AH30") (pinfunction "VSS_AH30") (pintype "passive"))
      (node (ref "U2") (pin "AH32") (pinfunction "VSS_AH32") (pintype "passive"))
      (node (ref "U2") (pin "AH34") (pinfunction "VSS_AH34") (pintype "passive"))
      (node (ref "U2") (pin "AH40") (pinfunction "VSS_AH40") (pintype "passive"))
      (node (ref "U2") (pin "AH5") (pinfunction "VSS_AH5") (pintype "passive"))
      (node (ref "U2") (pin "AH7") (pinfunction "VSS_AH7") (pintype "passive"))
      (node (ref "U2") (pin "AH9") (pinfunction "VSS_AH9") (pintype "passive"))
      (node (ref "U2") (pin "AJ10") (pinfunction "VSS_AJ10") (pintype "passive"))
      (node (ref "U2") (pin "AJ12") (pinfunction "VSS_AJ12") (pintype "passive"))
      (node (ref "U2") (pin "AJ14") (pinfunction "VSS_AJ14") (pintype "passive"))
      (node (ref "U2") (pin "AJ16") (pinfunction "VSS_AJ16") (pintype "passive"))
      (node (ref "U2") (pin "AJ18") (pinfunction "VSS_AJ18") (pintype "passive"))
      (node (ref "U2") (pin "AJ2") (pinfunction "VSS_AJ2") (pintype "passive"))
      (node (ref "U2") (pin "AJ20") (pinfunction "VSS_AJ20") (pintype "passive"))
      (node (ref "U2") (pin "AJ22") (pinfunction "VSS_AJ22") (pintype "passive"))
      (node (ref "U2") (pin "AJ25") (pinfunction "VSS_AJ25") (pintype "passive"))
      (node (ref "U2") (pin "AJ29") (pinfunction "VSS_AJ29") (pintype "passive"))
      (node (ref "U2") (pin "AJ31") (pinfunction "VSS_AJ31") (pintype "passive"))
      (node (ref "U2") (pin "AJ33") (pinfunction "VSS_AJ33") (pintype "passive"))
      (node (ref "U2") (pin "AJ35") (pinfunction "VSS_AJ35") (pintype "passive"))
      (node (ref "U2") (pin "AJ37") (pinfunction "VSS_AJ37") (pintype "passive"))
      (node (ref "U2") (pin "AJ39") (pinfunction "VSS_AJ39") (pintype "passive"))
      (node (ref "U2") (pin "AJ4") (pinfunction "VSS_AJ4") (pintype "passive"))
      (node (ref "U2") (pin "AJ41") (pinfunction "VSS_AJ41") (pintype "passive"))
      (node (ref "U2") (pin "AJ43") (pinfunction "VSS_AJ43") (pintype "passive"))
      (node (ref "U2") (pin "AJ6") (pinfunction "VSS_AJ6") (pintype "passive"))
      (node (ref "U2") (pin "AJ8") (pinfunction "VSS_AJ8") (pintype "passive"))
      (node (ref "U2") (pin "AK1") (pinfunction "VSS_AK1") (pintype "passive"))
      (node (ref "U2") (pin "AK11") (pinfunction "VSS_AK11") (pintype "passive"))
      (node (ref "U2") (pin "AK13") (pinfunction "VSS_AK13") (pintype "passive"))
      (node (ref "U2") (pin "AK15") (pinfunction "VSS_AK15") (pintype "passive"))
      (node (ref "U2") (pin "AK17") (pinfunction "VSS_AK17") (pintype "passive"))
      (node (ref "U2") (pin "AK19") (pinfunction "VSS_AK19") (pintype "passive"))
      (node (ref "U2") (pin "AK21") (pinfunction "VSS_AK21") (pintype "passive"))
      (node (ref "U2") (pin "AK24") (pinfunction "VSS_AK24") (pintype "passive"))
      (node (ref "U2") (pin "AK26") (pinfunction "VSS_AK26") (pintype "passive"))
      (node (ref "U2") (pin "AK28") (pinfunction "VSS_AK28") (pintype "passive"))
      (node (ref "U2") (pin "AK3") (pinfunction "VSS_AK3") (pintype "passive"))
      (node (ref "U2") (pin "AK30") (pinfunction "VSS_AK30") (pintype "passive"))
      (node (ref "U2") (pin "AK32") (pinfunction "VSS_AK32") (pintype "passive"))
      (node (ref "U2") (pin "AK34") (pinfunction "VSS_AK34") (pintype "passive"))
      (node (ref "U2") (pin "AK36") (pinfunction "VSS_AK36") (pintype "passive"))
      (node (ref "U2") (pin "AK38") (pinfunction "VSS_AK38") (pintype "passive"))
      (node (ref "U2") (pin "AK42") (pinfunction "VSS_AK42") (pintype "passive"))
      (node (ref "U2") (pin "AK44") (pinfunction "VSS_AK44") (pintype "passive"))
      (node (ref "U2") (pin "AK5") (pinfunction "VSS_AK5") (pintype "passive"))
      (node (ref "U2") (pin "AK7") (pinfunction "VSS_AK7") (pintype "passive"))
      (node (ref "U2") (pin "AK9") (pinfunction "VSS_AK9") (pintype "passive"))
      (node (ref "U2") (pin "AL10") (pinfunction "VSS_AL10") (pintype "passive"))
      (node (ref "U2") (pin "AL12") (pinfunction "VSS_AL12") (pintype "passive"))
      (node (ref "U2") (pin "AL14") (pinfunction "VSS_AL14") (pintype "passive"))
      (node (ref "U2") (pin "AL16") (pinfunction "VSS_AL16") (pintype "passive"))
      (node (ref "U2") (pin "AL18") (pinfunction "VSS_AL18") (pintype "passive"))
      (node (ref "U2") (pin "AL2") (pinfunction "VSS_AL2") (pintype "passive"))
      (node (ref "U2") (pin "AL20") (pinfunction "VSS_AL20") (pintype "passive"))
      (node (ref "U2") (pin "AL22") (pinfunction "VSS_AL22") (pintype "passive"))
      (node (ref "U2") (pin "AL23") (pinfunction "VSS_AL23") (pintype "passive"))
      (node (ref "U2") (pin "AL25") (pinfunction "VSS_AL25") (pintype "passive"))
      (node (ref "U2") (pin "AL27") (pinfunction "VSS_AL27") (pintype "passive"))
      (node (ref "U2") (pin "AL29") (pinfunction "VSS_AL29") (pintype "passive"))
      (node (ref "U2") (pin "AL31") (pinfunction "VSS_AL31") (pintype "passive"))
      (node (ref "U2") (pin "AL33") (pinfunction "VSS_AL33") (pintype "passive"))
      (node (ref "U2") (pin "AL35") (pinfunction "VSS_AL35") (pintype "passive"))
      (node (ref "U2") (pin "AL37") (pinfunction "VSS_AL37") (pintype "passive"))
      (node (ref "U2") (pin "AL39") (pinfunction "VSS_AL39") (pintype "passive"))
      (node (ref "U2") (pin "AL4") (pinfunction "VSS_AL4") (pintype "passive"))
      (node (ref "U2") (pin "AL41") (pinfunction "VSS_AL41") (pintype "passive"))
      (node (ref "U2") (pin "AL43") (pinfunction "VSS_AL43") (pintype "passive"))
      (node (ref "U2") (pin "AL6") (pinfunction "VSS_AL6") (pintype "passive"))
      (node (ref "U2") (pin "AL8") (pinfunction "VSS_AL8") (pintype "passive"))
      (node (ref "U2") (pin "AM1") (pinfunction "VSS_AM1") (pintype "passive"))
      (node (ref "U2") (pin "AM11") (pinfunction "VSS_AM11") (pintype "passive"))
      (node (ref "U2") (pin "AM13") (pinfunction "VSS_AM13") (pintype "passive"))
      (node (ref "U2") (pin "AM15") (pinfunction "VSS_AM15") (pintype "passive"))
      (node (ref "U2") (pin "AM17") (pinfunction "VSS_AM17") (pintype "passive"))
      (node (ref "U2") (pin "AM19") (pinfunction "VSS_AM19") (pintype "passive"))
      (node (ref "U2") (pin "AM21") (pinfunction "VSS_AM21") (pintype "passive"))
      (node (ref "U2") (pin "AM24") (pinfunction "VSS_AM24") (pintype "passive"))
      (node (ref "U2") (pin "AM26") (pinfunction "VSS_AM26") (pintype "passive"))
      (node (ref "U2") (pin "AM28") (pinfunction "VSS_AM28") (pintype "passive"))
      (node (ref "U2") (pin "AM3") (pinfunction "VSS_AM3") (pintype "passive"))
      (node (ref "U2") (pin "AM30") (pinfunction "VSS_AM30") (pintype "passive"))
      (node (ref "U2") (pin "AM32") (pinfunction "VSS_AM32") (pintype "passive"))
      (node (ref "U2") (pin "AM34") (pinfunction "VSS_AM34") (pintype "passive"))
      (node (ref "U2") (pin "AM36") (pinfunction "VSS_AM36") (pintype "passive"))
      (node (ref "U2") (pin "AM38") (pinfunction "VSS_AM38") (pintype "passive"))
      (node (ref "U2") (pin "AM44") (pinfunction "VSS_AM44") (pintype "passive"))
      (node (ref "U2") (pin "AM5") (pinfunction "VSS_AM5") (pintype "passive"))
      (node (ref "U2") (pin "AM7") (pinfunction "VSS_AM7") (pintype "passive"))
      (node (ref "U2") (pin "AM9") (pinfunction "VSS_AM9") (pintype "passive"))
      (node (ref "U2") (pin "AN14") (pinfunction "VSS_AN14") (pintype "passive"))
      (node (ref "U2") (pin "AN16") (pinfunction "VSS_AN16") (pintype "passive"))
      (node (ref "U2") (pin "AN18") (pinfunction "VSS_AN18") (pintype "passive"))
      (node (ref "U2") (pin "AN2") (pinfunction "VSS_AN2") (pintype "passive"))
      (node (ref "U2") (pin "AN20") (pinfunction "VSS_AN20") (pintype "passive"))
      (node (ref "U2") (pin "AN22") (pinfunction "VSS_AN22") (pintype "passive"))
      (node (ref "U2") (pin "AN23") (pinfunction "VSS_AN23") (pintype "passive"))
      (node (ref "U2") (pin "AN25") (pinfunction "VSS_AN25") (pintype "passive"))
      (node (ref "U2") (pin "AN27") (pinfunction "VSS_AN27") (pintype "passive"))
      (node (ref "U2") (pin "AN29") (pinfunction "VSS_AN29") (pintype "passive"))
      (node (ref "U2") (pin "AN31") (pinfunction "VSS_AN31") (pintype "passive"))
      (node (ref "U2") (pin "AN33") (pinfunction "VSS_AN33") (pintype "passive"))
      (node (ref "U2") (pin "AN35") (pinfunction "VSS_AN35") (pintype "passive"))
      (node (ref "U2") (pin "AN37") (pinfunction "VSS_AN37") (pintype "passive"))
      (node (ref "U2") (pin "AN39") (pinfunction "VSS_AN39") (pintype "passive"))
      (node (ref "U2") (pin "AN4") (pinfunction "VSS_AN4") (pintype "passive"))
      (node (ref "U2") (pin "AN41") (pinfunction "VSS_AN41") (pintype "passive"))
      (node (ref "U2") (pin "AN43") (pinfunction "VSS_AN43") (pintype "passive"))
      (node (ref "U2") (pin "AN6") (pinfunction "VSS_AN6") (pintype "passive"))
      (node (ref "U2") (pin "AN8") (pinfunction "VSS_AN8") (pintype "passive"))
      (node (ref "U2") (pin "AP1") (pinfunction "VSS_AP1") (pintype "passive"))
      (node (ref "U2") (pin "AP11") (pinfunction "VSS_AP11") (pintype "passive"))
      (node (ref "U2") (pin "AP13") (pinfunction "VSS_AP13") (pintype "passive"))
      (node (ref "U2") (pin "AP15") (pinfunction "VSS_AP15") (pintype "passive"))
      (node (ref "U2") (pin "AP17") (pinfunction "VSS_AP17") (pintype "passive"))
      (node (ref "U2") (pin "AP19") (pinfunction "VSS_AP19") (pintype "passive"))
      (node (ref "U2") (pin "AP21") (pinfunction "VSS_AP21") (pintype "passive"))
      (node (ref "U2") (pin "AP24") (pinfunction "VSS_AP24") (pintype "passive"))
      (node (ref "U2") (pin "AP26") (pinfunction "VSS_AP26") (pintype "passive"))
      (node (ref "U2") (pin "AP28") (pinfunction "VSS_AP28") (pintype "passive"))
      (node (ref "U2") (pin "AP3") (pinfunction "VSS_AP3") (pintype "passive"))
      (node (ref "U2") (pin "AP30") (pinfunction "VSS_AP30") (pintype "passive"))
      (node (ref "U2") (pin "AP32") (pinfunction "VSS_AP32") (pintype "passive"))
      (node (ref "U2") (pin "AP34") (pinfunction "VSS_AP34") (pintype "passive"))
      (node (ref "U2") (pin "AP36") (pinfunction "VSS_AP36") (pintype "passive"))
      (node (ref "U2") (pin "AP38") (pinfunction "VSS_AP38") (pintype "passive"))
      (node (ref "U2") (pin "AP40") (pinfunction "VSS_AP40") (pintype "passive"))
      (node (ref "U2") (pin "AP42") (pinfunction "VSS_AP42") (pintype "passive"))
      (node (ref "U2") (pin "AP44") (pinfunction "VSS_AP44") (pintype "passive"))
      (node (ref "U2") (pin "AP5") (pinfunction "VSS_AP5") (pintype "passive"))
      (node (ref "U2") (pin "AP7") (pinfunction "VSS_AP7") (pintype "passive"))
      (node (ref "U2") (pin "AP9") (pinfunction "VSS_AP9") (pintype "passive"))
      (node (ref "U2") (pin "AR12") (pinfunction "VSS_AR12") (pintype "passive"))
      (node (ref "U2") (pin "AR14") (pinfunction "VSS_AR14") (pintype "passive"))
      (node (ref "U2") (pin "AR16") (pinfunction "VSS_AR16") (pintype "passive"))
      (node (ref "U2") (pin "AR18") (pinfunction "VSS_AR18") (pintype "passive"))
      (node (ref "U2") (pin "AR2") (pinfunction "VSS_AR2") (pintype "passive"))
      (node (ref "U2") (pin "AR20") (pinfunction "VSS_AR20") (pintype "passive"))
      (node (ref "U2") (pin "AR22") (pinfunction "VSS_AR22") (pintype "passive"))
      (node (ref "U2") (pin "AR23") (pinfunction "VSS_AR23") (pintype "passive"))
      (node (ref "U2") (pin "AR25") (pinfunction "VSS_AR25") (pintype "passive"))
      (node (ref "U2") (pin "AR27") (pinfunction "VSS_AR27") (pintype "passive"))
      (node (ref "U2") (pin "AR29") (pinfunction "VSS_AR29") (pintype "passive"))
      (node (ref "U2") (pin "AR31") (pinfunction "VSS_AR31") (pintype "passive"))
      (node (ref "U2") (pin "AR33") (pinfunction "VSS_AR33") (pintype "passive"))
      (node (ref "U2") (pin "AR35") (pinfunction "VSS_AR35") (pintype "passive"))
      (node (ref "U2") (pin "AR37") (pinfunction "VSS_AR37") (pintype "passive"))
      (node (ref "U2") (pin "AR39") (pinfunction "VSS_AR39") (pintype "passive"))
      (node (ref "U2") (pin "AR4") (pinfunction "VSS_AR4") (pintype "passive"))
      (node (ref "U2") (pin "AR41") (pinfunction "VSS_AR41") (pintype "passive"))
      (node (ref "U2") (pin "AR43") (pinfunction "VSS_AR43") (pintype "passive"))
      (node (ref "U2") (pin "AR6") (pinfunction "VSS_AR6") (pintype "passive"))
      (node (ref "U2") (pin "AR8") (pinfunction "VSS_AR8") (pintype "passive"))
      (node (ref "U2") (pin "AT1") (pinfunction "VSS_AT1") (pintype "passive"))
      (node (ref "U2") (pin "AT11") (pinfunction "VSS_AT11") (pintype "passive"))
      (node (ref "U2") (pin "AT13") (pinfunction "VSS_AT13") (pintype "passive"))
      (node (ref "U2") (pin "AT15") (pinfunction "VSS_AT15") (pintype "passive"))
      (node (ref "U2") (pin "AT17") (pinfunction "VSS_AT17") (pintype "passive"))
      (node (ref "U2") (pin "AT19") (pinfunction "VSS_AT19") (pintype "passive"))
      (node (ref "U2") (pin "AT21") (pinfunction "VSS_AT21") (pintype "passive"))
      (node (ref "U2") (pin "AT24") (pinfunction "VSS_AT24") (pintype "passive"))
      (node (ref "U2") (pin "AT26") (pinfunction "VSS_AT26") (pintype "passive"))
      (node (ref "U2") (pin "AT28") (pinfunction "VSS_AT28") (pintype "passive"))
      (node (ref "U2") (pin "AT3") (pinfunction "VSS_AT3") (pintype "passive"))
      (node (ref "U2") (pin "AT30") (pinfunction "VSS_AT30") (pintype "passive"))
      (node (ref "U2") (pin "AT32") (pinfunction "VSS_AT32") (pintype "passive"))
      (node (ref "U2") (pin "AT34") (pinfunction "VSS_AT34") (pintype "passive"))
      (node (ref "U2") (pin "AT36") (pinfunction "VSS_AT36") (pintype "passive"))
      (node (ref "U2") (pin "AT38") (pinfunction "VSS_AT38") (pintype "passive"))
      (node (ref "U2") (pin "AT40") (pinfunction "VSS_AT40") (pintype "passive"))
      (node (ref "U2") (pin "AT42") (pinfunction "VSS_AT42") (pintype "passive"))
      (node (ref "U2") (pin "AT44") (pinfunction "VSS_AT44") (pintype "passive"))
      (node (ref "U2") (pin "AT5") (pinfunction "VSS_AT5") (pintype "passive"))
      (node (ref "U2") (pin "AT7") (pinfunction "VSS_AT7") (pintype "passive"))
      (node (ref "U2") (pin "AT9") (pinfunction "VSS_AT9") (pintype "passive"))
      (node (ref "U2") (pin "AU10") (pinfunction "VSS_AU10") (pintype "passive"))
      (node (ref "U2") (pin "AU16") (pinfunction "VSS_AU16") (pintype "passive"))
      (node (ref "U2") (pin "AU2") (pinfunction "VSS_AU2") (pintype "passive"))
      (node (ref "U2") (pin "AU20") (pinfunction "VSS_AU20") (pintype "passive"))
      (node (ref "U2") (pin "AU23") (pinfunction "VSS_AU23") (pintype "passive"))
      (node (ref "U2") (pin "AU25") (pinfunction "VSS_AU25") (pintype "passive"))
      (node (ref "U2") (pin "AU27") (pinfunction "VSS_AU27") (pintype "passive"))
      (node (ref "U2") (pin "AU29") (pinfunction "VSS_AU29") (pintype "passive"))
      (node (ref "U2") (pin "AU31") (pinfunction "VSS_AU31") (pintype "passive"))
      (node (ref "U2") (pin "AU33") (pinfunction "VSS_AU33") (pintype "passive"))
      (node (ref "U2") (pin "AU35") (pinfunction "VSS_AU35") (pintype "passive"))
      (node (ref "U2") (pin "AU37") (pinfunction "VSS_AU37") (pintype "passive"))
      (node (ref "U2") (pin "AU39") (pinfunction "VSS_AU39") (pintype "passive"))
      (node (ref "U2") (pin "AU4") (pinfunction "VSS_AU4") (pintype "passive"))
      (node (ref "U2") (pin "AU41") (pinfunction "VSS_AU41") (pintype "passive"))
      (node (ref "U2") (pin "AU43") (pinfunction "VSS_AU43") (pintype "passive"))
      (node (ref "U2") (pin "AV1") (pinfunction "VSS_AV1") (pintype "passive"))
      (node (ref "U2") (pin "AV15") (pinfunction "VSS_AV15") (pintype "passive"))
      (node (ref "U2") (pin "AV19") (pinfunction "VSS_AV19") (pintype "passive"))
      (node (ref "U2") (pin "AV21") (pinfunction "VSS_AV21") (pintype "passive"))
      (node (ref "U2") (pin "AV24") (pinfunction "VSS_AV24") (pintype "passive"))
      (node (ref "U2") (pin "AV26") (pinfunction "VSS_AV26") (pintype "passive"))
      (node (ref "U2") (pin "AV28") (pinfunction "VSS_AV28") (pintype "passive"))
      (node (ref "U2") (pin "AV3") (pinfunction "VSS_AV3") (pintype "passive"))
      (node (ref "U2") (pin "AV30") (pinfunction "VSS_AV30") (pintype "passive"))
      (node (ref "U2") (pin "AV32") (pinfunction "VSS_AV32") (pintype "passive"))
      (node (ref "U2") (pin "AV34") (pinfunction "VSS_AV34") (pintype "passive"))
      (node (ref "U2") (pin "AV36") (pinfunction "VSS_AV36") (pintype "passive"))
      (node (ref "U2") (pin "AV38") (pinfunction "VSS_AV38") (pintype "passive"))
      (node (ref "U2") (pin "AV40") (pinfunction "VSS_AV40") (pintype "passive"))
      (node (ref "U2") (pin "AV42") (pinfunction "VSS_AV42") (pintype "passive"))
      (node (ref "U2") (pin "AV44") (pinfunction "VSS_AV44") (pintype "passive"))
      (node (ref "U2") (pin "AV5") (pinfunction "VSS_AV5") (pintype "passive"))
      (node (ref "U2") (pin "AW10") (pinfunction "VSS_AW10") (pintype "passive"))
      (node (ref "U2") (pin "AW12") (pinfunction "VSS_AW12") (pintype "passive"))
      (node (ref "U2") (pin "AW16") (pinfunction "VSS_AW16") (pintype "passive"))
      (node (ref "U2") (pin "AW18") (pinfunction "VSS_AW18") (pintype "passive"))
      (node (ref "U2") (pin "AW20") (pinfunction "VSS_AW20") (pintype "passive"))
      (node (ref "U2") (pin "AW22") (pinfunction "VSS_AW22") (pintype "passive"))
      (node (ref "U2") (pin "AW23") (pinfunction "VSS_AW23") (pintype "passive"))
      (node (ref "U2") (pin "AW25") (pinfunction "VSS_AW25") (pintype "passive"))
      (node (ref "U2") (pin "AW27") (pinfunction "VSS_AW27") (pintype "passive"))
      (node (ref "U2") (pin "AW29") (pinfunction "VSS_AW29") (pintype "passive"))
      (node (ref "U2") (pin "AW31") (pinfunction "VSS_AW31") (pintype "passive"))
      (node (ref "U2") (pin "AW33") (pinfunction "VSS_AW33") (pintype "passive"))
      (node (ref "U2") (pin "AW35") (pinfunction "VSS_AW35") (pintype "passive"))
      (node (ref "U2") (pin "AW37") (pinfunction "VSS_AW37") (pintype "passive"))
      (node (ref "U2") (pin "AW39") (pinfunction "VSS_AW39") (pintype "passive"))
      (node (ref "U2") (pin "AW4") (pinfunction "VSS_AW4") (pintype "passive"))
      (node (ref "U2") (pin "AW41") (pinfunction "VSS_AW41") (pintype "passive"))
      (node (ref "U2") (pin "AW43") (pinfunction "VSS_AW43") (pintype "passive"))
      (node (ref "U2") (pin "AW6") (pinfunction "VSS_AW6") (pintype "passive"))
      (node (ref "U2") (pin "AW8") (pinfunction "VSS_AW8") (pintype "passive"))
      (node (ref "U2") (pin "AY1") (pinfunction "VSS_AY1") (pintype "passive"))
      (node (ref "U2") (pin "AY11") (pinfunction "VSS_AY11") (pintype "passive"))
      (node (ref "U2") (pin "AY13") (pinfunction "VSS_AY13") (pintype "passive"))
      (node (ref "U2") (pin "AY15") (pinfunction "VSS_AY15") (pintype "passive"))
      (node (ref "U2") (pin "AY19") (pinfunction "VSS_AY19") (pintype "passive"))
      (node (ref "U2") (pin "AY24") (pinfunction "VSS_AY24") (pintype "passive"))
      (node (ref "U2") (pin "AY26") (pinfunction "VSS_AY26") (pintype "passive"))
      (node (ref "U2") (pin "AY28") (pinfunction "VSS_AY28") (pintype "passive"))
      (node (ref "U2") (pin "AY3") (pinfunction "VSS_AY3") (pintype "passive"))
      (node (ref "U2") (pin "AY30") (pinfunction "VSS_AY30") (pintype "passive"))
      (node (ref "U2") (pin "AY32") (pinfunction "VSS_AY32") (pintype "passive"))
      (node (ref "U2") (pin "AY34") (pinfunction "VSS_AY34") (pintype "passive"))
      (node (ref "U2") (pin "AY36") (pinfunction "VSS_AY36") (pintype "passive"))
      (node (ref "U2") (pin "AY38") (pinfunction "VSS_AY38") (pintype "passive"))
      (node (ref "U2") (pin "AY40") (pinfunction "VSS_AY40") (pintype "passive"))
      (node (ref "U2") (pin "AY42") (pinfunction "VSS_AY42") (pintype "passive"))
      (node (ref "U2") (pin "AY44") (pinfunction "VSS_AY44") (pintype "passive"))
      (node (ref "U2") (pin "AY5") (pinfunction "VSS_AY5") (pintype "passive"))
      (node (ref "U2") (pin "AY7") (pinfunction "VSS_AY7") (pintype "passive"))
      (node (ref "U2") (pin "AY9") (pinfunction "VSS_AY9") (pintype "passive"))
      (node (ref "U2") (pin "B2") (pinfunction "VSS_B2") (pintype "passive"))
      (node (ref "U2") (pin "B22") (pinfunction "VSS_B22") (pintype "passive"))
      (node (ref "U2") (pin "B23") (pinfunction "VSS_B23") (pintype "passive"))
      (node (ref "U2") (pin "B37") (pinfunction "VSS_B37") (pintype "passive"))
      (node (ref "U2") (pin "B39") (pinfunction "VSS_B39") (pintype "passive"))
      (node (ref "U2") (pin "B4") (pinfunction "VSS_B4") (pintype "passive"))
      (node (ref "U2") (pin "B41") (pinfunction "VSS_B41") (pintype "passive"))
      (node (ref "U2") (pin "B43") (pinfunction "VSS_B43") (pintype "passive"))
      (node (ref "U2") (pin "B6") (pinfunction "VSS_B6") (pintype "passive"))
      (node (ref "U2") (pin "B8") (pinfunction "VSS_B8") (pintype "passive"))
      (node (ref "U2") (pin "BA10") (pinfunction "VSS_BA10") (pintype "passive"))
      (node (ref "U2") (pin "BA12") (pinfunction "VSS_BA12") (pintype "passive"))
      (node (ref "U2") (pin "BA14") (pinfunction "VSS_BA14") (pintype "passive"))
      (node (ref "U2") (pin "BA16") (pinfunction "VSS_BA16") (pintype "passive"))
      (node (ref "U2") (pin "BA18") (pinfunction "VSS_BA18") (pintype "passive"))
      (node (ref "U2") (pin "BA2") (pinfunction "VSS_BA2") (pintype "passive"))
      (node (ref "U2") (pin "BA20") (pinfunction "VSS_BA20") (pintype "passive"))
      (node (ref "U2") (pin "BA22") (pinfunction "VSS_BA22") (pintype "passive"))
      (node (ref "U2") (pin "BA23") (pinfunction "VSS_BA23") (pintype "passive"))
      (node (ref "U2") (pin "BA25") (pinfunction "VSS_BA25") (pintype "passive"))
      (node (ref "U2") (pin "BA27") (pinfunction "VSS_BA27") (pintype "passive"))
      (node (ref "U2") (pin "BA29") (pinfunction "VSS_BA29") (pintype "passive"))
      (node (ref "U2") (pin "BA31") (pinfunction "VSS_BA31") (pintype "passive"))
      (node (ref "U2") (pin "BA33") (pinfunction "VSS_BA33") (pintype "passive"))
      (node (ref "U2") (pin "BA35") (pinfunction "VSS_BA35") (pintype "passive"))
      (node (ref "U2") (pin "BA37") (pinfunction "VSS_BA37") (pintype "passive"))
      (node (ref "U2") (pin "BA39") (pinfunction "VSS_BA39") (pintype "passive"))
      (node (ref "U2") (pin "BA4") (pinfunction "VSS_BA4") (pintype "passive"))
      (node (ref "U2") (pin "BA41") (pinfunction "VSS_BA41") (pintype "passive"))
      (node (ref "U2") (pin "BA43") (pinfunction "VSS_BA43") (pintype "passive"))
      (node (ref "U2") (pin "BA6") (pinfunction "VSS_BA6") (pintype "passive"))
      (node (ref "U2") (pin "BA8") (pinfunction "VSS_BA8") (pintype "passive"))
      (node (ref "U2") (pin "BB1") (pinfunction "VSS_BB1") (pintype "passive"))
      (node (ref "U2") (pin "BB24") (pinfunction "VSS_BB24") (pintype "passive"))
      (node (ref "U2") (pin "BB3") (pinfunction "VSS_BB3") (pintype "passive"))
      (node (ref "U2") (pin "BB38") (pinfunction "VSS_BB38") (pintype "passive"))
      (node (ref "U2") (pin "BB40") (pinfunction "VSS_BB40") (pintype "passive"))
      (node (ref "U2") (pin "BB42") (pinfunction "VSS_BB42") (pintype "passive"))
      (node (ref "U2") (pin "BB44") (pinfunction "VSS_BB44") (pintype "passive"))
      (node (ref "U2") (pin "BB5") (pinfunction "VSS_BB5") (pintype "passive"))
      (node (ref "U2") (pin "BB7") (pinfunction "VSS_BB7") (pintype "passive"))
      (node (ref "U2") (pin "BC2") (pinfunction "VSS_BC2") (pintype "passive"))
      (node (ref "U2") (pin "BC22") (pinfunction "VSS_BC22") (pintype "passive"))
      (node (ref "U2") (pin "BC23") (pinfunction "VSS_BC23") (pintype "passive"))
      (node (ref "U2") (pin "BC37") (pinfunction "VSS_BC37") (pintype "passive"))
      (node (ref "U2") (pin "BC39") (pinfunction "VSS_BC39") (pintype "passive"))
      (node (ref "U2") (pin "BC4") (pinfunction "VSS_BC4") (pintype "passive"))
      (node (ref "U2") (pin "BC41") (pinfunction "VSS_BC41") (pintype "passive"))
      (node (ref "U2") (pin "BC43") (pinfunction "VSS_BC43") (pintype "passive"))
      (node (ref "U2") (pin "BC6") (pinfunction "VSS_BC6") (pintype "passive"))
      (node (ref "U2") (pin "BC8") (pinfunction "VSS_BC8") (pintype "passive"))
      (node (ref "U2") (pin "BD1") (pinfunction "VSS_BD1") (pintype "passive"))
      (node (ref "U2") (pin "BD3") (pinfunction "VSS_BD3") (pintype "passive"))
      (node (ref "U2") (pin "BD38") (pinfunction "VSS_BD38") (pintype "passive"))
      (node (ref "U2") (pin "BD40") (pinfunction "VSS_BD40") (pintype "passive"))
      (node (ref "U2") (pin "BD42") (pinfunction "VSS_BD42") (pintype "passive"))
      (node (ref "U2") (pin "BD44") (pinfunction "VSS_BD44") (pintype "passive"))
      (node (ref "U2") (pin "BD7") (pinfunction "VSS_BD7") (pintype "passive"))
      (node (ref "U2") (pin "C1") (pinfunction "VSS_C1") (pintype "passive"))
      (node (ref "U2") (pin "C21") (pinfunction "VSS_C21") (pintype "passive"))
      (node (ref "U2") (pin "C3") (pinfunction "VSS_C3") (pintype "passive"))
      (node (ref "U2") (pin "C36") (pinfunction "VSS_C36") (pintype "passive"))
      (node (ref "U2") (pin "C38") (pinfunction "VSS_C38") (pintype "passive"))
      (node (ref "U2") (pin "C40") (pinfunction "VSS_C40") (pintype "passive"))
      (node (ref "U2") (pin "C42") (pinfunction "VSS_C42") (pintype "passive"))
      (node (ref "U2") (pin "C44") (pinfunction "VSS_C44") (pintype "passive"))
      (node (ref "U2") (pin "C5") (pinfunction "VSS_C5") (pintype "passive"))
      (node (ref "U2") (pin "C7") (pinfunction "VSS_C7") (pintype "passive"))
      (node (ref "U2") (pin "D10") (pinfunction "VSS_D10") (pintype "passive"))
      (node (ref "U2") (pin "D12") (pinfunction "VSS_D12") (pintype "passive"))
      (node (ref "U2") (pin "D14") (pinfunction "VSS_D14") (pintype "passive"))
      (node (ref "U2") (pin "D16") (pinfunction "VSS_D16") (pintype "passive"))
      (node (ref "U2") (pin "D18") (pinfunction "VSS_D18") (pintype "passive"))
      (node (ref "U2") (pin "D2") (pinfunction "VSS_D2") (pintype "passive"))
      (node (ref "U2") (pin "D20") (pinfunction "VSS_D20") (pintype "passive"))
      (node (ref "U2") (pin "D22") (pinfunction "VSS_D22") (pintype "passive"))
      (node (ref "U2") (pin "D23") (pinfunction "VSS_D23") (pintype "passive"))
      (node (ref "U2") (pin "D25") (pinfunction "VSS_D25") (pintype "passive"))
      (node (ref "U2") (pin "D27") (pinfunction "VSS_D27") (pintype "passive"))
      (node (ref "U2") (pin "D29") (pinfunction "VSS_D29") (pintype "passive"))
      (node (ref "U2") (pin "D31") (pinfunction "VSS_D31") (pintype "passive"))
      (node (ref "U2") (pin "D33") (pinfunction "VSS_D33") (pintype "passive"))
      (node (ref "U2") (pin "D35") (pinfunction "VSS_D35") (pintype "passive"))
      (node (ref "U2") (pin "D37") (pinfunction "VSS_D37") (pintype "passive"))
      (node (ref "U2") (pin "D39") (pinfunction "VSS_D39") (pintype "passive"))
      (node (ref "U2") (pin "D4") (pinfunction "VSS_D4") (pintype "passive"))
      (node (ref "U2") (pin "D41") (pinfunction "VSS_D41") (pintype "passive"))
      (node (ref "U2") (pin "D43") (pinfunction "VSS_D43") (pintype "passive"))
      (node (ref "U2") (pin "D6") (pinfunction "VSS_D6") (pintype "passive"))
      (node (ref "U2") (pin "D8") (pinfunction "VSS_D8") (pintype "passive"))
      (node (ref "U2") (pin "E1") (pinfunction "VSS_E1") (pintype "passive"))
      (node (ref "U2") (pin "E11") (pinfunction "VSS_E11") (pintype "passive"))
      (node (ref "U2") (pin "E13") (pinfunction "VSS_E13") (pintype "passive"))
      (node (ref "U2") (pin "E15") (pinfunction "VSS_E15") (pintype "passive"))
      (node (ref "U2") (pin "E17") (pinfunction "VSS_E17") (pintype "passive"))
      (node (ref "U2") (pin "E19") (pinfunction "VSS_E19") (pintype "passive"))
      (node (ref "U2") (pin "E21") (pinfunction "VSS_E21") (pintype "passive"))
      (node (ref "U2") (pin "E24") (pinfunction "VSS_E24") (pintype "passive"))
      (node (ref "U2") (pin "E26") (pinfunction "VSS_E26") (pintype "passive"))
      (node (ref "U2") (pin "E28") (pinfunction "VSS_E28") (pintype "passive"))
      (node (ref "U2") (pin "E3") (pinfunction "VSS_E3") (pintype "passive"))
      (node (ref "U2") (pin "E30") (pinfunction "VSS_E30") (pintype "passive"))
      (node (ref "U2") (pin "E32") (pinfunction "VSS_E32") (pintype "passive"))
      (node (ref "U2") (pin "E34") (pinfunction "VSS_E34") (pintype "passive"))
      (node (ref "U2") (pin "E36") (pinfunction "VSS_E36") (pintype "passive"))
      (node (ref "U2") (pin "E38") (pinfunction "VSS_E38") (pintype "passive"))
      (node (ref "U2") (pin "E40") (pinfunction "VSS_E40") (pintype "passive"))
      (node (ref "U2") (pin "E42") (pinfunction "VSS_E42") (pintype "passive"))
      (node (ref "U2") (pin "E44") (pinfunction "VSS_E44") (pintype "passive"))
      (node (ref "U2") (pin "E5") (pinfunction "VSS_E5") (pintype "passive"))
      (node (ref "U2") (pin "E7") (pinfunction "VSS_E7") (pintype "passive"))
      (node (ref "U2") (pin "E9") (pinfunction "VSS_E9") (pintype "passive"))
      (node (ref "U2") (pin "F10") (pinfunction "VSS_F10") (pintype "passive"))
      (node (ref "U2") (pin "F12") (pinfunction "VSS_F12") (pintype "passive"))
      (node (ref "U2") (pin "F14") (pinfunction "VSS_F14") (pintype "passive"))
      (node (ref "U2") (pin "F16") (pinfunction "VSS_F16") (pintype "passive"))
      (node (ref "U2") (pin "F18") (pinfunction "VSS_F18") (pintype "passive"))
      (node (ref "U2") (pin "F2") (pinfunction "VSS_F2") (pintype "passive"))
      (node (ref "U2") (pin "F20") (pinfunction "VSS_F20") (pintype "passive"))
      (node (ref "U2") (pin "F22") (pinfunction "VSS_F22") (pintype "passive"))
      (node (ref "U2") (pin "F23") (pinfunction "VSS_F23") (pintype "passive"))
      (node (ref "U2") (pin "F25") (pinfunction "VSS_F25") (pintype "passive"))
      (node (ref "U2") (pin "F27") (pinfunction "VSS_F27") (pintype "passive"))
      (node (ref "U2") (pin "F29") (pinfunction "VSS_F29") (pintype "passive"))
      (node (ref "U2") (pin "F31") (pinfunction "VSS_F31") (pintype "passive"))
      (node (ref "U2") (pin "F33") (pinfunction "VSS_F33") (pintype "passive"))
      (node (ref "U2") (pin "F35") (pinfunction "VSS_F35") (pintype "passive"))
      (node (ref "U2") (pin "F37") (pinfunction "VSS_F37") (pintype "passive"))
      (node (ref "U2") (pin "F39") (pinfunction "VSS_F39") (pintype "passive"))
      (node (ref "U2") (pin "F4") (pinfunction "VSS_F4") (pintype "passive"))
      (node (ref "U2") (pin "F41") (pinfunction "VSS_F41") (pintype "passive"))
      (node (ref "U2") (pin "F43") (pinfunction "VSS_F43") (pintype "passive"))
      (node (ref "U2") (pin "F6") (pinfunction "VSS_F6") (pintype "passive"))
      (node (ref "U2") (pin "F8") (pinfunction "VSS_F8") (pintype "passive"))
      (node (ref "U2") (pin "G1") (pinfunction "VSS_G1") (pintype "passive"))
      (node (ref "U2") (pin "G11") (pinfunction "VSS_G11") (pintype "passive"))
      (node (ref "U2") (pin "G13") (pinfunction "VSS_G13") (pintype "passive"))
      (node (ref "U2") (pin "G15") (pinfunction "VSS_G15") (pintype "passive"))
      (node (ref "U2") (pin "G17") (pinfunction "VSS_G17") (pintype "passive"))
      (node (ref "U2") (pin "G19") (pinfunction "VSS_G19") (pintype "passive"))
      (node (ref "U2") (pin "G21") (pinfunction "VSS_G21") (pintype "passive"))
      (node (ref "U2") (pin "G24") (pinfunction "VSS_G24") (pintype "passive"))
      (node (ref "U2") (pin "G26") (pinfunction "VSS_G26") (pintype "passive"))
      (node (ref "U2") (pin "G28") (pinfunction "VSS_G28") (pintype "passive"))
      (node (ref "U2") (pin "G3") (pinfunction "VSS_G3") (pintype "passive"))
      (node (ref "U2") (pin "G30") (pinfunction "VSS_G30") (pintype "passive"))
      (node (ref "U2") (pin "G32") (pinfunction "VSS_G32") (pintype "passive"))
      (node (ref "U2") (pin "G34") (pinfunction "VSS_G34") (pintype "passive"))
      (node (ref "U2") (pin "G36") (pinfunction "VSS_G36") (pintype "passive"))
      (node (ref "U2") (pin "G38") (pinfunction "VSS_G38") (pintype "passive"))
      (node (ref "U2") (pin "G40") (pinfunction "VSS_G40") (pintype "passive"))
      (node (ref "U2") (pin "G42") (pinfunction "VSS_G42") (pintype "passive"))
      (node (ref "U2") (pin "G44") (pinfunction "VSS_G44") (pintype "passive"))
      (node (ref "U2") (pin "G5") (pinfunction "VSS_G5") (pintype "passive"))
      (node (ref "U2") (pin "G7") (pinfunction "VSS_G7") (pintype "passive"))
      (node (ref "U2") (pin "G9") (pinfunction "VSS_G9") (pintype "passive"))
      (node (ref "U2") (pin "H10") (pinfunction "VSS_H10") (pintype "passive"))
      (node (ref "U2") (pin "H12") (pinfunction "VSS_H12") (pintype "passive"))
      (node (ref "U2") (pin "H14") (pinfunction "VSS_H14") (pintype "passive"))
      (node (ref "U2") (pin "H16") (pinfunction "VSS_H16") (pintype "passive"))
      (node (ref "U2") (pin "H18") (pinfunction "VSS_H18") (pintype "passive"))
      (node (ref "U2") (pin "H2") (pinfunction "VSS_H2") (pintype "passive"))
      (node (ref "U2") (pin "H20") (pinfunction "VSS_H20") (pintype "passive"))
      (node (ref "U2") (pin "H22") (pinfunction "VSS_H22") (pintype "passive"))
      (node (ref "U2") (pin "H23") (pinfunction "VSS_H23") (pintype "passive"))
      (node (ref "U2") (pin "H25") (pinfunction "VSS_H25") (pintype "passive"))
      (node (ref "U2") (pin "H27") (pinfunction "VSS_H27") (pintype "passive"))
      (node (ref "U2") (pin "H29") (pinfunction "VSS_H29") (pintype "passive"))
      (node (ref "U2") (pin "H31") (pinfunction "VSS_H31") (pintype "passive"))
      (node (ref "U2") (pin "H33") (pinfunction "VSS_H33") (pintype "passive"))
      (node (ref "U2") (pin "H35") (pinfunction "VSS_H35") (pintype "passive"))
      (node (ref "U2") (pin "H37") (pinfunction "VSS_H37") (pintype "passive"))
      (node (ref "U2") (pin "H39") (pinfunction "VSS_H39") (pintype "passive"))
      (node (ref "U2") (pin "H4") (pinfunction "VSS_H4") (pintype "passive"))
      (node (ref "U2") (pin "H41") (pinfunction "VSS_H41") (pintype "passive"))
      (node (ref "U2") (pin "H43") (pinfunction "VSS_H43") (pintype "passive"))
      (node (ref "U2") (pin "H6") (pinfunction "VSS_H6") (pintype "passive"))
      (node (ref "U2") (pin "H8") (pinfunction "VSS_H8") (pintype "passive"))
      (node (ref "U2") (pin "J1") (pinfunction "VSS_J1") (pintype "passive"))
      (node (ref "U2") (pin "J11") (pinfunction "VSS_J11") (pintype "passive"))
      (node (ref "U2") (pin "J13") (pinfunction "VSS_J13") (pintype "passive"))
      (node (ref "U2") (pin "J15") (pinfunction "VSS_J15") (pintype "passive"))
      (node (ref "U2") (pin "J17") (pinfunction "VSS_J17") (pintype "passive"))
      (node (ref "U2") (pin "J19") (pinfunction "VSS_J19") (pintype "passive"))
      (node (ref "U2") (pin "J21") (pinfunction "VSS_J21") (pintype "passive"))
      (node (ref "U2") (pin "J24") (pinfunction "VSS_J24") (pintype "passive"))
      (node (ref "U2") (pin "J26") (pinfunction "VSS_J26") (pintype "passive"))
      (node (ref "U2") (pin "J28") (pinfunction "VSS_J28") (pintype "passive"))
      (node (ref "U2") (pin "J3") (pinfunction "VSS_J3") (pintype "passive"))
      (node (ref "U2") (pin "J30") (pinfunction "VSS_J30") (pintype "passive"))
      (node (ref "U2") (pin "J32") (pinfunction "VSS_J32") (pintype "passive"))
      (node (ref "U2") (pin "J34") (pinfunction "VSS_J34") (pintype "passive"))
      (node (ref "U2") (pin "J36") (pinfunction "VSS_J36") (pintype "passive"))
      (node (ref "U2") (pin "J38") (pinfunction "VSS_J38") (pintype "passive"))
      (node (ref "U2") (pin "J40") (pinfunction "VSS_J40") (pintype "passive"))
      (node (ref "U2") (pin "J42") (pinfunction "VSS_J42") (pintype "passive"))
      (node (ref "U2") (pin "J44") (pinfunction "VSS_J44") (pintype "passive"))
      (node (ref "U2") (pin "J5") (pinfunction "VSS_J5") (pintype "passive"))
      (node (ref "U2") (pin "J7") (pinfunction "VSS_J7") (pintype "passive"))
      (node (ref "U2") (pin "J9") (pinfunction "VSS_J9") (pintype "passive"))
      (node (ref "U2") (pin "K10") (pinfunction "VSS_K10") (pintype "passive"))
      (node (ref "U2") (pin "K12") (pinfunction "VSS_K12") (pintype "passive"))
      (node (ref "U2") (pin "K14") (pinfunction "VSS_K14") (pintype "passive"))
      (node (ref "U2") (pin "K16") (pinfunction "VSS_K16") (pintype "passive"))
      (node (ref "U2") (pin "K18") (pinfunction "VSS_K18") (pintype "passive"))
      (node (ref "U2") (pin "K2") (pinfunction "VSS_K2") (pintype "passive"))
      (node (ref "U2") (pin "K20") (pinfunction "VSS_K20") (pintype "passive"))
      (node (ref "U2") (pin "K22") (pinfunction "VSS_K22") (pintype "passive"))
      (node (ref "U2") (pin "K23") (pinfunction "VSS_K23") (pintype "passive"))
      (node (ref "U2") (pin "K25") (pinfunction "VSS_K25") (pintype "passive"))
      (node (ref "U2") (pin "K27") (pinfunction "VSS_K27") (pintype "passive"))
      (node (ref "U2") (pin "K29") (pinfunction "VSS_K29") (pintype "passive"))
      (node (ref "U2") (pin "K31") (pinfunction "VSS_K31") (pintype "passive"))
      (node (ref "U2") (pin "K33") (pinfunction "VSS_K33") (pintype "passive"))
      (node (ref "U2") (pin "K35") (pinfunction "VSS_K35") (pintype "passive"))
      (node (ref "U2") (pin "K37") (pinfunction "VSS_K37") (pintype "passive"))
      (node (ref "U2") (pin "K39") (pinfunction "VSS_K39") (pintype "passive"))
      (node (ref "U2") (pin "K4") (pinfunction "VSS_K4") (pintype "passive"))
      (node (ref "U2") (pin "K41") (pinfunction "VSS_K41") (pintype "passive"))
      (node (ref "U2") (pin "K43") (pinfunction "VSS_K43") (pintype "passive"))
      (node (ref "U2") (pin "K6") (pinfunction "VSS_K6") (pintype "passive"))
      (node (ref "U2") (pin "K8") (pinfunction "VSS_K8") (pintype "passive"))
      (node (ref "U2") (pin "L1") (pinfunction "VSS_L1") (pintype "passive"))
      (node (ref "U2") (pin "L11") (pinfunction "VSS_L11") (pintype "passive"))
      (node (ref "U2") (pin "L13") (pinfunction "VSS_L13") (pintype "passive"))
      (node (ref "U2") (pin "L15") (pinfunction "VSS_L15") (pintype "passive"))
      (node (ref "U2") (pin "L17") (pinfunction "VSS_L17") (pintype "passive"))
      (node (ref "U2") (pin "L19") (pinfunction "VSS_L19") (pintype "passive"))
      (node (ref "U2") (pin "L21") (pinfunction "VSS_L21") (pintype "passive"))
      (node (ref "U2") (pin "L24") (pinfunction "VSS_L24") (pintype "passive"))
      (node (ref "U2") (pin "L26") (pinfunction "VSS_L26") (pintype "passive"))
      (node (ref "U2") (pin "L28") (pinfunction "VSS_L28") (pintype "passive"))
      (node (ref "U2") (pin "L3") (pinfunction "VSS_L3") (pintype "passive"))
      (node (ref "U2") (pin "L30") (pinfunction "VSS_L30") (pintype "passive"))
      (node (ref "U2") (pin "L32") (pinfunction "VSS_L32") (pintype "passive"))
      (node (ref "U2") (pin "L34") (pinfunction "VSS_L34") (pintype "passive"))
      (node (ref "U2") (pin "L36") (pinfunction "VSS_L36") (pintype "passive"))
      (node (ref "U2") (pin "L38") (pinfunction "VSS_L38") (pintype "passive"))
      (node (ref "U2") (pin "L40") (pinfunction "VSS_L40") (pintype "passive"))
      (node (ref "U2") (pin "L42") (pinfunction "VSS_L42") (pintype "passive"))
      (node (ref "U2") (pin "L44") (pinfunction "VSS_L44") (pintype "passive"))
      (node (ref "U2") (pin "L5") (pinfunction "VSS_L5") (pintype "passive"))
      (node (ref "U2") (pin "L7") (pinfunction "VSS_L7") (pintype "passive"))
      (node (ref "U2") (pin "L9") (pinfunction "VSS_L9") (pintype "passive"))
      (node (ref "U2") (pin "M10") (pinfunction "VSS_M10") (pintype "passive"))
      (node (ref "U2") (pin "M12") (pinfunction "VSS_M12") (pintype "passive"))
      (node (ref "U2") (pin "M14") (pinfunction "VSS_M14") (pintype "passive"))
      (node (ref "U2") (pin "M16") (pinfunction "VSS_M16") (pintype "passive"))
      (node (ref "U2") (pin "M18") (pinfunction "VSS_M18") (pintype "passive"))
      (node (ref "U2") (pin "M2") (pinfunction "VSS_M2") (pintype "passive"))
      (node (ref "U2") (pin "M20") (pinfunction "VSS_M20") (pintype "passive"))
      (node (ref "U2") (pin "M22") (pinfunction "VSS_M22") (pintype "passive"))
      (node (ref "U2") (pin "M23") (pinfunction "VSS_M23") (pintype "passive"))
      (node (ref "U2") (pin "M25") (pinfunction "VSS_M25") (pintype "passive"))
      (node (ref "U2") (pin "M27") (pinfunction "VSS_M27") (pintype "passive"))
      (node (ref "U2") (pin "M29") (pinfunction "VSS_M29") (pintype "passive"))
      (node (ref "U2") (pin "M31") (pinfunction "VSS_M31") (pintype "passive"))
      (node (ref "U2") (pin "M33") (pinfunction "VSS_M33") (pintype "passive"))
      (node (ref "U2") (pin "M35") (pinfunction "VSS_M35") (pintype "passive"))
      (node (ref "U2") (pin "M37") (pinfunction "VSS_M37") (pintype "passive"))
      (node (ref "U2") (pin "M39") (pinfunction "VSS_M39") (pintype "passive"))
      (node (ref "U2") (pin "M4") (pinfunction "VSS_M4") (pintype "passive"))
      (node (ref "U2") (pin "M41") (pinfunction "VSS_M41") (pintype "passive"))
      (node (ref "U2") (pin "M43") (pinfunction "VSS_M43") (pintype "passive"))
      (node (ref "U2") (pin "M6") (pinfunction "VSS_M6") (pintype "passive"))
      (node (ref "U2") (pin "M8") (pinfunction "VSS_M8") (pintype "passive"))
      (node (ref "U2") (pin "N1") (pinfunction "VSS_N1") (pintype "passive"))
      (node (ref "U2") (pin "N11") (pinfunction "VSS_N11") (pintype "passive"))
      (node (ref "U2") (pin "N13") (pinfunction "VSS_N13") (pintype "passive"))
      (node (ref "U2") (pin "N15") (pinfunction "VSS_N15") (pintype "passive"))
      (node (ref "U2") (pin "N17") (pinfunction "VSS_N17") (pintype "passive"))
      (node (ref "U2") (pin "N19") (pinfunction "VSS_N19") (pintype "passive"))
      (node (ref "U2") (pin "N21") (pinfunction "VSS_N21") (pintype "passive"))
      (node (ref "U2") (pin "N24") (pinfunction "VSS_N24") (pintype "passive"))
      (node (ref "U2") (pin "N26") (pinfunction "VSS_N26") (pintype "passive"))
      (node (ref "U2") (pin "N28") (pinfunction "VSS_N28") (pintype "passive"))
      (node (ref "U2") (pin "N3") (pinfunction "VSS_N3") (pintype "passive"))
      (node (ref "U2") (pin "N30") (pinfunction "VSS_N30") (pintype "passive"))
      (node (ref "U2") (pin "N32") (pinfunction "VSS_N32") (pintype "passive"))
      (node (ref "U2") (pin "N34") (pinfunction "VSS_N34") (pintype "passive"))
      (node (ref "U2") (pin "N36") (pinfunction "VSS_N36") (pintype "passive"))
      (node (ref "U2") (pin "N38") (pinfunction "VSS_N38") (pintype "passive"))
      (node (ref "U2") (pin "N40") (pinfunction "VSS_N40") (pintype "passive"))
      (node (ref "U2") (pin "N42") (pinfunction "VSS_N42") (pintype "passive"))
      (node (ref "U2") (pin "N44") (pinfunction "VSS_N44") (pintype "passive"))
      (node (ref "U2") (pin "N5") (pinfunction "VSS_N5") (pintype "passive"))
      (node (ref "U2") (pin "N7") (pinfunction "VSS_N7") (pintype "passive"))
      (node (ref "U2") (pin "N9") (pinfunction "VSS_N9") (pintype "passive"))
      (node (ref "U2") (pin "P10") (pinfunction "VSS_P10") (pintype "passive"))
      (node (ref "U2") (pin "P12") (pinfunction "VSS_P12") (pintype "passive"))
      (node (ref "U2") (pin "P14") (pinfunction "VSS_P14") (pintype "passive"))
      (node (ref "U2") (pin "P16") (pinfunction "VSS_P16") (pintype "passive"))
      (node (ref "U2") (pin "P18") (pinfunction "VSS_P18") (pintype "passive"))
      (node (ref "U2") (pin "P2") (pinfunction "VSS_P2") (pintype "passive"))
      (node (ref "U2") (pin "P20") (pinfunction "VSS_P20") (pintype "passive"))
      (node (ref "U2") (pin "P22") (pinfunction "VSS_P22") (pintype "passive"))
      (node (ref "U2") (pin "P23") (pinfunction "VSS_P23") (pintype "passive"))
      (node (ref "U2") (pin "P25") (pinfunction "VSS_P25") (pintype "passive"))
      (node (ref "U2") (pin "P27") (pinfunction "VSS_P27") (pintype "passive"))
      (node (ref "U2") (pin "P29") (pinfunction "VSS_P29") (pintype "passive"))
      (node (ref "U2") (pin "P31") (pinfunction "VSS_P31") (pintype "passive"))
      (node (ref "U2") (pin "P33") (pinfunction "VSS_P33") (pintype "passive"))
      (node (ref "U2") (pin "P35") (pinfunction "VSS_P35") (pintype "passive"))
      (node (ref "U2") (pin "P37") (pinfunction "VSS_P37") (pintype "passive"))
      (node (ref "U2") (pin "P39") (pinfunction "VSS_P39") (pintype "passive"))
      (node (ref "U2") (pin "P4") (pinfunction "VSS_P4") (pintype "passive"))
      (node (ref "U2") (pin "P41") (pinfunction "VSS_P41") (pintype "passive"))
      (node (ref "U2") (pin "P43") (pinfunction "VSS_P43") (pintype "passive"))
      (node (ref "U2") (pin "P6") (pinfunction "VSS_P6") (pintype "passive"))
      (node (ref "U2") (pin "P8") (pinfunction "VSS_P8") (pintype "passive"))
      (node (ref "U2") (pin "R1") (pinfunction "VSS_R1") (pintype "passive"))
      (node (ref "U2") (pin "R11") (pinfunction "VSS_R11") (pintype "passive"))
      (node (ref "U2") (pin "R13") (pinfunction "VSS_R13") (pintype "passive"))
      (node (ref "U2") (pin "R15") (pinfunction "VSS_R15") (pintype "passive"))
      (node (ref "U2") (pin "R17") (pinfunction "VSS_R17") (pintype "passive"))
      (node (ref "U2") (pin "R19") (pinfunction "VSS_R19") (pintype "passive"))
      (node (ref "U2") (pin "R21") (pinfunction "VSS_R21") (pintype "passive"))
      (node (ref "U2") (pin "R24") (pinfunction "VSS_R24") (pintype "passive"))
      (node (ref "U2") (pin "R26") (pinfunction "VSS_R26") (pintype "passive"))
      (node (ref "U2") (pin "R28") (pinfunction "VSS_R28") (pintype "passive"))
      (node (ref "U2") (pin "R3") (pinfunction "VSS_R3") (pintype "passive"))
      (node (ref "U2") (pin "R30") (pinfunction "VSS_R30") (pintype "passive"))
      (node (ref "U2") (pin "R32") (pinfunction "VSS_R32") (pintype "passive"))
      (node (ref "U2") (pin "R34") (pinfunction "VSS_R34") (pintype "passive"))
      (node (ref "U2") (pin "R36") (pinfunction "VSS_R36") (pintype "passive"))
      (node (ref "U2") (pin "R38") (pinfunction "VSS_R38") (pintype "passive"))
      (node (ref "U2") (pin "R40") (pinfunction "VSS_R40") (pintype "passive"))
      (node (ref "U2") (pin "R42") (pinfunction "VSS_R42") (pintype "passive"))
      (node (ref "U2") (pin "R44") (pinfunction "VSS_R44") (pintype "passive"))
      (node (ref "U2") (pin "R5") (pinfunction "VSS_R5") (pintype "passive"))
      (node (ref "U2") (pin "R7") (pinfunction "VSS_R7") (pintype "passive"))
      (node (ref "U2") (pin "R9") (pinfunction "VSS_R9") (pintype "passive"))
      (node (ref "U2") (pin "T10") (pinfunction "VSS_T10") (pintype "passive"))
      (node (ref "U2") (pin "T12") (pinfunction "VSS_T12") (pintype "passive"))
      (node (ref "U2") (pin "T14") (pinfunction "VSS_T14") (pintype "passive"))
      (node (ref "U2") (pin "T16") (pinfunction "VSS_T16") (pintype "passive"))
      (node (ref "U2") (pin "T18") (pinfunction "VSS_T18") (pintype "passive"))
      (node (ref "U2") (pin "T2") (pinfunction "VSS_T2") (pintype "passive"))
      (node (ref "U2") (pin "T20") (pinfunction "VSS_T20") (pintype "passive"))
      (node (ref "U2") (pin "T22") (pinfunction "VSS_T22") (pintype "passive"))
      (node (ref "U2") (pin "T23") (pinfunction "VSS_T23") (pintype "passive"))
      (node (ref "U2") (pin "T25") (pinfunction "VSS_T25") (pintype "passive"))
      (node (ref "U2") (pin "T27") (pinfunction "VSS_T27") (pintype "passive"))
      (node (ref "U2") (pin "T29") (pinfunction "VSS_T29") (pintype "passive"))
      (node (ref "U2") (pin "T31") (pinfunction "VSS_T31") (pintype "passive"))
      (node (ref "U2") (pin "T33") (pinfunction "VSS_T33") (pintype "passive"))
      (node (ref "U2") (pin "T35") (pinfunction "VSS_T35") (pintype "passive"))
      (node (ref "U2") (pin "T37") (pinfunction "VSS_T37") (pintype "passive"))
      (node (ref "U2") (pin "T39") (pinfunction "VSS_T39") (pintype "passive"))
      (node (ref "U2") (pin "T4") (pinfunction "VSS_T4") (pintype "passive"))
      (node (ref "U2") (pin "T41") (pinfunction "VSS_T41") (pintype "passive"))
      (node (ref "U2") (pin "T43") (pinfunction "VSS_T43") (pintype "passive"))
      (node (ref "U2") (pin "T6") (pinfunction "VSS_T6") (pintype "passive"))
      (node (ref "U2") (pin "T8") (pinfunction "VSS_T8") (pintype "passive"))
      (node (ref "U2") (pin "U1") (pinfunction "VSS_U1") (pintype "passive"))
      (node (ref "U2") (pin "U11") (pinfunction "VSS_U11") (pintype "passive"))
      (node (ref "U2") (pin "U13") (pinfunction "VSS_U13") (pintype "passive"))
      (node (ref "U2") (pin "U15") (pinfunction "VSS_U15") (pintype "passive"))
      (node (ref "U2") (pin "U17") (pinfunction "VSS_U17") (pintype "passive"))
      (node (ref "U2") (pin "U19") (pinfunction "VSS_U19") (pintype "passive"))
      (node (ref "U2") (pin "U21") (pinfunction "VSS_U21") (pintype "passive"))
      (node (ref "U2") (pin "U24") (pinfunction "VSS_U24") (pintype "passive"))
      (node (ref "U2") (pin "U26") (pinfunction "VSS_U26") (pintype "passive"))
      (node (ref "U2") (pin "U28") (pinfunction "VSS_U28") (pintype "passive"))
      (node (ref "U2") (pin "U3") (pinfunction "VSS_U3") (pintype "passive"))
      (node (ref "U2") (pin "U30") (pinfunction "VSS_U30") (pintype "passive"))
      (node (ref "U2") (pin "U32") (pinfunction "VSS_U32") (pintype "passive"))
      (node (ref "U2") (pin "U34") (pinfunction "VSS_U34") (pintype "passive"))
      (node (ref "U2") (pin "U36") (pinfunction "VSS_U36") (pintype "passive"))
      (node (ref "U2") (pin "U38") (pinfunction "VSS_U38") (pintype "passive"))
      (node (ref "U2") (pin "U40") (pinfunction "VSS_U40") (pintype "passive"))
      (node (ref "U2") (pin "U42") (pinfunction "VSS_U42") (pintype "passive"))
      (node (ref "U2") (pin "U44") (pinfunction "VSS_U44") (pintype "passive"))
      (node (ref "U2") (pin "U5") (pinfunction "VSS_U5") (pintype "passive"))
      (node (ref "U2") (pin "U7") (pinfunction "VSS_U7") (pintype "passive"))
      (node (ref "U2") (pin "U9") (pinfunction "VSS_U9") (pintype "passive"))
      (node (ref "U2") (pin "V10") (pinfunction "VSS_V10") (pintype "passive"))
      (node (ref "U2") (pin "V12") (pinfunction "VSS_V12") (pintype "passive"))
      (node (ref "U2") (pin "V14") (pinfunction "VSS_V14") (pintype "passive"))
      (node (ref "U2") (pin "V16") (pinfunction "VSS_V16") (pintype "passive"))
      (node (ref "U2") (pin "V18") (pinfunction "VSS_V18") (pintype "passive"))
      (node (ref "U2") (pin "V2") (pinfunction "VSS_V2") (pintype "passive"))
      (node (ref "U2") (pin "V20") (pinfunction "VSS_V20") (pintype "passive"))
      (node (ref "U2") (pin "V22") (pinfunction "VSS_V22") (pintype "passive"))
      (node (ref "U2") (pin "V23") (pinfunction "VSS_V23") (pintype "passive"))
      (node (ref "U2") (pin "V25") (pinfunction "VSS_V25") (pintype "passive"))
      (node (ref "U2") (pin "V27") (pinfunction "VSS_V27") (pintype "passive"))
      (node (ref "U2") (pin "V29") (pinfunction "VSS_V29") (pintype "passive"))
      (node (ref "U2") (pin "V31") (pinfunction "VSS_V31") (pintype "passive"))
      (node (ref "U2") (pin "V33") (pinfunction "VSS_V33") (pintype "passive"))
      (node (ref "U2") (pin "V35") (pinfunction "VSS_V35") (pintype "passive"))
      (node (ref "U2") (pin "V37") (pinfunction "VSS_V37") (pintype "passive"))
      (node (ref "U2") (pin "V39") (pinfunction "VSS_V39") (pintype "passive"))
      (node (ref "U2") (pin "V4") (pinfunction "VSS_V4") (pintype "passive"))
      (node (ref "U2") (pin "V41") (pinfunction "VSS_V41") (pintype "passive"))
      (node (ref "U2") (pin "V43") (pinfunction "VSS_V43") (pintype "passive"))
      (node (ref "U2") (pin "V6") (pinfunction "VSS_V6") (pintype "passive"))
      (node (ref "U2") (pin "V8") (pinfunction "VSS_V8") (pintype "passive"))
      (node (ref "U2") (pin "W1") (pinfunction "VSS_W1") (pintype "passive"))
      (node (ref "U2") (pin "W11") (pinfunction "VSS_W11") (pintype "passive"))
      (node (ref "U2") (pin "W13") (pinfunction "VSS_W13") (pintype "passive"))
      (node (ref "U2") (pin "W15") (pinfunction "VSS_W15") (pintype "passive"))
      (node (ref "U2") (pin "W17") (pinfunction "VSS_W17") (pintype "passive"))
      (node (ref "U2") (pin "W19") (pinfunction "VSS_W19") (pintype "passive"))
      (node (ref "U2") (pin "W21") (pinfunction "VSS_W21") (pintype "passive"))
      (node (ref "U2") (pin "W24") (pinfunction "VSS_W24") (pintype "passive"))
      (node (ref "U2") (pin "W26") (pinfunction "VSS_W26") (pintype "passive"))
      (node (ref "U2") (pin "W28") (pinfunction "VSS_W28") (pintype "passive"))
      (node (ref "U2") (pin "W3") (pinfunction "VSS_W3") (pintype "passive"))
      (node (ref "U2") (pin "W30") (pinfunction "VSS_W30") (pintype "passive"))
      (node (ref "U2") (pin "W32") (pinfunction "VSS_W32") (pintype "passive"))
      (node (ref "U2") (pin "W34") (pinfunction "VSS_W34") (pintype "passive"))
      (node (ref "U2") (pin "W36") (pinfunction "VSS_W36") (pintype "passive"))
      (node (ref "U2") (pin "W38") (pinfunction "VSS_W38") (pintype "passive"))
      (node (ref "U2") (pin "W40") (pinfunction "VSS_W40") (pintype "passive"))
      (node (ref "U2") (pin "W42") (pinfunction "VSS_W42") (pintype "passive"))
      (node (ref "U2") (pin "W44") (pinfunction "VSS_W44") (pintype "passive"))
      (node (ref "U2") (pin "W5") (pinfunction "VSS_W5") (pintype "passive"))
      (node (ref "U2") (pin "W7") (pinfunction "VSS_W7") (pintype "passive"))
      (node (ref "U2") (pin "W9") (pinfunction "VSS_W9") (pintype "passive"))
      (node (ref "U2") (pin "Y10") (pinfunction "VSS_Y10") (pintype "passive"))
      (node (ref "U2") (pin "Y12") (pinfunction "VSS_Y12") (pintype "passive"))
      (node (ref "U2") (pin "Y14") (pinfunction "VSS_Y14") (pintype "passive"))
      (node (ref "U2") (pin "Y16") (pinfunction "VSS_Y16") (pintype "passive"))
      (node (ref "U2") (pin "Y18") (pinfunction "VSS_Y18") (pintype "passive"))
      (node (ref "U2") (pin "Y2") (pinfunction "VSS_Y2") (pintype "passive"))
      (node (ref "U2") (pin "Y20") (pinfunction "VSS_Y20") (pintype "passive"))
      (node (ref "U2") (pin "Y22") (pinfunction "VSS_Y22") (pintype "passive"))
      (node (ref "U2") (pin "Y23") (pinfunction "VSS_Y23") (pintype "passive"))
      (node (ref "U2") (pin "Y25") (pinfunction "VSS_Y25") (pintype "passive"))
      (node (ref "U2") (pin "Y27") (pinfunction "VSS_Y27") (pintype "passive"))
      (node (ref "U2") (pin "Y29") (pinfunction "VSS_Y29") (pintype "passive"))
      (node (ref "U2") (pin "Y31") (pinfunction "VSS_Y31") (pintype "passive"))
      (node (ref "U2") (pin "Y33") (pinfunction "VSS_Y33") (pintype "passive"))
      (node (ref "U2") (pin "Y35") (pinfunction "VSS_Y35") (pintype "passive"))
      (node (ref "U2") (pin "Y37") (pinfunction "VSS_Y37") (pintype "passive"))
      (node (ref "U2") (pin "Y39") (pinfunction "VSS_Y39") (pintype "passive"))
      (node (ref "U2") (pin "Y4") (pinfunction "VSS_Y4") (pintype "passive"))
      (node (ref "U2") (pin "Y41") (pinfunction "VSS_Y41") (pintype "passive"))
      (node (ref "U2") (pin "Y43") (pinfunction "VSS_Y43") (pintype "passive"))
      (node (ref "U2") (pin "Y6") (pinfunction "VSS_Y6") (pintype "passive"))
      (node (ref "U2") (pin "Y8") (pinfunction "VSS_Y8") (pintype "passive"))
    )
    (net (code "3") (name "Net-(U2A-VDD_D2-PadE27)") (class "Default")
      (node (ref "U2") (pin "AY27") (pinfunction "VDD_D3_AY27") (pintype "passive"))
      (node (ref "U2") (pin "E27") (pinfunction "VDD_D2_E27") (pintype "passive"))
    )
    (net (code "4") (name "Net-(U2A-VDD_D3-PadAC24)") (class "Default")
      (node (ref "U2") (pin "AC24") (pinfunction "VDD_D3_AC24") (pintype "passive"))
      (node (ref "U2") (pin "BD2") (pinfunction "VDD_D4_BD2") (pintype "passive"))
    )
    (net (code "5") (name "Net-(U2A-VDD_D3-PadAC26)") (class "Default")
      (node (ref "U2") (pin "AC26") (pinfunction "VDD_D3_AC26") (pintype "passive"))
      (node (ref "U2") (pin "BD4") (pinfunction "VDD_D4_BD4") (pintype "passive"))
    )
    (net (code "6") (name "Net-(U2A-VDD_D3-PadAC28)") (class "Default")
      (node (ref "U2") (pin "AC28") (pinfunction "VDD_D3_AC28") (pintype "passive"))
      (node (ref "U2") (pin "BD6") (pinfunction "VDD_D4_BD6") (pintype "passive"))
    )
    (net (code "7") (name "Net-(U2A-VDD_D3-PadAC30)") (class "Default")
      (node (ref "U2") (pin "AC30") (pinfunction "VDD_D3_AC30") (pintype "passive"))
      (node (ref "U2") (pin "BD22") (pinfunction "VDD_D4_BD22") (pintype "passive"))
    )
    (net (code "8") (name "Net-(U2A-VDD_D3-PadAC34)") (class "Default")
      (node (ref "U2") (pin "AC34") (pinfunction "VDD_D3_AC34") (pintype "passive"))
      (node (ref "U2") (pin "BC1") (pinfunction "VDD_D4_BC1") (pintype "passive"))
    )
    (net (code "9") (name "Net-(U2A-VDD_D3-PadAC36)") (class "Default")
      (node (ref "U2") (pin "AC36") (pinfunction "VDD_D3_AC36") (pintype "passive"))
      (node (ref "U2") (pin "BC3") (pinfunction "VDD_D4_BC3") (pintype "passive"))
    )
    (net (code "10") (name "Net-(U2A-VDD_D3-PadAC38)") (class "Default")
      (node (ref "U2") (pin "AC38") (pinfunction "VDD_D3_AC38") (pintype "passive"))
      (node (ref "U2") (pin "BC5") (pinfunction "VDD_D4_BC5") (pintype "passive"))
    )
    (net (code "11") (name "Net-(U2A-VDD_D3-PadAC40)") (class "Default")
      (node (ref "U2") (pin "AC40") (pinfunction "VDD_D3_AC40") (pintype "passive"))
      (node (ref "U2") (pin "BC7") (pinfunction "VDD_D4_BC7") (pintype "passive"))
    )
    (net (code "12") (name "Net-(U2A-VDD_D3-PadAC44)") (class "Default")
      (node (ref "U2") (pin "AC44") (pinfunction "VDD_D3_AC44") (pintype "passive"))
      (node (ref "U2") (pin "BB2") (pinfunction "VDD_D4_BB2") (pintype "passive"))
    )
    (net (code "13") (name "Net-(U2A-VDD_D3-PadAD23)") (class "Default")
      (node (ref "U2") (pin "AD23") (pinfunction "VDD_D3_AD23") (pintype "passive"))
      (node (ref "U2") (pin "BB6") (pinfunction "VDD_D4_BB6") (pintype "passive"))
    )
    (net (code "14") (name "Net-(U2A-VDD_D3-PadAD25)") (class "Default")
      (node (ref "U2") (pin "AD25") (pinfunction "VDD_D3_AD25") (pintype "passive"))
      (node (ref "U2") (pin "BB8") (pinfunction "VDD_D4_BB8") (pintype "passive"))
    )
    (net (code "15") (name "Net-(U2A-VDD_D3-PadAD27)") (class "Default")
      (node (ref "U2") (pin "AD27") (pinfunction "VDD_D3_AD27") (pintype "passive"))
      (node (ref "U2") (pin "BB22") (pinfunction "VDD_D4_BB22") (pintype "passive"))
    )
    (net (code "16") (name "Net-(U2A-VDD_D3-PadAD31)") (class "Default")
      (node (ref "U2") (pin "AD31") (pinfunction "VDD_D3_AD31") (pintype "passive"))
      (node (ref "U2") (pin "BA1") (pinfunction "VDD_D4_BA1") (pintype "passive"))
    )
    (net (code "17") (name "Net-(U2A-VDD_D3-PadAD33)") (class "Default")
      (node (ref "U2") (pin "AD33") (pinfunction "VDD_D3_AD33") (pintype "passive"))
      (node (ref "U2") (pin "BA3") (pinfunction "VDD_D4_BA3") (pintype "passive"))
    )
    (net (code "18") (name "Net-(U2A-VDD_D3-PadAD35)") (class "Default")
      (node (ref "U2") (pin "AD35") (pinfunction "VDD_D3_AD35") (pintype "passive"))
      (node (ref "U2") (pin "BA5") (pinfunction "VDD_D4_BA5") (pintype "passive"))
    )
    (net (code "19") (name "Net-(U2A-VDD_D3-PadAD37)") (class "Default")
      (node (ref "U2") (pin "AD37") (pinfunction "VDD_D3_AD37") (pintype "passive"))
      (node (ref "U2") (pin "BA7") (pinfunction "VDD_D4_BA7") (pintype "passive"))
    )
    (net (code "20") (name "Net-(U2A-VDD_D3-PadAD39)") (class "Default")
      (node (ref "U2") (pin "AD39") (pinfunction "VDD_D3_AD39") (pintype "passive"))
      (node (ref "U2") (pin "BA9") (pinfunction "VDD_D4_BA9") (pintype "passive"))
    )
    (net (code "21") (name "Net-(U2A-VDD_D3-PadAD41)") (class "Default")
      (node (ref "U2") (pin "AD41") (pinfunction "VDD_D3_AD41") (pintype "passive"))
      (node (ref "U2") (pin "BA11") (pinfunction "VDD_D4_BA11") (pintype "passive"))
    )
    (net (code "22") (name "Net-(U2A-VDD_D3-PadAD43)") (class "Default")
      (node (ref "U2") (pin "AD43") (pinfunction "VDD_D3_AD43") (pintype "passive"))
      (node (ref "U2") (pin "BA13") (pinfunction "VDD_D4_BA13") (pintype "passive"))
    )
    (net (code "23") (name "Net-(U2A-VDD_D3-PadAE24)") (class "Default")
      (node (ref "U2") (pin "AE24") (pinfunction "VDD_D3_AE24") (pintype "passive"))
      (node (ref "U2") (pin "BA17") (pinfunction "VDD_D4_BA17") (pintype "passive"))
    )
    (net (code "24") (name "Net-(U2A-VDD_D3-PadAE26)") (class "Default")
      (node (ref "U2") (pin "AE26") (pinfunction "VDD_D3_AE26") (pintype "passive"))
      (node (ref "U2") (pin "BA19") (pinfunction "VDD_D4_BA19") (pintype "passive"))
    )
    (net (code "25") (name "Net-(U2A-VDD_D3-PadAE28)") (class "Default")
      (node (ref "U2") (pin "AE28") (pinfunction "VDD_D3_AE28") (pintype "passive"))
      (node (ref "U2") (pin "BA21") (pinfunction "VDD_D4_BA21") (pintype "passive"))
    )
    (net (code "26") (name "Net-(U2A-VDD_D3-PadAE32)") (class "Default")
      (node (ref "U2") (pin "AE32") (pinfunction "VDD_D3_AE32") (pintype "passive"))
      (node (ref "U2") (pin "AY2") (pinfunction "VDD_D4_AY2") (pintype "passive"))
    )
    (net (code "27") (name "Net-(U2A-VDD_D3-PadAE34)") (class "Default")
      (node (ref "U2") (pin "AE34") (pinfunction "VDD_D3_AE34") (pintype "passive"))
      (node (ref "U2") (pin "AY4") (pinfunction "VDD_D4_AY4") (pintype "passive"))
    )
    (net (code "28") (name "Net-(U2A-VDD_D3-PadAE36)") (class "Default")
      (node (ref "U2") (pin "AE36") (pinfunction "VDD_D3_AE36") (pintype "passive"))
      (node (ref "U2") (pin "AY6") (pinfunction "VDD_D4_AY6") (pintype "passive"))
    )
    (net (code "29") (name "Net-(U2A-VDD_D3-PadAE38)") (class "Default")
      (node (ref "U2") (pin "AE38") (pinfunction "VDD_D3_AE38") (pintype "passive"))
      (node (ref "U2") (pin "AY8") (pinfunction "VDD_D4_AY8") (pintype "passive"))
    )
    (net (code "30") (name "Net-(U2A-VDD_D3-PadAE40)") (class "Default")
      (node (ref "U2") (pin "AE40") (pinfunction "VDD_D3_AE40") (pintype "passive"))
      (node (ref "U2") (pin "AY10") (pinfunction "VDD_D4_AY10") (pintype "passive"))
    )
    (net (code "31") (name "Net-(U2A-VDD_D3-PadAE42)") (class "Default")
      (node (ref "U2") (pin "AE42") (pinfunction "VDD_D3_AE42") (pintype "passive"))
      (node (ref "U2") (pin "AY12") (pinfunction "VDD_D4_AY12") (pintype "passive"))
    )
    (net (code "32") (name "Net-(U2A-VDD_D3-PadAE44)") (class "Default")
      (node (ref "U2") (pin "AE44") (pinfunction "VDD_D3_AE44") (pintype "passive"))
      (node (ref "U2") (pin "AY14") (pinfunction "VDD_D4_AY14") (pintype "passive"))
    )
    (net (code "33") (name "Net-(U2A-VDD_D3-PadAF23)") (class "Default")
      (node (ref "U2") (pin "AF23") (pinfunction "VDD_D3_AF23") (pintype "passive"))
      (node (ref "U2") (pin "AY18") (pinfunction "VDD_D4_AY18") (pintype "passive"))
    )
    (net (code "34") (name "Net-(U2A-VDD_D3-PadAF25)") (class "Default")
      (node (ref "U2") (pin "AF25") (pinfunction "VDD_D3_AF25") (pintype "passive"))
      (node (ref "U2") (pin "AY20") (pinfunction "VDD_D4_AY20") (pintype "passive"))
    )
    (net (code "35") (name "Net-(U2A-VDD_D3-PadAF27)") (class "Default")
      (node (ref "U2") (pin "AF27") (pinfunction "VDD_D3_AF27") (pintype "passive"))
      (node (ref "U2") (pin "AY22") (pinfunction "VDD_D4_AY22") (pintype "passive"))
    )
    (net (code "36") (name "Net-(U2A-VDD_D3-PadAF31)") (class "Default")
      (node (ref "U2") (pin "AF31") (pinfunction "VDD_D3_AF31") (pintype "passive"))
      (node (ref "U2") (pin "AW1") (pinfunction "VDD_D4_AW1") (pintype "passive"))
    )
    (net (code "37") (name "Net-(U2A-VDD_D3-PadAF33)") (class "Default")
      (node (ref "U2") (pin "AF33") (pinfunction "VDD_D3_AF33") (pintype "passive"))
      (node (ref "U2") (pin "AW3") (pinfunction "VDD_D4_AW3") (pintype "passive"))
    )
    (net (code "38") (name "Net-(U2A-VDD_D3-PadAF35)") (class "Default")
      (node (ref "U2") (pin "AF35") (pinfunction "VDD_D3_AF35") (pintype "passive"))
      (node (ref "U2") (pin "AW5") (pinfunction "VDD_D4_AW5") (pintype "passive"))
    )
    (net (code "39") (name "Net-(U2A-VDD_D3-PadAF37)") (class "Default")
      (node (ref "U2") (pin "AF37") (pinfunction "VDD_D3_AF37") (pintype "passive"))
      (node (ref "U2") (pin "AW7") (pinfunction "VDD_D4_AW7") (pintype "passive"))
    )
    (net (code "40") (name "Net-(U2A-VDD_D3-PadAF39)") (class "Default")
      (node (ref "U2") (pin "AF39") (pinfunction "VDD_D3_AF39") (pintype "passive"))
      (node (ref "U2") (pin "AW9") (pinfunction "VDD_D4_AW9") (pintype "passive"))
    )
    (net (code "41") (name "Net-(U2A-VDD_D3-PadAF41)") (class "Default")
      (node (ref "U2") (pin "AF41") (pinfunction "VDD_D3_AF41") (pintype "passive"))
      (node (ref "U2") (pin "AW11") (pinfunction "VDD_D4_AW11") (pintype "passive"))
    )
    (net (code "42") (name "Net-(U2A-VDD_D3-PadAF43)") (class "Default")
      (node (ref "U2") (pin "AF43") (pinfunction "VDD_D3_AF43") (pintype "passive"))
      (node (ref "U2") (pin "AW13") (pinfunction "VDD_D4_AW13") (pintype "passive"))
    )
    (net (code "43") (name "Net-(U2A-VDD_D3-PadAG24)") (class "Default")
      (node (ref "U2") (pin "AG24") (pinfunction "VDD_D3_AG24") (pintype "passive"))
      (node (ref "U2") (pin "AW17") (pinfunction "VDD_D4_AW17") (pintype "passive"))
    )
    (net (code "44") (name "Net-(U2A-VDD_D3-PadAG26)") (class "Default")
      (node (ref "U2") (pin "AG26") (pinfunction "VDD_D3_AG26") (pintype "passive"))
      (node (ref "U2") (pin "AW19") (pinfunction "VDD_D4_AW19") (pintype "passive"))
    )
    (net (code "45") (name "Net-(U2A-VDD_D3-PadAG28)") (class "Default")
      (node (ref "U2") (pin "AG28") (pinfunction "VDD_D3_AG28") (pintype "passive"))
      (node (ref "U2") (pin "AW21") (pinfunction "VDD_D4_AW21") (pintype "passive"))
    )
    (net (code "46") (name "Net-(U2A-VDD_D3-PadAG32)") (class "Default")
      (node (ref "U2") (pin "AG32") (pinfunction "VDD_D3_AG32") (pintype "passive"))
      (node (ref "U2") (pin "AV2") (pinfunction "VDD_D4_AV2") (pintype "passive"))
    )
    (net (code "47") (name "Net-(U2A-VDD_D3-PadAG34)") (class "Default")
      (node (ref "U2") (pin "AG34") (pinfunction "VDD_D3_AG34") (pintype "passive"))
      (node (ref "U2") (pin "AV4") (pinfunction "VDD_D4_AV4") (pintype "passive"))
    )
    (net (code "48") (name "Net-(U2A-VDD_D3-PadAG36)") (class "Default")
      (node (ref "U2") (pin "AG36") (pinfunction "VDD_D3_AG36") (pintype "passive"))
      (node (ref "U2") (pin "AV6") (pinfunction "VDD_D4_AV6") (pintype "passive"))
    )
    (net (code "49") (name "Net-(U2A-VDD_D3-PadAG38)") (class "Default")
      (node (ref "U2") (pin "AG38") (pinfunction "VDD_D3_AG38") (pintype "passive"))
      (node (ref "U2") (pin "AV8") (pinfunction "VDD_D4_AV8") (pintype "passive"))
    )
    (net (code "50") (name "Net-(U2A-VDD_D3-PadAG40)") (class "Default")
      (node (ref "U2") (pin "AG40") (pinfunction "VDD_D3_AG40") (pintype "passive"))
      (node (ref "U2") (pin "AV10") (pinfunction "VDD_D4_AV10") (pintype "passive"))
    )
    (net (code "51") (name "Net-(U2A-VDD_D3-PadAG42)") (class "Default")
      (node (ref "U2") (pin "AG42") (pinfunction "VDD_D3_AG42") (pintype "passive"))
      (node (ref "U2") (pin "AV12") (pinfunction "VDD_D4_AV12") (pintype "passive"))
    )
    (net (code "52") (name "Net-(U2A-VDD_D3-PadAG44)") (class "Default")
      (node (ref "U2") (pin "AG44") (pinfunction "VDD_D3_AG44") (pintype "passive"))
      (node (ref "U2") (pin "AV14") (pinfunction "VDD_D4_AV14") (pintype "passive"))
    )
    (net (code "53") (name "Net-(U2A-VDD_D3-PadAH23)") (class "Default")
      (node (ref "U2") (pin "AH23") (pinfunction "VDD_D3_AH23") (pintype "passive"))
      (node (ref "U2") (pin "AV18") (pinfunction "VDD_D4_AV18") (pintype "passive"))
    )
    (net (code "54") (name "Net-(U2A-VDD_D3-PadAH25)") (class "Default")
      (node (ref "U2") (pin "AH25") (pinfunction "VDD_D3_AH25") (pintype "passive"))
      (node (ref "U2") (pin "AV20") (pinfunction "VDD_D4_AV20") (pintype "passive"))
    )
    (net (code "55") (name "Net-(U2A-VDD_D3-PadAH27)") (class "Default")
      (node (ref "U2") (pin "AH27") (pinfunction "VDD_D3_AH27") (pintype "passive"))
      (node (ref "U2") (pin "AV22") (pinfunction "VDD_D4_AV22") (pintype "passive"))
    )
    (net (code "56") (name "Net-(U2A-VDD_D3-PadAH31)") (class "Default")
      (node (ref "U2") (pin "AH31") (pinfunction "VDD_D3_AH31") (pintype "passive"))
      (node (ref "U2") (pin "AU1") (pinfunction "VDD_D4_AU1") (pintype "passive"))
    )
    (net (code "57") (name "Net-(U2A-VDD_D3-PadAH33)") (class "Default")
      (node (ref "U2") (pin "AH33") (pinfunction "VDD_D3_AH33") (pintype "passive"))
      (node (ref "U2") (pin "AU3") (pinfunction "VDD_D4_AU3") (pintype "passive"))
    )
    (net (code "58") (name "Net-(U2A-VDD_D3-PadAH35)") (class "Default")
      (node (ref "U2") (pin "AH35") (pinfunction "VDD_D3_AH35") (pintype "passive"))
      (node (ref "U2") (pin "AU5") (pinfunction "VDD_D4_AU5") (pintype "passive"))
    )
    (net (code "59") (name "Net-(U2A-VDD_D3-PadAH37)") (class "Default")
      (node (ref "U2") (pin "AH37") (pinfunction "VDD_D3_AH37") (pintype "passive"))
      (node (ref "U2") (pin "AU7") (pinfunction "VDD_D4_AU7") (pintype "passive"))
    )
    (net (code "60") (name "Net-(U2A-VDD_D3-PadAH39)") (class "Default")
      (node (ref "U2") (pin "AH39") (pinfunction "VDD_D3_AH39") (pintype "passive"))
      (node (ref "U2") (pin "AU9") (pinfunction "VDD_D4_AU9") (pintype "passive"))
    )
    (net (code "61") (name "Net-(U2A-VDD_D3-PadAH41)") (class "Default")
      (node (ref "U2") (pin "AH41") (pinfunction "VDD_D3_AH41") (pintype "passive"))
      (node (ref "U2") (pin "AU11") (pinfunction "VDD_D4_AU11") (pintype "passive"))
    )
    (net (code "62") (name "Net-(U2A-VDD_D3-PadAH43)") (class "Default")
      (node (ref "U2") (pin "AH43") (pinfunction "VDD_D3_AH43") (pintype "passive"))
      (node (ref "U2") (pin "AU13") (pinfunction "VDD_D4_AU13") (pintype "passive"))
    )
    (net (code "63") (name "Net-(U2A-VDD_D3-PadAJ24)") (class "Default")
      (node (ref "U2") (pin "AJ24") (pinfunction "VDD_D3_AJ24") (pintype "passive"))
      (node (ref "U2") (pin "AU17") (pinfunction "VDD_D4_AU17") (pintype "passive"))
    )
    (net (code "64") (name "Net-(U2A-VDD_D3-PadAJ26)") (class "Default")
      (node (ref "U2") (pin "AJ26") (pinfunction "VDD_D3_AJ26") (pintype "passive"))
      (node (ref "U2") (pin "AU19") (pinfunction "VDD_D4_AU19") (pintype "passive"))
    )
    (net (code "65") (name "Net-(U2A-VDD_D3-PadAJ28)") (class "Default")
      (node (ref "U2") (pin "AJ28") (pinfunction "VDD_D3_AJ28") (pintype "passive"))
      (node (ref "U2") (pin "AU21") (pinfunction "VDD_D4_AU21") (pintype "passive"))
    )
    (net (code "66") (name "Net-(U2A-VDD_D3-PadAJ32)") (class "Default")
      (node (ref "U2") (pin "AJ32") (pinfunction "VDD_D3_AJ32") (pintype "passive"))
      (node (ref "U2") (pin "AT2") (pinfunction "VDD_D4_AT2") (pintype "passive"))
    )
    (net (code "67") (name "Net-(U2A-VDD_D3-PadAJ34)") (class "Default")
      (node (ref "U2") (pin "AJ34") (pinfunction "VDD_D3_AJ34") (pintype "passive"))
      (node (ref "U2") (pin "AT4") (pinfunction "VDD_D4_AT4") (pintype "passive"))
    )
    (net (code "68") (name "Net-(U2A-VDD_D3-PadAJ36)") (class "Default")
      (node (ref "U2") (pin "AJ36") (pinfunction "VDD_D3_AJ36") (pintype "passive"))
      (node (ref "U2") (pin "AT6") (pinfunction "VDD_D4_AT6") (pintype "passive"))
    )
    (net (code "69") (name "Net-(U2A-VDD_D3-PadAJ38)") (class "Default")
      (node (ref "U2") (pin "AJ38") (pinfunction "VDD_D3_AJ38") (pintype "passive"))
      (node (ref "U2") (pin "AT8") (pinfunction "VDD_D4_AT8") (pintype "passive"))
    )
    (net (code "70") (name "Net-(U2A-VDD_D3-PadAJ40)") (class "Default")
      (node (ref "U2") (pin "AJ40") (pinfunction "VDD_D3_AJ40") (pintype "passive"))
      (node (ref "U2") (pin "AT10") (pinfunction "VDD_D4_AT10") (pintype "passive"))
    )
    (net (code "71") (name "Net-(U2A-VDD_D3-PadAJ42)") (class "Default")
      (node (ref "U2") (pin "AJ42") (pinfunction "VDD_D3_AJ42") (pintype "passive"))
      (node (ref "U2") (pin "AT12") (pinfunction "VDD_D4_AT12") (pintype "passive"))
    )
    (net (code "72") (name "Net-(U2A-VDD_D3-PadAJ44)") (class "Default")
      (node (ref "U2") (pin "AJ44") (pinfunction "VDD_D3_AJ44") (pintype "passive"))
      (node (ref "U2") (pin "AT14") (pinfunction "VDD_D4_AT14") (pintype "passive"))
    )
    (net (code "73") (name "Net-(U2A-VDD_D3-PadAK23)") (class "Default")
      (node (ref "U2") (pin "AK23") (pinfunction "VDD_D3_AK23") (pintype "passive"))
      (node (ref "U2") (pin "AT18") (pinfunction "VDD_D4_AT18") (pintype "passive"))
    )
    (net (code "74") (name "Net-(U2A-VDD_D3-PadAK27)") (class "Default")
      (node (ref "U2") (pin "AK27") (pinfunction "VDD_D3_AK27") (pintype "passive"))
      (node (ref "U2") (pin "AT22") (pinfunction "VDD_D4_AT22") (pintype "passive"))
    )
    (net (code "75") (name "Net-(U2A-VDD_D3-PadAK31)") (class "Default")
      (node (ref "U2") (pin "AK31") (pinfunction "VDD_D3_AK31") (pintype "passive"))
      (node (ref "U2") (pin "AR1") (pinfunction "VDD_D4_AR1") (pintype "passive"))
    )
    (net (code "76") (name "Net-(U2A-VDD_D3-PadAK33)") (class "Default")
      (node (ref "U2") (pin "AK33") (pinfunction "VDD_D3_AK33") (pintype "passive"))
      (node (ref "U2") (pin "AR3") (pinfunction "VDD_D4_AR3") (pintype "passive"))
    )
    (net (code "77") (name "Net-(U2A-VDD_D3-PadAK35)") (class "Default")
      (node (ref "U2") (pin "AK35") (pinfunction "VDD_D3_AK35") (pintype "passive"))
      (node (ref "U2") (pin "AR5") (pinfunction "VDD_D4_AR5") (pintype "passive"))
    )
    (net (code "78") (name "Net-(U2A-VDD_D3-PadAK37)") (class "Default")
      (node (ref "U2") (pin "AK37") (pinfunction "VDD_D3_AK37") (pintype "passive"))
      (node (ref "U2") (pin "AR7") (pinfunction "VDD_D4_AR7") (pintype "passive"))
    )
    (net (code "79") (name "Net-(U2A-VDD_D3-PadAK39)") (class "Default")
      (node (ref "U2") (pin "AK39") (pinfunction "VDD_D3_AK39") (pintype "passive"))
      (node (ref "U2") (pin "AR9") (pinfunction "VDD_D4_AR9") (pintype "passive"))
    )
    (net (code "80") (name "Net-(U2A-VDD_D3-PadAK41)") (class "Default")
      (node (ref "U2") (pin "AK41") (pinfunction "VDD_D3_AK41") (pintype "passive"))
      (node (ref "U2") (pin "AR11") (pinfunction "VDD_D4_AR11") (pintype "passive"))
    )
    (net (code "81") (name "Net-(U2A-VDD_D3-PadAK43)") (class "Default")
      (node (ref "U2") (pin "AK43") (pinfunction "VDD_D3_AK43") (pintype "passive"))
      (node (ref "U2") (pin "AR13") (pinfunction "VDD_D4_AR13") (pintype "passive"))
    )
    (net (code "82") (name "Net-(U2A-VDD_D3-PadAL24)") (class "Default")
      (node (ref "U2") (pin "AL24") (pinfunction "VDD_D3_AL24") (pintype "passive"))
      (node (ref "U2") (pin "AR17") (pinfunction "VDD_D4_AR17") (pintype "passive"))
    )
    (net (code "83") (name "Net-(U2A-VDD_D3-PadAL26)") (class "Default")
      (node (ref "U2") (pin "AL26") (pinfunction "VDD_D3_AL26") (pintype "passive"))
      (node (ref "U2") (pin "AR19") (pinfunction "VDD_D4_AR19") (pintype "passive"))
    )
    (net (code "84") (name "Net-(U2A-VDD_D3-PadAL28)") (class "Default")
      (node (ref "U2") (pin "AL28") (pinfunction "VDD_D3_AL28") (pintype "passive"))
      (node (ref "U2") (pin "AR21") (pinfunction "VDD_D4_AR21") (pintype "passive"))
    )
    (net (code "85") (name "Net-(U2A-VDD_D3-PadAL32)") (class "Default")
      (node (ref "U2") (pin "AL32") (pinfunction "VDD_D3_AL32") (pintype "passive"))
      (node (ref "U2") (pin "AP2") (pinfunction "VDD_D4_AP2") (pintype "passive"))
    )
    (net (code "86") (name "Net-(U2A-VDD_D3-PadAL34)") (class "Default")
      (node (ref "U2") (pin "AL34") (pinfunction "VDD_D3_AL34") (pintype "passive"))
      (node (ref "U2") (pin "AP4") (pinfunction "VDD_D4_AP4") (pintype "passive"))
    )
    (net (code "87") (name "Net-(U2A-VDD_D3-PadAL36)") (class "Default")
      (node (ref "U2") (pin "AL36") (pinfunction "VDD_D3_AL36") (pintype "passive"))
      (node (ref "U2") (pin "AP6") (pinfunction "VDD_D4_AP6") (pintype "passive"))
    )
    (net (code "88") (name "Net-(U2A-VDD_D3-PadAL38)") (class "Default")
      (node (ref "U2") (pin "AL38") (pinfunction "VDD_D3_AL38") (pintype "passive"))
      (node (ref "U2") (pin "AP8") (pinfunction "VDD_D4_AP8") (pintype "passive"))
    )
    (net (code "89") (name "Net-(U2A-VDD_D3-PadAL40)") (class "Default")
      (node (ref "U2") (pin "AL40") (pinfunction "VDD_D3_AL40") (pintype "passive"))
      (node (ref "U2") (pin "AP10") (pinfunction "VDD_D4_AP10") (pintype "passive"))
    )
    (net (code "90") (name "Net-(U2A-VDD_D3-PadAL42)") (class "Default")
      (node (ref "U2") (pin "AL42") (pinfunction "VDD_D3_AL42") (pintype "passive"))
      (node (ref "U2") (pin "AP12") (pinfunction "VDD_D4_AP12") (pintype "passive"))
    )
    (net (code "91") (name "Net-(U2A-VDD_D3-PadAL44)") (class "Default")
      (node (ref "U2") (pin "AL44") (pinfunction "VDD_D3_AL44") (pintype "passive"))
      (node (ref "U2") (pin "AP14") (pinfunction "VDD_D4_AP14") (pintype "passive"))
    )
    (net (code "92") (name "Net-(U2A-VDD_D3-PadAM23)") (class "Default")
      (node (ref "U2") (pin "AM23") (pinfunction "VDD_D3_AM23") (pintype "passive"))
      (node (ref "U2") (pin "AP18") (pinfunction "VDD_D4_AP18") (pintype "passive"))
    )
    (net (code "93") (name "Net-(U2A-VDD_D3-PadAM25)") (class "Default")
      (node (ref "U2") (pin "AM25") (pinfunction "VDD_D3_AM25") (pintype "passive"))
      (node (ref "U2") (pin "AP20") (pinfunction "VDD_D4_AP20") (pintype "passive"))
    )
    (net (code "94") (name "Net-(U2A-VDD_D3-PadAM27)") (class "Default")
      (node (ref "U2") (pin "AM27") (pinfunction "VDD_D3_AM27") (pintype "passive"))
      (node (ref "U2") (pin "AP22") (pinfunction "VDD_D4_AP22") (pintype "passive"))
    )
    (net (code "95") (name "Net-(U2A-VDD_D3-PadAM31)") (class "Default")
      (node (ref "U2") (pin "AM31") (pinfunction "VDD_D3_AM31") (pintype "passive"))
      (node (ref "U2") (pin "AN1") (pinfunction "VDD_D4_AN1") (pintype "passive"))
    )
    (net (code "96") (name "Net-(U2A-VDD_D3-PadAM33)") (class "Default")
      (node (ref "U2") (pin "AM33") (pinfunction "VDD_D3_AM33") (pintype "passive"))
      (node (ref "U2") (pin "AN3") (pinfunction "VDD_D4_AN3") (pintype "passive"))
    )
    (net (code "97") (name "Net-(U2A-VDD_D3-PadAM35)") (class "Default")
      (node (ref "U2") (pin "AM35") (pinfunction "VDD_D3_AM35") (pintype "passive"))
      (node (ref "U2") (pin "AN5") (pinfunction "VDD_D4_AN5") (pintype "passive"))
    )
    (net (code "98") (name "Net-(U2A-VDD_D3-PadAM37)") (class "Default")
      (node (ref "U2") (pin "AM37") (pinfunction "VDD_D3_AM37") (pintype "passive"))
      (node (ref "U2") (pin "AN7") (pinfunction "VDD_D4_AN7") (pintype "passive"))
    )
    (net (code "99") (name "Net-(U2A-VDD_D3-PadAM39)") (class "Default")
      (node (ref "U2") (pin "AM39") (pinfunction "VDD_D3_AM39") (pintype "passive"))
      (node (ref "U2") (pin "AN9") (pinfunction "VDD_D4_AN9") (pintype "passive"))
    )
    (net (code "100") (name "Net-(U2A-VDD_D3-PadAM41)") (class "Default")
      (node (ref "U2") (pin "AM41") (pinfunction "VDD_D3_AM41") (pintype "passive"))
      (node (ref "U2") (pin "AN11") (pinfunction "VDD_D4_AN11") (pintype "passive"))
    )
    (net (code "101") (name "Net-(U2A-VDD_D3-PadAM43)") (class "Default")
      (node (ref "U2") (pin "AM43") (pinfunction "VDD_D3_AM43") (pintype "passive"))
      (node (ref "U2") (pin "AN13") (pinfunction "VDD_D4_AN13") (pintype "passive"))
    )
    (net (code "102") (name "Net-(U2A-VSS-PadAC27)") (class "Default")
      (node (ref "U2") (pin "AC27") (pinfunction "VSS_AC27") (pintype "passive"))
      (node (ref "U2") (pin "BD5") (pinfunction "VSS_BD5") (pintype "passive"))
    )
    (net (code "103") (name "Net-(U2A-VSS-PadAF24)") (class "Default")
      (node (ref "U2") (pin "AF24") (pinfunction "VSS_AF24") (pintype "passive"))
      (node (ref "U2") (pin "AY17") (pinfunction "VSS_AY17") (pintype "passive"))
    )
    (net (code "104") (name "Net-(U2A-VSS-PadAF28)") (class "Default")
      (node (ref "U2") (pin "AF28") (pinfunction "VSS_AF28") (pintype "passive"))
      (node (ref "U2") (pin "AY21") (pinfunction "VSS_AY21") (pintype "passive"))
    )
    (net (code "105") (name "Net-(U2A-VSS-PadAF32)") (class "Default")
      (node (ref "U2") (pin "AF32") (pinfunction "VSS_AF32") (pintype "passive"))
      (node (ref "U2") (pin "AW2") (pinfunction "VSS_AW2") (pintype "passive"))
    )
    (net (code "106") (name "Net-(U2A-VSS-PadAF44)") (class "Default")
      (node (ref "U2") (pin "AF44") (pinfunction "VSS_AF44") (pintype "passive"))
      (node (ref "U2") (pin "AW14") (pinfunction "VSS_AW14") (pintype "passive"))
    )
    (net (code "107") (name "Net-(U2A-VSS-PadAG37)") (class "Default")
      (node (ref "U2") (pin "AG37") (pinfunction "VSS_AG37") (pintype "passive"))
      (node (ref "U2") (pin "AV7") (pinfunction "VSS_AV7") (pintype "passive"))
    )
    (net (code "108") (name "Net-(U2A-VSS-PadAG39)") (class "Default")
      (node (ref "U2") (pin "AG39") (pinfunction "VSS_AG39") (pintype "passive"))
      (node (ref "U2") (pin "AV9") (pinfunction "VSS_AV9") (pintype "passive"))
    )
    (net (code "109") (name "Net-(U2A-VSS-PadAG41)") (class "Default")
      (node (ref "U2") (pin "AG41") (pinfunction "VSS_AG41") (pintype "passive"))
      (node (ref "U2") (pin "AV11") (pinfunction "VSS_AV11") (pintype "passive"))
    )
    (net (code "110") (name "Net-(U2A-VSS-PadAG43)") (class "Default")
      (node (ref "U2") (pin "AG43") (pinfunction "VSS_AG43") (pintype "passive"))
      (node (ref "U2") (pin "AV13") (pinfunction "VSS_AV13") (pintype "passive"))
    )
    (net (code "111") (name "Net-(U2A-VSS-PadAH24)") (class "Default")
      (node (ref "U2") (pin "AH24") (pinfunction "VSS_AH24") (pintype "passive"))
      (node (ref "U2") (pin "AV17") (pinfunction "VSS_AV17") (pintype "passive"))
    )
    (net (code "112") (name "Net-(U2A-VSS-PadAH36)") (class "Default")
      (node (ref "U2") (pin "AH36") (pinfunction "VSS_AH36") (pintype "passive"))
      (node (ref "U2") (pin "AU6") (pinfunction "VSS_AU6") (pintype "passive"))
    )
    (net (code "113") (name "Net-(U2A-VSS-PadAH38)") (class "Default")
      (node (ref "U2") (pin "AH38") (pinfunction "VSS_AH38") (pintype "passive"))
      (node (ref "U2") (pin "AU8") (pinfunction "VSS_AU8") (pintype "passive"))
    )
    (net (code "114") (name "Net-(U2A-VSS-PadAH42)") (class "Default")
      (node (ref "U2") (pin "AH42") (pinfunction "VSS_AH42") (pintype "passive"))
      (node (ref "U2") (pin "AU12") (pinfunction "VSS_AU12") (pintype "passive"))
    )
    (net (code "115") (name "Net-(U2A-VSS-PadAH44)") (class "Default")
      (node (ref "U2") (pin "AH44") (pinfunction "VSS_AH44") (pintype "passive"))
      (node (ref "U2") (pin "AU14") (pinfunction "VSS_AU14") (pintype "passive"))
    )
    (net (code "116") (name "Net-(U2A-VSS-PadAJ23)") (class "Default")
      (node (ref "U2") (pin "AJ23") (pinfunction "VSS_AJ23") (pintype "passive"))
      (node (ref "U2") (pin "AU18") (pinfunction "VSS_AU18") (pintype "passive"))
    )
    (net (code "117") (name "Net-(U2A-VSS-PadAJ27)") (class "Default")
      (node (ref "U2") (pin "AJ27") (pinfunction "VSS_AJ27") (pintype "passive"))
      (node (ref "U2") (pin "AU22") (pinfunction "VSS_AU22") (pintype "passive"))
    )
    (net (code "118") (name "Net-(U2A-VSS-PadAK40)") (class "Default")
      (node (ref "U2") (pin "AK40") (pinfunction "VSS_AK40") (pintype "passive"))
      (node (ref "U2") (pin "AR10") (pinfunction "VSS_AR10") (pintype "passive"))
    )
    (net (code "119") (name "Net-(U2A-VSS-PadAM40)") (class "Default")
      (node (ref "U2") (pin "AM40") (pinfunction "VSS_AM40") (pintype "passive"))
      (node (ref "U2") (pin "AN10") (pinfunction "VSS_AN10") (pintype "passive"))
    )
    (net (code "120") (name "Net-(U2A-VSS-PadAM42)") (class "Default")
      (node (ref "U2") (pin "AM42") (pinfunction "VSS_AM42") (pintype "passive"))
      (node (ref "U2") (pin "AN12") (pinfunction "VSS_AN12") (pintype "passive"))
    )
  )
)
